# Public_CPU_DDR4.net
KiCad netlist of a schematic drawn in Altium Designer
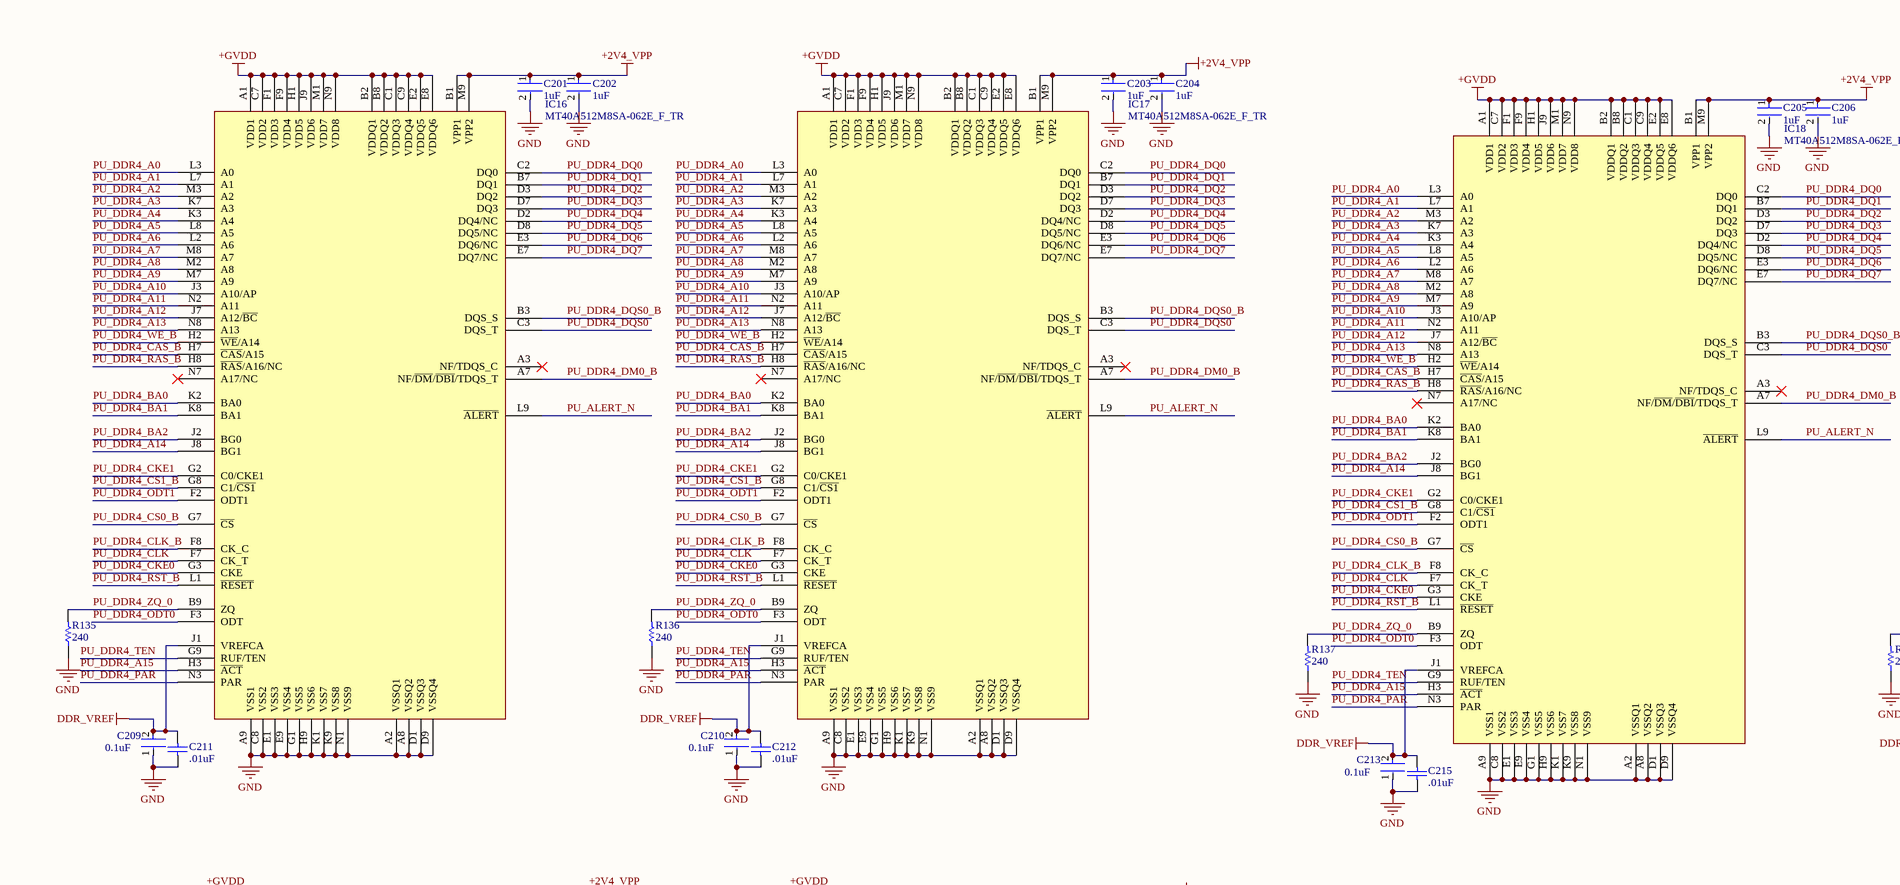
[diagram p0: Public_CPU_DDR4.SchDoc, top left]
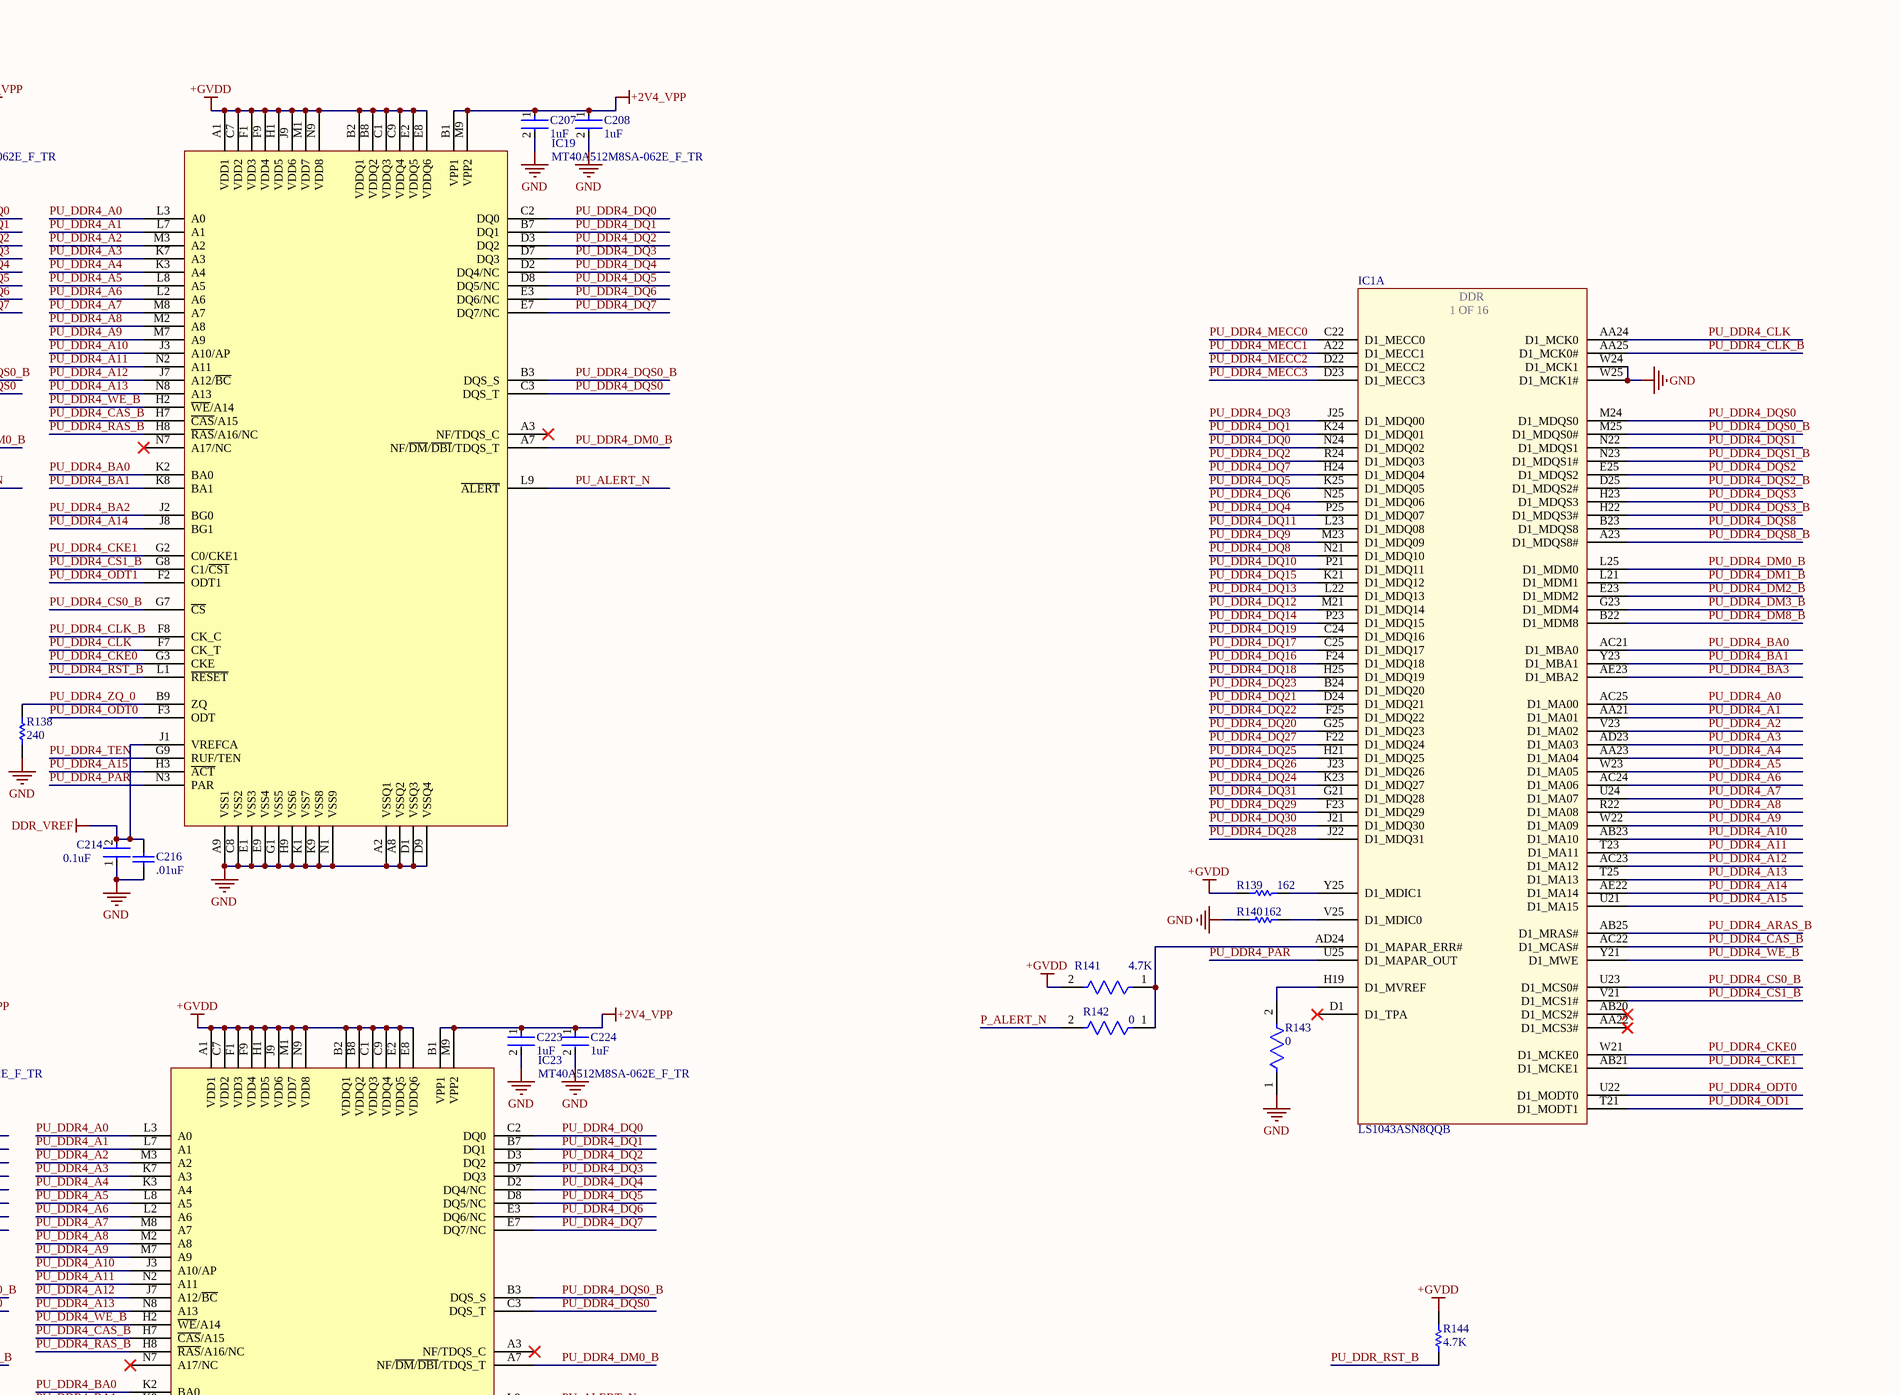
[diagram p1: Public_CPU_DDR4.SchDoc, top right]
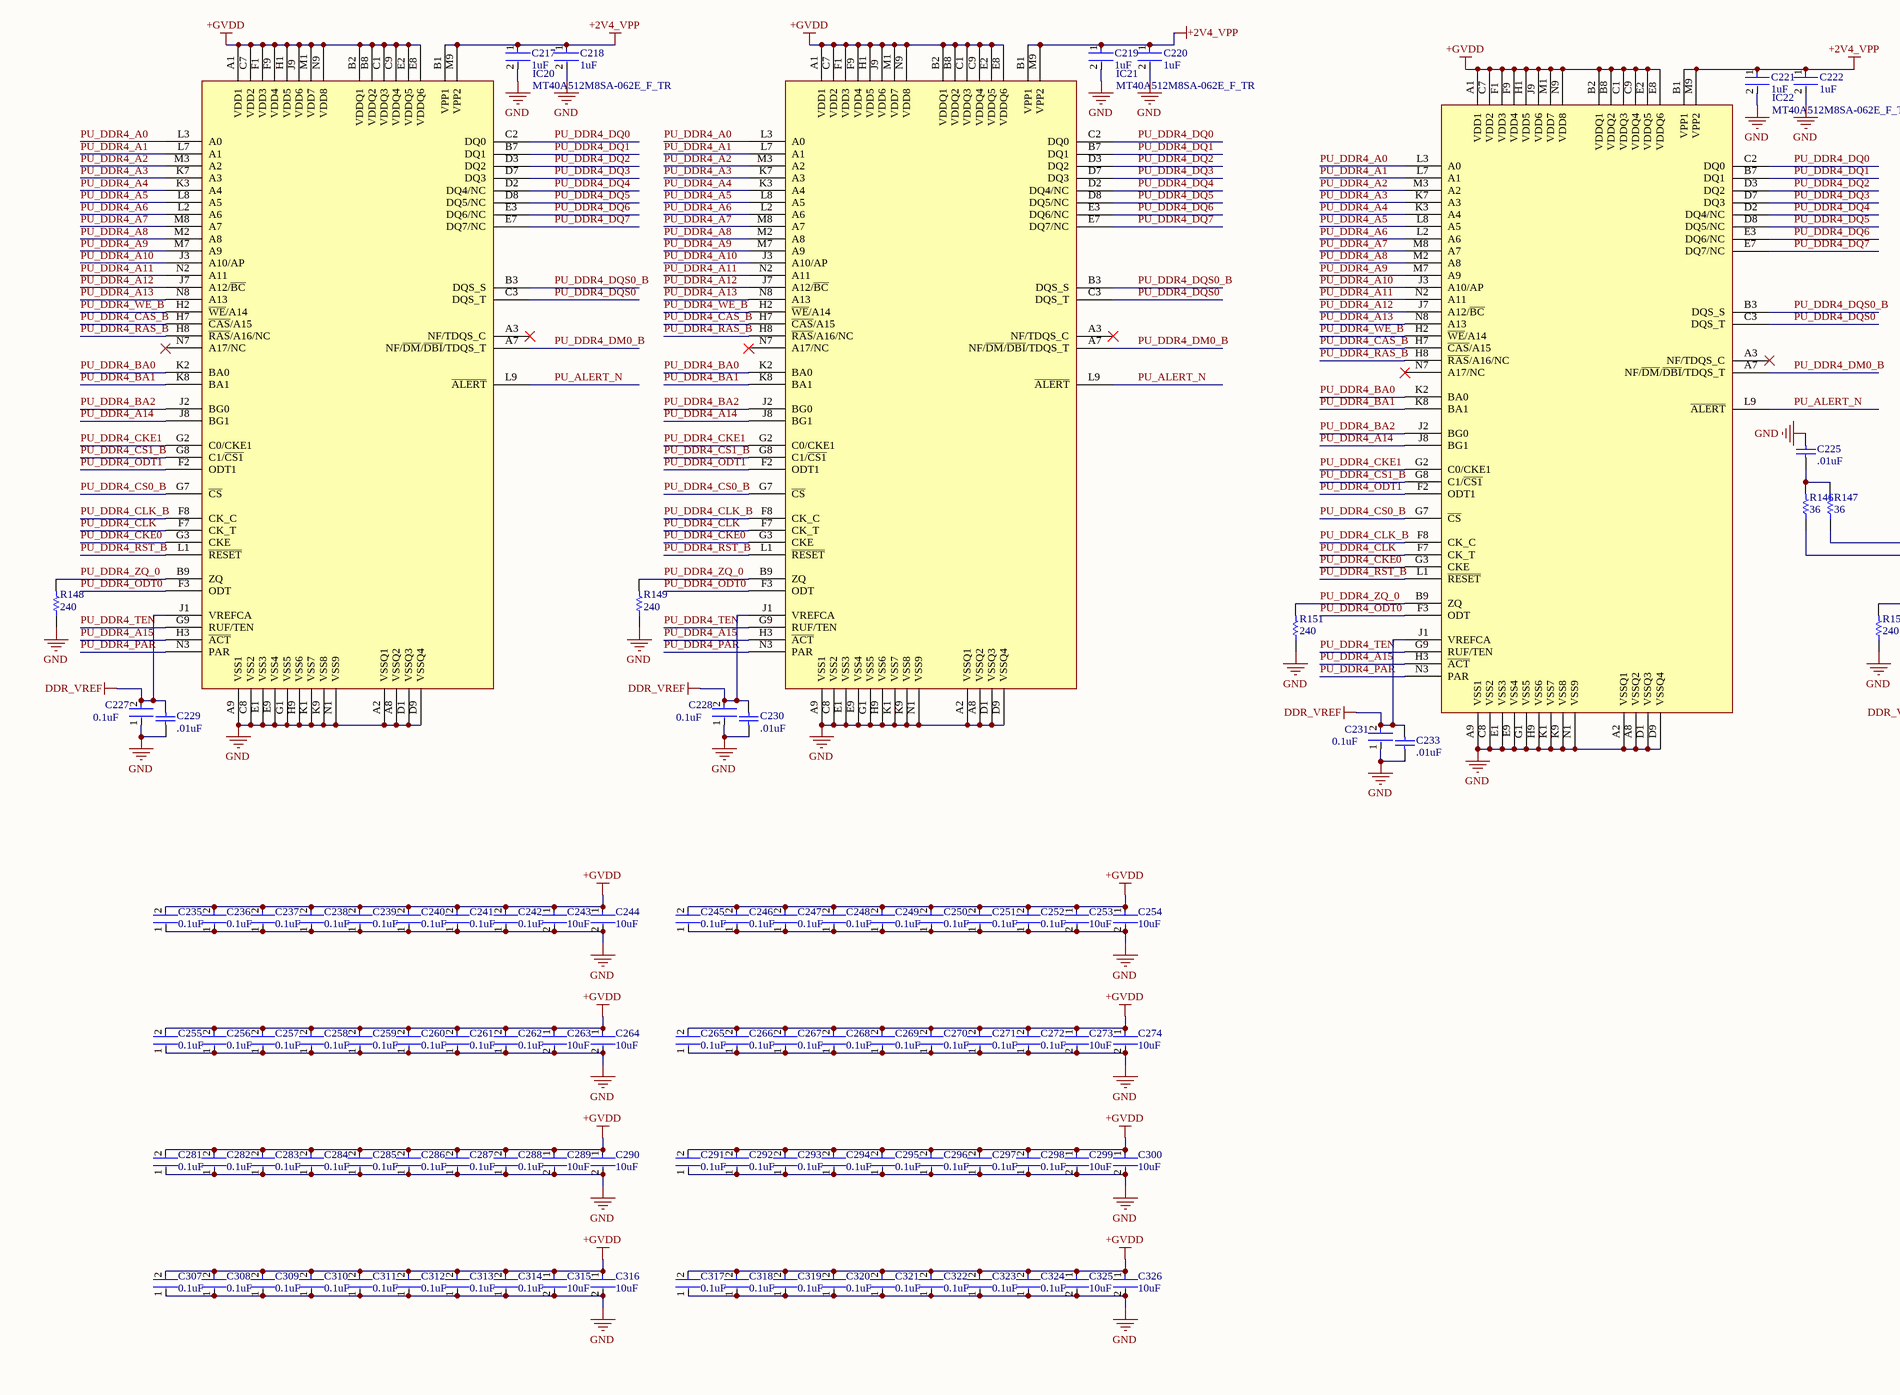
[diagram p2: Public_CPU_DDR4.SchDoc, bottom left]
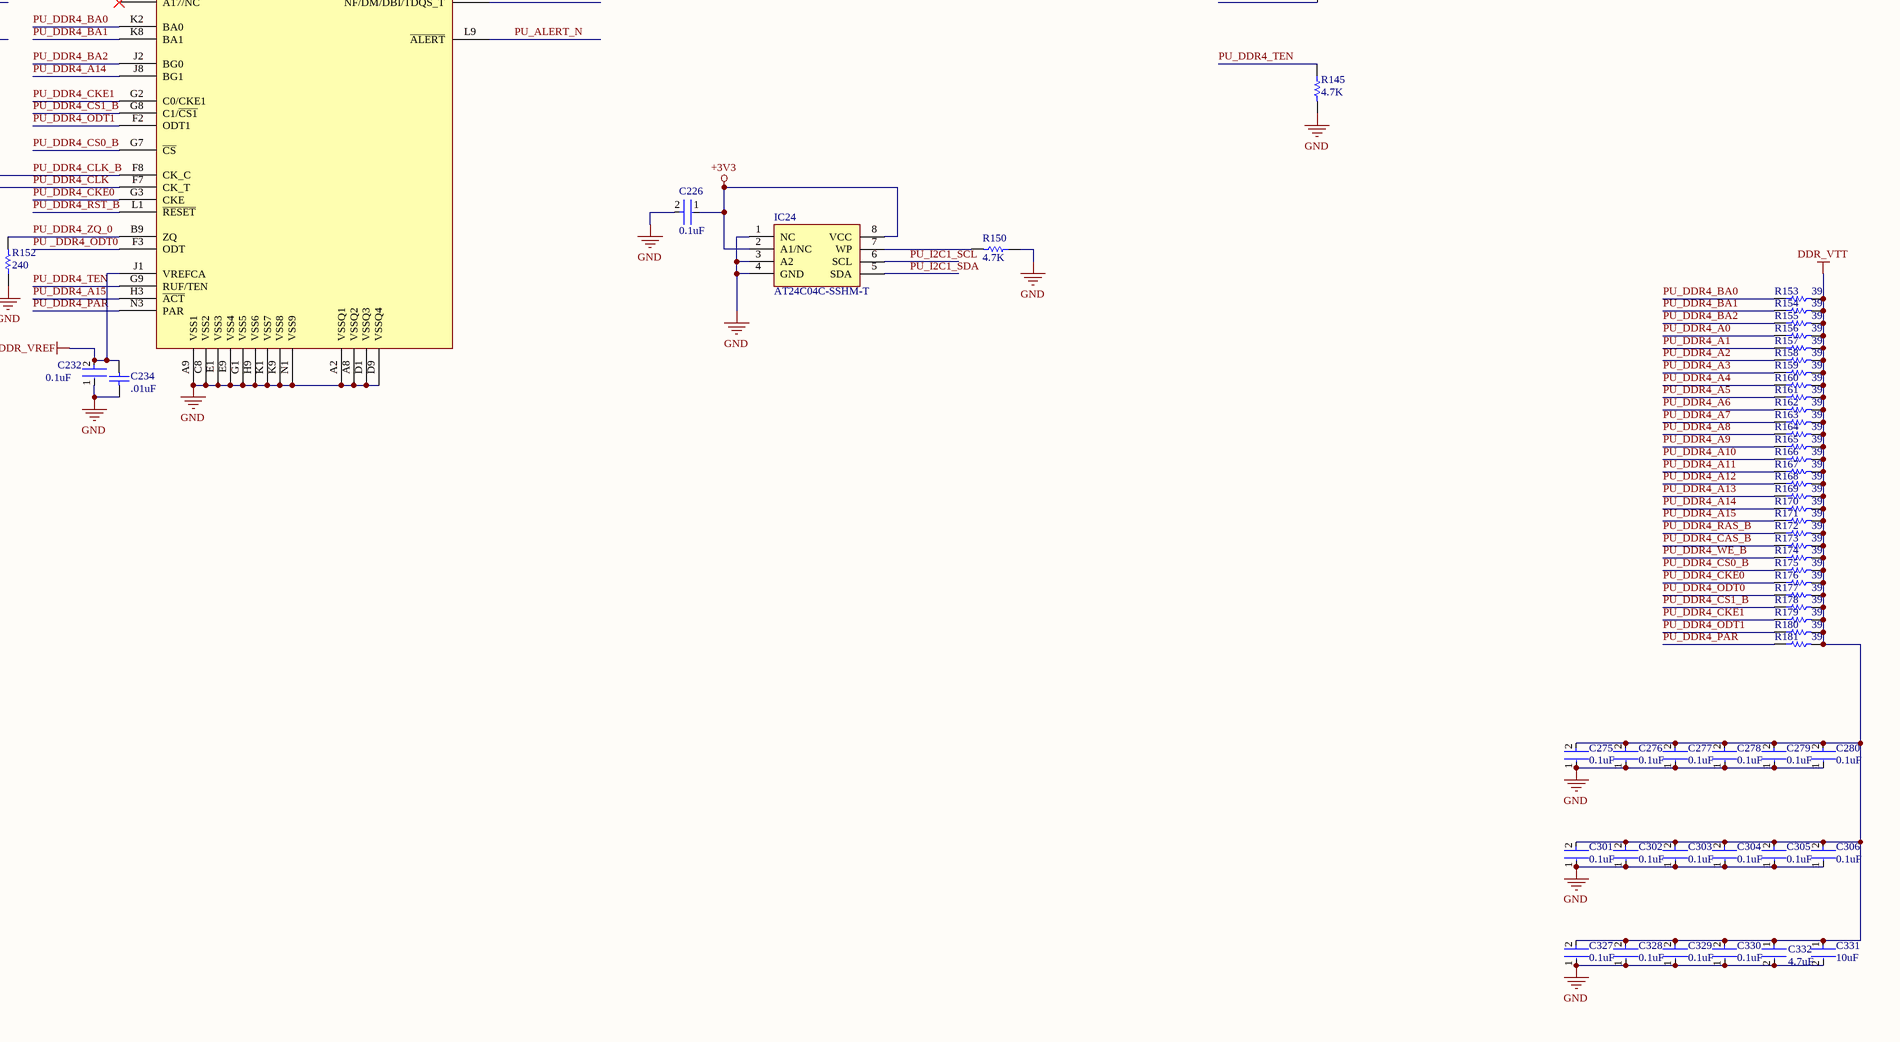
[diagram p3: Public_CPU_DDR4.SchDoc, bottom right]

(export (version "E")
  (design (tool "Eeschema 10.0.6"))
  (components
    (comp (ref "C201")
      (value "1uF")
      (footprint "FP-GRM15-0_1-MFG")
      (description "CAP CER 1UF 10V X5R 0402")
      (fields
        (field (name "OCTOPART") "https://octopart.com/grm155r61a105ke15d-murata-197442")
        (field (name "MANUFACTURER PART NUMBER") "GRM155R61A105KE15D")
      )
      (libsource (lib "Altium Content Vault") (part "02cd4be3c70576c341d710602a673aa"))
    )
    (comp (ref "C202")
      (value "1uF")
      (footprint "FP-GRM15-0_1-MFG")
      (description "CAP CER 1UF 10V X5R 0402")
      (fields
        (field (name "OCTOPART") "https://octopart.com/grm155r61a105ke15d-murata-197442")
        (field (name "MANUFACTURER PART NUMBER") "GRM155R61A105KE15D")
      )
      (libsource (lib "Altium Content Vault") (part "02cd4be3c70576c341d710602a673aa"))
    )
    (comp (ref "C203")
      (value "1uF")
      (footprint "FP-GRM15-0_1-MFG")
      (description "CAP CER 1UF 10V X5R 0402")
      (fields
        (field (name "OCTOPART") "https://octopart.com/grm155r61a105ke15d-murata-197442")
        (field (name "MANUFACTURER PART NUMBER") "GRM155R61A105KE15D")
      )
      (libsource (lib "Altium Content Vault") (part "02cd4be3c70576c341d710602a673aa"))
    )
    (comp (ref "C204")
      (value "1uF")
      (footprint "FP-GRM15-0_1-MFG")
      (description "CAP CER 1UF 10V X5R 0402")
      (fields
        (field (name "OCTOPART") "https://octopart.com/grm155r61a105ke15d-murata-197442")
        (field (name "MANUFACTURER PART NUMBER") "GRM155R61A105KE15D")
      )
      (libsource (lib "Altium Content Vault") (part "02cd4be3c70576c341d710602a673aa"))
    )
    (comp (ref "C205")
      (value "1uF")
      (footprint "FP-GRM15-0_1-MFG")
      (description "CAP CER 1UF 10V X5R 0402")
      (fields
        (field (name "OCTOPART") "https://octopart.com/grm155r61a105ke15d-murata-197442")
        (field (name "MANUFACTURER PART NUMBER") "GRM155R61A105KE15D")
      )
      (libsource (lib "Altium Content Vault") (part "02cd4be3c70576c341d710602a673aa"))
    )
    (comp (ref "C206")
      (value "1uF")
      (footprint "FP-GRM15-0_1-MFG")
      (description "CAP CER 1UF 10V X5R 0402")
      (fields
        (field (name "OCTOPART") "https://octopart.com/grm155r61a105ke15d-murata-197442")
        (field (name "MANUFACTURER PART NUMBER") "GRM155R61A105KE15D")
      )
      (libsource (lib "Altium Content Vault") (part "02cd4be3c70576c341d710602a673aa"))
    )
    (comp (ref "C207")
      (value "1uF")
      (footprint "FP-GRM15-0_1-MFG")
      (description "CAP CER 1UF 10V X5R 0402")
      (fields
        (field (name "OCTOPART") "https://octopart.com/grm155r61a105ke15d-murata-197442")
        (field (name "MANUFACTURER PART NUMBER") "GRM155R61A105KE15D")
      )
      (libsource (lib "Altium Content Vault") (part "02cd4be3c70576c341d710602a673aa"))
    )
    (comp (ref "C208")
      (value "1uF")
      (footprint "FP-GRM15-0_1-MFG")
      (description "CAP CER 1UF 10V X5R 0402")
      (fields
        (field (name "OCTOPART") "https://octopart.com/grm155r61a105ke15d-murata-197442")
        (field (name "MANUFACTURER PART NUMBER") "GRM155R61A105KE15D")
      )
      (libsource (lib "Altium Content Vault") (part "02cd4be3c70576c341d710602a673aa"))
    )
    (comp (ref "C209")
      (value "0.1uF")
      (footprint "FP-GRM15-MFG")
      (description "CAP CER 0.1UF 16V X7R 0402")
      (fields (field (name "MANUFACTURER PART NUMBER") "GRM155R71C104KA88D") (field (name "TOLERANCE") "10%"))
      (libsource (lib "Altium Content Vault") (part "236180d848d6139a670b325ea6854c9"))
    )
    (comp (ref "C210")
      (value "0.1uF")
      (footprint "FP-GRM15-MFG")
      (description "CAP CER 0.1UF 16V X7R 0402")
      (fields (field (name "MANUFACTURER PART NUMBER") "GRM155R71C104KA88D") (field (name "TOLERANCE") "10%"))
      (libsource (lib "Altium Content Vault") (part "236180d848d6139a670b325ea6854c9"))
    )
    (comp (ref "C211")
      (value ".01uF")
      (footprint "CAPC1005X56X25LL10T15")
      (fields
        (field (name "MANUFACTURER") "AVX Interconnect / Elco")
        (field (name "PART NUMBER") "0402YC103JAT2A")
      )
      (libsource (lib "Altium Content Vault") (part "CAP"))
    )
    (comp (ref "C212")
      (value ".01uF")
      (footprint "CAPC1005X56X25LL10T15")
      (fields
        (field (name "MANUFACTURER") "AVX Interconnect / Elco")
        (field (name "PART NUMBER") "0402YC103JAT2A")
      )
      (libsource (lib "Altium Content Vault") (part "CAP"))
    )
    (comp (ref "C213")
      (value "0.1uF")
      (footprint "FP-GRM15-MFG")
      (description "CAP CER 0.1UF 16V X7R 0402")
      (fields (field (name "MANUFACTURER PART NUMBER") "GRM155R71C104KA88D") (field (name "TOLERANCE") "10%"))
      (libsource (lib "Altium Content Vault") (part "236180d848d6139a670b325ea6854c9"))
    )
    (comp (ref "C214")
      (value "0.1uF")
      (footprint "FP-GRM15-MFG")
      (description "CAP CER 0.1UF 16V X7R 0402")
      (fields (field (name "MANUFACTURER PART NUMBER") "GRM155R71C104KA88D") (field (name "TOLERANCE") "10%"))
      (libsource (lib "Altium Content Vault") (part "236180d848d6139a670b325ea6854c9"))
    )
    (comp (ref "C215")
      (value ".01uF")
      (footprint "CAPC1005X56X25LL10T15")
      (fields
        (field (name "MANUFACTURER") "AVX Interconnect / Elco")
        (field (name "PART NUMBER") "0402YC103JAT2A")
      )
      (libsource (lib "Altium Content Vault") (part "CAP"))
    )
    (comp (ref "C216")
      (value ".01uF")
      (footprint "CAPC1005X56X25LL10T15")
      (fields
        (field (name "MANUFACTURER") "AVX Interconnect / Elco")
        (field (name "PART NUMBER") "0402YC103JAT2A")
      )
      (libsource (lib "Altium Content Vault") (part "CAP"))
    )
    (comp (ref "C217")
      (value "1uF")
      (footprint "FP-GRM15-0_1-MFG")
      (description "CAP CER 1UF 10V X5R 0402")
      (fields
        (field (name "OCTOPART") "https://octopart.com/grm155r61a105ke15d-murata-197442")
        (field (name "MANUFACTURER PART NUMBER") "GRM155R61A105KE15D")
      )
      (libsource (lib "Altium Content Vault") (part "02cd4be3c70576c341d710602a673aa"))
    )
    (comp (ref "C218")
      (value "1uF")
      (footprint "FP-GRM15-0_1-MFG")
      (description "CAP CER 1UF 10V X5R 0402")
      (fields
        (field (name "OCTOPART") "https://octopart.com/grm155r61a105ke15d-murata-197442")
        (field (name "MANUFACTURER PART NUMBER") "GRM155R61A105KE15D")
      )
      (libsource (lib "Altium Content Vault") (part "02cd4be3c70576c341d710602a673aa"))
    )
    (comp (ref "C219")
      (value "1uF")
      (footprint "FP-GRM15-0_1-MFG")
      (description "CAP CER 1UF 10V X5R 0402")
      (fields
        (field (name "OCTOPART") "https://octopart.com/grm155r61a105ke15d-murata-197442")
        (field (name "MANUFACTURER PART NUMBER") "GRM155R61A105KE15D")
      )
      (libsource (lib "Altium Content Vault") (part "02cd4be3c70576c341d710602a673aa"))
    )
    (comp (ref "C220")
      (value "1uF")
      (footprint "FP-GRM15-0_1-MFG")
      (description "CAP CER 1UF 10V X5R 0402")
      (fields
        (field (name "OCTOPART") "https://octopart.com/grm155r61a105ke15d-murata-197442")
        (field (name "MANUFACTURER PART NUMBER") "GRM155R61A105KE15D")
      )
      (libsource (lib "Altium Content Vault") (part "02cd4be3c70576c341d710602a673aa"))
    )
    (comp (ref "C221")
      (value "1uF")
      (footprint "FP-GRM15-0_1-MFG")
      (description "CAP CER 1UF 10V X5R 0402")
      (fields
        (field (name "OCTOPART") "https://octopart.com/grm155r61a105ke15d-murata-197442")
        (field (name "MANUFACTURER PART NUMBER") "GRM155R61A105KE15D")
      )
      (libsource (lib "Altium Content Vault") (part "02cd4be3c70576c341d710602a673aa"))
    )
    (comp (ref "C222")
      (value "1uF")
      (footprint "FP-GRM15-0_1-MFG")
      (description "CAP CER 1UF 10V X5R 0402")
      (fields
        (field (name "OCTOPART") "https://octopart.com/grm155r61a105ke15d-murata-197442")
        (field (name "MANUFACTURER PART NUMBER") "GRM155R61A105KE15D")
      )
      (libsource (lib "Altium Content Vault") (part "02cd4be3c70576c341d710602a673aa"))
    )
    (comp (ref "C223")
      (value "1uF")
      (footprint "FP-GRM15-0_1-MFG")
      (description "CAP CER 1UF 10V X5R 0402")
      (fields
        (field (name "OCTOPART") "https://octopart.com/grm155r61a105ke15d-murata-197442")
        (field (name "MANUFACTURER PART NUMBER") "GRM155R61A105KE15D")
      )
      (libsource (lib "Altium Content Vault") (part "02cd4be3c70576c341d710602a673aa"))
    )
    (comp (ref "C224")
      (value "1uF")
      (footprint "FP-GRM15-0_1-MFG")
      (description "CAP CER 1UF 10V X5R 0402")
      (fields
        (field (name "OCTOPART") "https://octopart.com/grm155r61a105ke15d-murata-197442")
        (field (name "MANUFACTURER PART NUMBER") "GRM155R61A105KE15D")
      )
      (libsource (lib "Altium Content Vault") (part "02cd4be3c70576c341d710602a673aa"))
    )
    (comp (ref "C225")
      (value ".01uF")
      (footprint "CAPC1005X56X25LL10T15")
      (fields
        (field (name "MANUFACTURER") "AVX Interconnect / Elco")
        (field (name "PART NUMBER") "0402YC103JAT2A")
      )
      (libsource (lib "Altium Content Vault") (part "CAP"))
    )
    (comp (ref "C226")
      (value "0.1uF")
      (footprint "FP-GRM15-MFG")
      (description "CAP CER 0.1UF 16V X7R 0402")
      (fields (field (name "MANUFACTURER PART NUMBER") "GRM155R71C104KA88D") (field (name "TOLERANCE") "10%"))
      (libsource (lib "Altium Content Vault") (part "236180d848d6139a670b325ea6854c9"))
    )
    (comp (ref "C227")
      (value "0.1uF")
      (footprint "FP-GRM15-MFG")
      (description "CAP CER 0.1UF 16V X7R 0402")
      (fields (field (name "MANUFACTURER PART NUMBER") "GRM155R71C104KA88D") (field (name "TOLERANCE") "10%"))
      (libsource (lib "Altium Content Vault") (part "236180d848d6139a670b325ea6854c9"))
    )
    (comp (ref "C228")
      (value "0.1uF")
      (footprint "FP-GRM15-MFG")
      (description "CAP CER 0.1UF 16V X7R 0402")
      (fields (field (name "MANUFACTURER PART NUMBER") "GRM155R71C104KA88D") (field (name "TOLERANCE") "10%"))
      (libsource (lib "Altium Content Vault") (part "236180d848d6139a670b325ea6854c9"))
    )
    (comp (ref "C229")
      (value ".01uF")
      (footprint "CAPC1005X56X25LL10T15")
      (fields
        (field (name "MANUFACTURER") "AVX Interconnect / Elco")
        (field (name "PART NUMBER") "0402YC103JAT2A")
      )
      (libsource (lib "Altium Content Vault") (part "CAP"))
    )
    (comp (ref "C230")
      (value ".01uF")
      (footprint "CAPC1005X56X25LL10T15")
      (fields
        (field (name "MANUFACTURER") "AVX Interconnect / Elco")
        (field (name "PART NUMBER") "0402YC103JAT2A")
      )
      (libsource (lib "Altium Content Vault") (part "CAP"))
    )
    (comp (ref "C231")
      (value "0.1uF")
      (footprint "FP-GRM15-MFG")
      (description "CAP CER 0.1UF 16V X7R 0402")
      (fields (field (name "MANUFACTURER PART NUMBER") "GRM155R71C104KA88D") (field (name "TOLERANCE") "10%"))
      (libsource (lib "Altium Content Vault") (part "236180d848d6139a670b325ea6854c9"))
    )
    (comp (ref "C232")
      (value "0.1uF")
      (footprint "FP-GRM15-MFG")
      (description "CAP CER 0.1UF 16V X7R 0402")
      (fields (field (name "MANUFACTURER PART NUMBER") "GRM155R71C104KA88D") (field (name "TOLERANCE") "10%"))
      (libsource (lib "Altium Content Vault") (part "236180d848d6139a670b325ea6854c9"))
    )
    (comp (ref "C233")
      (value ".01uF")
      (footprint "CAPC1005X56X25LL10T15")
      (fields
        (field (name "MANUFACTURER") "AVX Interconnect / Elco")
        (field (name "PART NUMBER") "0402YC103JAT2A")
      )
      (libsource (lib "Altium Content Vault") (part "CAP"))
    )
    (comp (ref "C234")
      (value ".01uF")
      (footprint "CAPC1005X56X25LL10T15")
      (fields
        (field (name "MANUFACTURER") "AVX Interconnect / Elco")
        (field (name "PART NUMBER") "0402YC103JAT2A")
      )
      (libsource (lib "Altium Content Vault") (part "CAP"))
    )
    (comp (ref "C235")
      (value "0.1uF")
      (footprint "FP-GRM15-MFG")
      (description "CAP CER 0.1UF 16V X7R 0402")
      (fields (field (name "MANUFACTURER PART NUMBER") "GRM155R71C104KA88D") (field (name "TOLERANCE") "10%"))
      (libsource (lib "Altium Content Vault") (part "236180d848d6139a670b325ea6854c9"))
    )
    (comp (ref "C236")
      (value "0.1uF")
      (footprint "FP-GRM15-MFG")
      (description "CAP CER 0.1UF 16V X7R 0402")
      (fields (field (name "MANUFACTURER PART NUMBER") "GRM155R71C104KA88D") (field (name "TOLERANCE") "10%"))
      (libsource (lib "Altium Content Vault") (part "236180d848d6139a670b325ea6854c9"))
    )
    (comp (ref "C237")
      (value "0.1uF")
      (footprint "FP-GRM15-MFG")
      (description "CAP CER 0.1UF 16V X7R 0402")
      (fields (field (name "MANUFACTURER PART NUMBER") "GRM155R71C104KA88D") (field (name "TOLERANCE") "10%"))
      (libsource (lib "Altium Content Vault") (part "236180d848d6139a670b325ea6854c9"))
    )
    (comp (ref "C238")
      (value "0.1uF")
      (footprint "FP-GRM15-MFG")
      (description "CAP CER 0.1UF 16V X7R 0402")
      (fields (field (name "MANUFACTURER PART NUMBER") "GRM155R71C104KA88D") (field (name "TOLERANCE") "10%"))
      (libsource (lib "Altium Content Vault") (part "236180d848d6139a670b325ea6854c9"))
    )
    (comp (ref "C239")
      (value "0.1uF")
      (footprint "FP-GRM15-MFG")
      (description "CAP CER 0.1UF 16V X7R 0402")
      (fields (field (name "MANUFACTURER PART NUMBER") "GRM155R71C104KA88D") (field (name "TOLERANCE") "10%"))
      (libsource (lib "Altium Content Vault") (part "236180d848d6139a670b325ea6854c9"))
    )
    (comp (ref "C240")
      (value "0.1uF")
      (footprint "FP-GRM15-MFG")
      (description "CAP CER 0.1UF 16V X7R 0402")
      (fields (field (name "MANUFACTURER PART NUMBER") "GRM155R71C104KA88D") (field (name "TOLERANCE") "10%"))
      (libsource (lib "Altium Content Vault") (part "236180d848d6139a670b325ea6854c9"))
    )
    (comp (ref "C241")
      (value "0.1uF")
      (footprint "FP-GRM15-MFG")
      (description "CAP CER 0.1UF 16V X7R 0402")
      (fields (field (name "MANUFACTURER PART NUMBER") "GRM155R71C104KA88D") (field (name "TOLERANCE") "10%"))
      (libsource (lib "Altium Content Vault") (part "236180d848d6139a670b325ea6854c9"))
    )
    (comp (ref "C242")
      (value "0.1uF")
      (footprint "FP-GRM15-MFG")
      (description "CAP CER 0.1UF 16V X7R 0402")
      (fields (field (name "MANUFACTURER PART NUMBER") "GRM155R71C104KA88D") (field (name "TOLERANCE") "10%"))
      (libsource (lib "Altium Content Vault") (part "236180d848d6139a670b325ea6854c9"))
    )
    (comp (ref "C243")
      (value "10uF")
      (footprint "FP-GRM21B-0_1-IPC_C")
      (description "Chip Multilayer Ceramic Capacitors for General Purpose, 0805, 10uF, X5R, 15%, 10%, 16V")
      (fields (field (name "TOLERANCE") "10%") (field (name "VOLTAGE") "16V"))
      (libsource (lib "Altium Content Vault") (part "b4654b650e69147ec39a6b967a45e02"))
    )
    (comp (ref "C244")
      (value "10uF")
      (footprint "FP-GRM21B-0_1-IPC_C")
      (description "Chip Multilayer Ceramic Capacitors for General Purpose, 0805, 10uF, X5R, 15%, 10%, 16V")
      (fields (field (name "TOLERANCE") "10%") (field (name "VOLTAGE") "16V"))
      (libsource (lib "Altium Content Vault") (part "b4654b650e69147ec39a6b967a45e02"))
    )
    (comp (ref "C245")
      (value "0.1uF")
      (footprint "FP-GRM15-MFG")
      (description "CAP CER 0.1UF 16V X7R 0402")
      (fields (field (name "MANUFACTURER PART NUMBER") "GRM155R71C104KA88D") (field (name "TOLERANCE") "10%"))
      (libsource (lib "Altium Content Vault") (part "236180d848d6139a670b325ea6854c9"))
    )
    (comp (ref "C246")
      (value "0.1uF")
      (footprint "FP-GRM15-MFG")
      (description "CAP CER 0.1UF 16V X7R 0402")
      (fields (field (name "MANUFACTURER PART NUMBER") "GRM155R71C104KA88D") (field (name "TOLERANCE") "10%"))
      (libsource (lib "Altium Content Vault") (part "236180d848d6139a670b325ea6854c9"))
    )
    (comp (ref "C247")
      (value "0.1uF")
      (footprint "FP-GRM15-MFG")
      (description "CAP CER 0.1UF 16V X7R 0402")
      (fields (field (name "MANUFACTURER PART NUMBER") "GRM155R71C104KA88D") (field (name "TOLERANCE") "10%"))
      (libsource (lib "Altium Content Vault") (part "236180d848d6139a670b325ea6854c9"))
    )
    (comp (ref "C248")
      (value "0.1uF")
      (footprint "FP-GRM15-MFG")
      (description "CAP CER 0.1UF 16V X7R 0402")
      (fields (field (name "MANUFACTURER PART NUMBER") "GRM155R71C104KA88D") (field (name "TOLERANCE") "10%"))
      (libsource (lib "Altium Content Vault") (part "236180d848d6139a670b325ea6854c9"))
    )
    (comp (ref "C249")
      (value "0.1uF")
      (footprint "FP-GRM15-MFG")
      (description "CAP CER 0.1UF 16V X7R 0402")
      (fields (field (name "MANUFACTURER PART NUMBER") "GRM155R71C104KA88D") (field (name "TOLERANCE") "10%"))
      (libsource (lib "Altium Content Vault") (part "236180d848d6139a670b325ea6854c9"))
    )
    (comp (ref "C250")
      (value "0.1uF")
      (footprint "FP-GRM15-MFG")
      (description "CAP CER 0.1UF 16V X7R 0402")
      (fields (field (name "MANUFACTURER PART NUMBER") "GRM155R71C104KA88D") (field (name "TOLERANCE") "10%"))
      (libsource (lib "Altium Content Vault") (part "236180d848d6139a670b325ea6854c9"))
    )
    (comp (ref "C251")
      (value "0.1uF")
      (footprint "FP-GRM15-MFG")
      (description "CAP CER 0.1UF 16V X7R 0402")
      (fields (field (name "MANUFACTURER PART NUMBER") "GRM155R71C104KA88D") (field (name "TOLERANCE") "10%"))
      (libsource (lib "Altium Content Vault") (part "236180d848d6139a670b325ea6854c9"))
    )
    (comp (ref "C252")
      (value "0.1uF")
      (footprint "FP-GRM15-MFG")
      (description "CAP CER 0.1UF 16V X7R 0402")
      (fields (field (name "MANUFACTURER PART NUMBER") "GRM155R71C104KA88D") (field (name "TOLERANCE") "10%"))
      (libsource (lib "Altium Content Vault") (part "236180d848d6139a670b325ea6854c9"))
    )
    (comp (ref "C253")
      (value "10uF")
      (footprint "FP-GRM21B-0_1-IPC_C")
      (description "Chip Multilayer Ceramic Capacitors for General Purpose, 0805, 10uF, X5R, 15%, 10%, 16V")
      (fields (field (name "TOLERANCE") "10%") (field (name "VOLTAGE") "16V"))
      (libsource (lib "Altium Content Vault") (part "b4654b650e69147ec39a6b967a45e02"))
    )
    (comp (ref "C254")
      (value "10uF")
      (footprint "FP-GRM21B-0_1-IPC_C")
      (description "Chip Multilayer Ceramic Capacitors for General Purpose, 0805, 10uF, X5R, 15%, 10%, 16V")
      (fields (field (name "TOLERANCE") "10%") (field (name "VOLTAGE") "16V"))
      (libsource (lib "Altium Content Vault") (part "b4654b650e69147ec39a6b967a45e02"))
    )
    (comp (ref "C255")
      (value "0.1uF")
      (footprint "FP-GRM15-MFG")
      (description "CAP CER 0.1UF 16V X7R 0402")
      (fields (field (name "MANUFACTURER PART NUMBER") "GRM155R71C104KA88D") (field (name "TOLERANCE") "10%"))
      (libsource (lib "Altium Content Vault") (part "236180d848d6139a670b325ea6854c9"))
    )
    (comp (ref "C256")
      (value "0.1uF")
      (footprint "FP-GRM15-MFG")
      (description "CAP CER 0.1UF 16V X7R 0402")
      (fields (field (name "MANUFACTURER PART NUMBER") "GRM155R71C104KA88D") (field (name "TOLERANCE") "10%"))
      (libsource (lib "Altium Content Vault") (part "236180d848d6139a670b325ea6854c9"))
    )
    (comp (ref "C257")
      (value "0.1uF")
      (footprint "FP-GRM15-MFG")
      (description "CAP CER 0.1UF 16V X7R 0402")
      (fields (field (name "MANUFACTURER PART NUMBER") "GRM155R71C104KA88D") (field (name "TOLERANCE") "10%"))
      (libsource (lib "Altium Content Vault") (part "236180d848d6139a670b325ea6854c9"))
    )
    (comp (ref "C258")
      (value "0.1uF")
      (footprint "FP-GRM15-MFG")
      (description "CAP CER 0.1UF 16V X7R 0402")
      (fields (field (name "MANUFACTURER PART NUMBER") "GRM155R71C104KA88D") (field (name "TOLERANCE") "10%"))
      (libsource (lib "Altium Content Vault") (part "236180d848d6139a670b325ea6854c9"))
    )
    (comp (ref "C259")
      (value "0.1uF")
      (footprint "FP-GRM15-MFG")
      (description "CAP CER 0.1UF 16V X7R 0402")
      (fields (field (name "MANUFACTURER PART NUMBER") "GRM155R71C104KA88D") (field (name "TOLERANCE") "10%"))
      (libsource (lib "Altium Content Vault") (part "236180d848d6139a670b325ea6854c9"))
    )
    (comp (ref "C260")
      (value "0.1uF")
      (footprint "FP-GRM15-MFG")
      (description "CAP CER 0.1UF 16V X7R 0402")
      (fields (field (name "MANUFACTURER PART NUMBER") "GRM155R71C104KA88D") (field (name "TOLERANCE") "10%"))
      (libsource (lib "Altium Content Vault") (part "236180d848d6139a670b325ea6854c9"))
    )
    (comp (ref "C261")
      (value "0.1uF")
      (footprint "FP-GRM15-MFG")
      (description "CAP CER 0.1UF 16V X7R 0402")
      (fields (field (name "MANUFACTURER PART NUMBER") "GRM155R71C104KA88D") (field (name "TOLERANCE") "10%"))
      (libsource (lib "Altium Content Vault") (part "236180d848d6139a670b325ea6854c9"))
    )
    (comp (ref "C262")
      (value "0.1uF")
      (footprint "FP-GRM15-MFG")
      (description "CAP CER 0.1UF 16V X7R 0402")
      (fields (field (name "MANUFACTURER PART NUMBER") "GRM155R71C104KA88D") (field (name "TOLERANCE") "10%"))
      (libsource (lib "Altium Content Vault") (part "236180d848d6139a670b325ea6854c9"))
    )
    (comp (ref "C263")
      (value "10uF")
      (footprint "FP-GRM21B-0_1-IPC_C")
      (description "Chip Multilayer Ceramic Capacitors for General Purpose, 0805, 10uF, X5R, 15%, 10%, 16V")
      (fields (field (name "TOLERANCE") "10%") (field (name "VOLTAGE") "16V"))
      (libsource (lib "Altium Content Vault") (part "b4654b650e69147ec39a6b967a45e02"))
    )
    (comp (ref "C264")
      (value "10uF")
      (footprint "FP-GRM21B-0_1-IPC_C")
      (description "Chip Multilayer Ceramic Capacitors for General Purpose, 0805, 10uF, X5R, 15%, 10%, 16V")
      (fields (field (name "TOLERANCE") "10%") (field (name "VOLTAGE") "16V"))
      (libsource (lib "Altium Content Vault") (part "b4654b650e69147ec39a6b967a45e02"))
    )
    (comp (ref "C265")
      (value "0.1uF")
      (footprint "FP-GRM15-MFG")
      (description "CAP CER 0.1UF 16V X7R 0402")
      (fields (field (name "MANUFACTURER PART NUMBER") "GRM155R71C104KA88D") (field (name "TOLERANCE") "10%"))
      (libsource (lib "Altium Content Vault") (part "236180d848d6139a670b325ea6854c9"))
    )
    (comp (ref "C266")
      (value "0.1uF")
      (footprint "FP-GRM15-MFG")
      (description "CAP CER 0.1UF 16V X7R 0402")
      (fields (field (name "MANUFACTURER PART NUMBER") "GRM155R71C104KA88D") (field (name "TOLERANCE") "10%"))
      (libsource (lib "Altium Content Vault") (part "236180d848d6139a670b325ea6854c9"))
    )
    (comp (ref "C267")
      (value "0.1uF")
      (footprint "FP-GRM15-MFG")
      (description "CAP CER 0.1UF 16V X7R 0402")
      (fields (field (name "MANUFACTURER PART NUMBER") "GRM155R71C104KA88D") (field (name "TOLERANCE") "10%"))
      (libsource (lib "Altium Content Vault") (part "236180d848d6139a670b325ea6854c9"))
    )
    (comp (ref "C268")
      (value "0.1uF")
      (footprint "FP-GRM15-MFG")
      (description "CAP CER 0.1UF 16V X7R 0402")
      (fields (field (name "MANUFACTURER PART NUMBER") "GRM155R71C104KA88D") (field (name "TOLERANCE") "10%"))
      (libsource (lib "Altium Content Vault") (part "236180d848d6139a670b325ea6854c9"))
    )
    (comp (ref "C269")
      (value "0.1uF")
      (footprint "FP-GRM15-MFG")
      (description "CAP CER 0.1UF 16V X7R 0402")
      (fields (field (name "MANUFACTURER PART NUMBER") "GRM155R71C104KA88D") (field (name "TOLERANCE") "10%"))
      (libsource (lib "Altium Content Vault") (part "236180d848d6139a670b325ea6854c9"))
    )
    (comp (ref "C270")
      (value "0.1uF")
      (footprint "FP-GRM15-MFG")
      (description "CAP CER 0.1UF 16V X7R 0402")
      (fields (field (name "MANUFACTURER PART NUMBER") "GRM155R71C104KA88D") (field (name "TOLERANCE") "10%"))
      (libsource (lib "Altium Content Vault") (part "236180d848d6139a670b325ea6854c9"))
    )
    (comp (ref "C271")
      (value "0.1uF")
      (footprint "FP-GRM15-MFG")
      (description "CAP CER 0.1UF 16V X7R 0402")
      (fields (field (name "MANUFACTURER PART NUMBER") "GRM155R71C104KA88D") (field (name "TOLERANCE") "10%"))
      (libsource (lib "Altium Content Vault") (part "236180d848d6139a670b325ea6854c9"))
    )
    (comp (ref "C272")
      (value "0.1uF")
      (footprint "FP-GRM15-MFG")
      (description "CAP CER 0.1UF 16V X7R 0402")
      (fields (field (name "MANUFACTURER PART NUMBER") "GRM155R71C104KA88D") (field (name "TOLERANCE") "10%"))
      (libsource (lib "Altium Content Vault") (part "236180d848d6139a670b325ea6854c9"))
    )
    (comp (ref "C273")
      (value "10uF")
      (footprint "FP-GRM21B-0_1-IPC_C")
      (description "Chip Multilayer Ceramic Capacitors for General Purpose, 0805, 10uF, X5R, 15%, 10%, 16V")
      (fields (field (name "TOLERANCE") "10%") (field (name "VOLTAGE") "16V"))
      (libsource (lib "Altium Content Vault") (part "b4654b650e69147ec39a6b967a45e02"))
    )
    (comp (ref "C274")
      (value "10uF")
      (footprint "FP-GRM21B-0_1-IPC_C")
      (description "Chip Multilayer Ceramic Capacitors for General Purpose, 0805, 10uF, X5R, 15%, 10%, 16V")
      (fields (field (name "TOLERANCE") "10%") (field (name "VOLTAGE") "16V"))
      (libsource (lib "Altium Content Vault") (part "b4654b650e69147ec39a6b967a45e02"))
    )
    (comp (ref "C275")
      (value "0.1uF")
      (footprint "FP-GRM15-MFG")
      (description "CAP CER 0.1UF 16V X7R 0402")
      (fields (field (name "MANUFACTURER PART NUMBER") "GRM155R71C104KA88D") (field (name "TOLERANCE") "10%"))
      (libsource (lib "Altium Content Vault") (part "236180d848d6139a670b325ea6854c9"))
    )
    (comp (ref "C276")
      (value "0.1uF")
      (footprint "FP-GRM15-MFG")
      (description "CAP CER 0.1UF 16V X7R 0402")
      (fields (field (name "MANUFACTURER PART NUMBER") "GRM155R71C104KA88D") (field (name "TOLERANCE") "10%"))
      (libsource (lib "Altium Content Vault") (part "236180d848d6139a670b325ea6854c9"))
    )
    (comp (ref "C277")
      (value "0.1uF")
      (footprint "FP-GRM15-MFG")
      (description "CAP CER 0.1UF 16V X7R 0402")
      (fields (field (name "MANUFACTURER PART NUMBER") "GRM155R71C104KA88D") (field (name "TOLERANCE") "10%"))
      (libsource (lib "Altium Content Vault") (part "236180d848d6139a670b325ea6854c9"))
    )
    (comp (ref "C278")
      (value "0.1uF")
      (footprint "FP-GRM15-MFG")
      (description "CAP CER 0.1UF 16V X7R 0402")
      (fields (field (name "MANUFACTURER PART NUMBER") "GRM155R71C104KA88D") (field (name "TOLERANCE") "10%"))
      (libsource (lib "Altium Content Vault") (part "236180d848d6139a670b325ea6854c9"))
    )
    (comp (ref "C279")
      (value "0.1uF")
      (footprint "FP-GRM15-MFG")
      (description "CAP CER 0.1UF 16V X7R 0402")
      (fields (field (name "MANUFACTURER PART NUMBER") "GRM155R71C104KA88D") (field (name "TOLERANCE") "10%"))
      (libsource (lib "Altium Content Vault") (part "236180d848d6139a670b325ea6854c9"))
    )
    (comp (ref "C280")
      (value "0.1uF")
      (footprint "FP-GRM15-MFG")
      (description "CAP CER 0.1UF 16V X7R 0402")
      (fields (field (name "MANUFACTURER PART NUMBER") "GRM155R71C104KA88D") (field (name "TOLERANCE") "10%"))
      (libsource (lib "Altium Content Vault") (part "236180d848d6139a670b325ea6854c9"))
    )
    (comp (ref "C281")
      (value "0.1uF")
      (footprint "FP-GRM15-MFG")
      (description "CAP CER 0.1UF 16V X7R 0402")
      (fields (field (name "MANUFACTURER PART NUMBER") "GRM155R71C104KA88D") (field (name "TOLERANCE") "10%"))
      (libsource (lib "Altium Content Vault") (part "236180d848d6139a670b325ea6854c9"))
    )
    (comp (ref "C282")
      (value "0.1uF")
      (footprint "FP-GRM15-MFG")
      (description "CAP CER 0.1UF 16V X7R 0402")
      (fields (field (name "MANUFACTURER PART NUMBER") "GRM155R71C104KA88D") (field (name "TOLERANCE") "10%"))
      (libsource (lib "Altium Content Vault") (part "236180d848d6139a670b325ea6854c9"))
    )
    (comp (ref "C283")
      (value "0.1uF")
      (footprint "FP-GRM15-MFG")
      (description "CAP CER 0.1UF 16V X7R 0402")
      (fields (field (name "MANUFACTURER PART NUMBER") "GRM155R71C104KA88D") (field (name "TOLERANCE") "10%"))
      (libsource (lib "Altium Content Vault") (part "236180d848d6139a670b325ea6854c9"))
    )
    (comp (ref "C284")
      (value "0.1uF")
      (footprint "FP-GRM15-MFG")
      (description "CAP CER 0.1UF 16V X7R 0402")
      (fields (field (name "MANUFACTURER PART NUMBER") "GRM155R71C104KA88D") (field (name "TOLERANCE") "10%"))
      (libsource (lib "Altium Content Vault") (part "236180d848d6139a670b325ea6854c9"))
    )
    (comp (ref "C285")
      (value "0.1uF")
      (footprint "FP-GRM15-MFG")
      (description "CAP CER 0.1UF 16V X7R 0402")
      (fields (field (name "MANUFACTURER PART NUMBER") "GRM155R71C104KA88D") (field (name "TOLERANCE") "10%"))
      (libsource (lib "Altium Content Vault") (part "236180d848d6139a670b325ea6854c9"))
    )
    (comp (ref "C286")
      (value "0.1uF")
      (footprint "FP-GRM15-MFG")
      (description "CAP CER 0.1UF 16V X7R 0402")
      (fields (field (name "MANUFACTURER PART NUMBER") "GRM155R71C104KA88D") (field (name "TOLERANCE") "10%"))
      (libsource (lib "Altium Content Vault") (part "236180d848d6139a670b325ea6854c9"))
    )
    (comp (ref "C287")
      (value "0.1uF")
      (footprint "FP-GRM15-MFG")
      (description "CAP CER 0.1UF 16V X7R 0402")
      (fields (field (name "MANUFACTURER PART NUMBER") "GRM155R71C104KA88D") (field (name "TOLERANCE") "10%"))
      (libsource (lib "Altium Content Vault") (part "236180d848d6139a670b325ea6854c9"))
    )
    (comp (ref "C288")
      (value "0.1uF")
      (footprint "FP-GRM15-MFG")
      (description "CAP CER 0.1UF 16V X7R 0402")
      (fields (field (name "MANUFACTURER PART NUMBER") "GRM155R71C104KA88D") (field (name "TOLERANCE") "10%"))
      (libsource (lib "Altium Content Vault") (part "236180d848d6139a670b325ea6854c9"))
    )
    (comp (ref "C289")
      (value "10uF")
      (footprint "FP-GRM21B-0_1-IPC_C")
      (description "Chip Multilayer Ceramic Capacitors for General Purpose, 0805, 10uF, X5R, 15%, 10%, 16V")
      (fields (field (name "TOLERANCE") "10%") (field (name "VOLTAGE") "16V"))
      (libsource (lib "Altium Content Vault") (part "b4654b650e69147ec39a6b967a45e02"))
    )
    (comp (ref "C290")
      (value "10uF")
      (footprint "FP-GRM21B-0_1-IPC_C")
      (description "Chip Multilayer Ceramic Capacitors for General Purpose, 0805, 10uF, X5R, 15%, 10%, 16V")
      (fields (field (name "TOLERANCE") "10%") (field (name "VOLTAGE") "16V"))
      (libsource (lib "Altium Content Vault") (part "b4654b650e69147ec39a6b967a45e02"))
    )
    (comp (ref "C291")
      (value "0.1uF")
      (footprint "FP-GRM15-MFG")
      (description "CAP CER 0.1UF 16V X7R 0402")
      (fields (field (name "MANUFACTURER PART NUMBER") "GRM155R71C104KA88D") (field (name "TOLERANCE") "10%"))
      (libsource (lib "Altium Content Vault") (part "236180d848d6139a670b325ea6854c9"))
    )
    (comp (ref "C292")
      (value "0.1uF")
      (footprint "FP-GRM15-MFG")
      (description "CAP CER 0.1UF 16V X7R 0402")
      (fields (field (name "MANUFACTURER PART NUMBER") "GRM155R71C104KA88D") (field (name "TOLERANCE") "10%"))
      (libsource (lib "Altium Content Vault") (part "236180d848d6139a670b325ea6854c9"))
    )
    (comp (ref "C293")
      (value "0.1uF")
      (footprint "FP-GRM15-MFG")
      (description "CAP CER 0.1UF 16V X7R 0402")
      (fields (field (name "MANUFACTURER PART NUMBER") "GRM155R71C104KA88D") (field (name "TOLERANCE") "10%"))
      (libsource (lib "Altium Content Vault") (part "236180d848d6139a670b325ea6854c9"))
    )
    (comp (ref "C294")
      (value "0.1uF")
      (footprint "FP-GRM15-MFG")
      (description "CAP CER 0.1UF 16V X7R 0402")
      (fields (field (name "MANUFACTURER PART NUMBER") "GRM155R71C104KA88D") (field (name "TOLERANCE") "10%"))
      (libsource (lib "Altium Content Vault") (part "236180d848d6139a670b325ea6854c9"))
    )
    (comp (ref "C295")
      (value "0.1uF")
      (footprint "FP-GRM15-MFG")
      (description "CAP CER 0.1UF 16V X7R 0402")
      (fields (field (name "MANUFACTURER PART NUMBER") "GRM155R71C104KA88D") (field (name "TOLERANCE") "10%"))
      (libsource (lib "Altium Content Vault") (part "236180d848d6139a670b325ea6854c9"))
    )
    (comp (ref "C296")
      (value "0.1uF")
      (footprint "FP-GRM15-MFG")
      (description "CAP CER 0.1UF 16V X7R 0402")
      (fields (field (name "MANUFACTURER PART NUMBER") "GRM155R71C104KA88D") (field (name "TOLERANCE") "10%"))
      (libsource (lib "Altium Content Vault") (part "236180d848d6139a670b325ea6854c9"))
    )
    (comp (ref "C297")
      (value "0.1uF")
      (footprint "FP-GRM15-MFG")
      (description "CAP CER 0.1UF 16V X7R 0402")
      (fields (field (name "MANUFACTURER PART NUMBER") "GRM155R71C104KA88D") (field (name "TOLERANCE") "10%"))
      (libsource (lib "Altium Content Vault") (part "236180d848d6139a670b325ea6854c9"))
    )
    (comp (ref "C298")
      (value "0.1uF")
      (footprint "FP-GRM15-MFG")
      (description "CAP CER 0.1UF 16V X7R 0402")
      (fields (field (name "MANUFACTURER PART NUMBER") "GRM155R71C104KA88D") (field (name "TOLERANCE") "10%"))
      (libsource (lib "Altium Content Vault") (part "236180d848d6139a670b325ea6854c9"))
    )
    (comp (ref "C299")
      (value "10uF")
      (footprint "FP-GRM21B-0_1-IPC_C")
      (description "Chip Multilayer Ceramic Capacitors for General Purpose, 0805, 10uF, X5R, 15%, 10%, 16V")
      (fields (field (name "TOLERANCE") "10%") (field (name "VOLTAGE") "16V"))
      (libsource (lib "Altium Content Vault") (part "b4654b650e69147ec39a6b967a45e02"))
    )
    (comp (ref "C300")
      (value "10uF")
      (footprint "FP-GRM21B-0_1-IPC_C")
      (description "Chip Multilayer Ceramic Capacitors for General Purpose, 0805, 10uF, X5R, 15%, 10%, 16V")
      (fields (field (name "TOLERANCE") "10%") (field (name "VOLTAGE") "16V"))
      (libsource (lib "Altium Content Vault") (part "b4654b650e69147ec39a6b967a45e02"))
    )
    (comp (ref "C301")
      (value "0.1uF")
      (footprint "FP-GRM15-MFG")
      (description "CAP CER 0.1UF 16V X7R 0402")
      (fields (field (name "MANUFACTURER PART NUMBER") "GRM155R71C104KA88D") (field (name "TOLERANCE") "10%"))
      (libsource (lib "Altium Content Vault") (part "236180d848d6139a670b325ea6854c9"))
    )
    (comp (ref "C302")
      (value "0.1uF")
      (footprint "FP-GRM15-MFG")
      (description "CAP CER 0.1UF 16V X7R 0402")
      (fields (field (name "MANUFACTURER PART NUMBER") "GRM155R71C104KA88D") (field (name "TOLERANCE") "10%"))
      (libsource (lib "Altium Content Vault") (part "236180d848d6139a670b325ea6854c9"))
    )
    (comp (ref "C303")
      (value "0.1uF")
      (footprint "FP-GRM15-MFG")
      (description "CAP CER 0.1UF 16V X7R 0402")
      (fields (field (name "MANUFACTURER PART NUMBER") "GRM155R71C104KA88D") (field (name "TOLERANCE") "10%"))
      (libsource (lib "Altium Content Vault") (part "236180d848d6139a670b325ea6854c9"))
    )
    (comp (ref "C304")
      (value "0.1uF")
      (footprint "FP-GRM15-MFG")
      (description "CAP CER 0.1UF 16V X7R 0402")
      (fields (field (name "MANUFACTURER PART NUMBER") "GRM155R71C104KA88D") (field (name "TOLERANCE") "10%"))
      (libsource (lib "Altium Content Vault") (part "236180d848d6139a670b325ea6854c9"))
    )
    (comp (ref "C305")
      (value "0.1uF")
      (footprint "FP-GRM15-MFG")
      (description "CAP CER 0.1UF 16V X7R 0402")
      (fields (field (name "MANUFACTURER PART NUMBER") "GRM155R71C104KA88D") (field (name "TOLERANCE") "10%"))
      (libsource (lib "Altium Content Vault") (part "236180d848d6139a670b325ea6854c9"))
    )
    (comp (ref "C306")
      (value "0.1uF")
      (footprint "FP-GRM15-MFG")
      (description "CAP CER 0.1UF 16V X7R 0402")
      (fields (field (name "MANUFACTURER PART NUMBER") "GRM155R71C104KA88D") (field (name "TOLERANCE") "10%"))
      (libsource (lib "Altium Content Vault") (part "236180d848d6139a670b325ea6854c9"))
    )
    (comp (ref "C307")
      (value "0.1uF")
      (footprint "FP-GRM15-MFG")
      (description "CAP CER 0.1UF 16V X7R 0402")
      (fields (field (name "MANUFACTURER PART NUMBER") "GRM155R71C104KA88D") (field (name "TOLERANCE") "10%"))
      (libsource (lib "Altium Content Vault") (part "236180d848d6139a670b325ea6854c9"))
    )
    (comp (ref "C308")
      (value "0.1uF")
      (footprint "FP-GRM15-MFG")
      (description "CAP CER 0.1UF 16V X7R 0402")
      (fields (field (name "MANUFACTURER PART NUMBER") "GRM155R71C104KA88D") (field (name "TOLERANCE") "10%"))
      (libsource (lib "Altium Content Vault") (part "236180d848d6139a670b325ea6854c9"))
    )
    (comp (ref "C309")
      (value "0.1uF")
      (footprint "FP-GRM15-MFG")
      (description "CAP CER 0.1UF 16V X7R 0402")
      (fields (field (name "MANUFACTURER PART NUMBER") "GRM155R71C104KA88D") (field (name "TOLERANCE") "10%"))
      (libsource (lib "Altium Content Vault") (part "236180d848d6139a670b325ea6854c9"))
    )
    (comp (ref "C310")
      (value "0.1uF")
      (footprint "FP-GRM15-MFG")
      (description "CAP CER 0.1UF 16V X7R 0402")
      (fields (field (name "MANUFACTURER PART NUMBER") "GRM155R71C104KA88D") (field (name "TOLERANCE") "10%"))
      (libsource (lib "Altium Content Vault") (part "236180d848d6139a670b325ea6854c9"))
    )
    (comp (ref "C311")
      (value "0.1uF")
      (footprint "FP-GRM15-MFG")
      (description "CAP CER 0.1UF 16V X7R 0402")
      (fields (field (name "MANUFACTURER PART NUMBER") "GRM155R71C104KA88D") (field (name "TOLERANCE") "10%"))
      (libsource (lib "Altium Content Vault") (part "236180d848d6139a670b325ea6854c9"))
    )
    (comp (ref "C312")
      (value "0.1uF")
      (footprint "FP-GRM15-MFG")
      (description "CAP CER 0.1UF 16V X7R 0402")
      (fields (field (name "MANUFACTURER PART NUMBER") "GRM155R71C104KA88D") (field (name "TOLERANCE") "10%"))
      (libsource (lib "Altium Content Vault") (part "236180d848d6139a670b325ea6854c9"))
    )
    (comp (ref "C313")
      (value "0.1uF")
      (footprint "FP-GRM15-MFG")
      (description "CAP CER 0.1UF 16V X7R 0402")
      (fields (field (name "MANUFACTURER PART NUMBER") "GRM155R71C104KA88D") (field (name "TOLERANCE") "10%"))
      (libsource (lib "Altium Content Vault") (part "236180d848d6139a670b325ea6854c9"))
    )
    (comp (ref "C314")
      (value "0.1uF")
      (footprint "FP-GRM15-MFG")
      (description "CAP CER 0.1UF 16V X7R 0402")
      (fields (field (name "MANUFACTURER PART NUMBER") "GRM155R71C104KA88D") (field (name "TOLERANCE") "10%"))
      (libsource (lib "Altium Content Vault") (part "236180d848d6139a670b325ea6854c9"))
    )
    (comp (ref "C315")
      (value "10uF")
      (footprint "FP-GRM21B-0_1-IPC_C")
      (description "Chip Multilayer Ceramic Capacitors for General Purpose, 0805, 10uF, X5R, 15%, 10%, 16V")
      (fields (field (name "TOLERANCE") "10%") (field (name "VOLTAGE") "16V"))
      (libsource (lib "Altium Content Vault") (part "b4654b650e69147ec39a6b967a45e02"))
    )
    (comp (ref "C316")
      (value "10uF")
      (footprint "FP-GRM21B-0_1-IPC_C")
      (description "Chip Multilayer Ceramic Capacitors for General Purpose, 0805, 10uF, X5R, 15%, 10%, 16V")
      (fields (field (name "TOLERANCE") "10%") (field (name "VOLTAGE") "16V"))
      (libsource (lib "Altium Content Vault") (part "b4654b650e69147ec39a6b967a45e02"))
    )
    (comp (ref "C317")
      (value "0.1uF")
      (footprint "FP-GRM15-MFG")
      (description "CAP CER 0.1UF 16V X7R 0402")
      (fields (field (name "MANUFACTURER PART NUMBER") "GRM155R71C104KA88D") (field (name "TOLERANCE") "10%"))
      (libsource (lib "Altium Content Vault") (part "236180d848d6139a670b325ea6854c9"))
    )
    (comp (ref "C318")
      (value "0.1uF")
      (footprint "FP-GRM15-MFG")
      (description "CAP CER 0.1UF 16V X7R 0402")
      (fields (field (name "MANUFACTURER PART NUMBER") "GRM155R71C104KA88D") (field (name "TOLERANCE") "10%"))
      (libsource (lib "Altium Content Vault") (part "236180d848d6139a670b325ea6854c9"))
    )
    (comp (ref "C319")
      (value "0.1uF")
      (footprint "FP-GRM15-MFG")
      (description "CAP CER 0.1UF 16V X7R 0402")
      (fields (field (name "MANUFACTURER PART NUMBER") "GRM155R71C104KA88D") (field (name "TOLERANCE") "10%"))
      (libsource (lib "Altium Content Vault") (part "236180d848d6139a670b325ea6854c9"))
    )
    (comp (ref "C320")
      (value "0.1uF")
      (footprint "FP-GRM15-MFG")
      (description "CAP CER 0.1UF 16V X7R 0402")
      (fields (field (name "MANUFACTURER PART NUMBER") "GRM155R71C104KA88D") (field (name "TOLERANCE") "10%"))
      (libsource (lib "Altium Content Vault") (part "236180d848d6139a670b325ea6854c9"))
    )
    (comp (ref "C321")
      (value "0.1uF")
      (footprint "FP-GRM15-MFG")
      (description "CAP CER 0.1UF 16V X7R 0402")
      (fields (field (name "MANUFACTURER PART NUMBER") "GRM155R71C104KA88D") (field (name "TOLERANCE") "10%"))
      (libsource (lib "Altium Content Vault") (part "236180d848d6139a670b325ea6854c9"))
    )
    (comp (ref "C322")
      (value "0.1uF")
      (footprint "FP-GRM15-MFG")
      (description "CAP CER 0.1UF 16V X7R 0402")
      (fields (field (name "MANUFACTURER PART NUMBER") "GRM155R71C104KA88D") (field (name "TOLERANCE") "10%"))
      (libsource (lib "Altium Content Vault") (part "236180d848d6139a670b325ea6854c9"))
    )
    (comp (ref "C323")
      (value "0.1uF")
      (footprint "FP-GRM15-MFG")
      (description "CAP CER 0.1UF 16V X7R 0402")
      (fields (field (name "MANUFACTURER PART NUMBER") "GRM155R71C104KA88D") (field (name "TOLERANCE") "10%"))
      (libsource (lib "Altium Content Vault") (part "236180d848d6139a670b325ea6854c9"))
    )
    (comp (ref "C324")
      (value "0.1uF")
      (footprint "FP-GRM15-MFG")
      (description "CAP CER 0.1UF 16V X7R 0402")
      (fields (field (name "MANUFACTURER PART NUMBER") "GRM155R71C104KA88D") (field (name "TOLERANCE") "10%"))
      (libsource (lib "Altium Content Vault") (part "236180d848d6139a670b325ea6854c9"))
    )
    (comp (ref "C325")
      (value "10uF")
      (footprint "FP-GRM21B-0_1-IPC_C")
      (description "Chip Multilayer Ceramic Capacitors for General Purpose, 0805, 10uF, X5R, 15%, 10%, 16V")
      (fields (field (name "TOLERANCE") "10%") (field (name "VOLTAGE") "16V"))
      (libsource (lib "Altium Content Vault") (part "b4654b650e69147ec39a6b967a45e02"))
    )
    (comp (ref "C326")
      (value "10uF")
      (footprint "FP-GRM21B-0_1-IPC_C")
      (description "Chip Multilayer Ceramic Capacitors for General Purpose, 0805, 10uF, X5R, 15%, 10%, 16V")
      (fields (field (name "TOLERANCE") "10%") (field (name "VOLTAGE") "16V"))
      (libsource (lib "Altium Content Vault") (part "b4654b650e69147ec39a6b967a45e02"))
    )
    (comp (ref "C327")
      (value "0.1uF")
      (footprint "FP-GRM15-MFG")
      (description "CAP CER 0.1UF 16V X7R 0402")
      (fields (field (name "MANUFACTURER PART NUMBER") "GRM155R71C104KA88D") (field (name "TOLERANCE") "10%"))
      (libsource (lib "Altium Content Vault") (part "236180d848d6139a670b325ea6854c9"))
    )
    (comp (ref "C328")
      (value "0.1uF")
      (footprint "FP-GRM15-MFG")
      (description "CAP CER 0.1UF 16V X7R 0402")
      (fields (field (name "MANUFACTURER PART NUMBER") "GRM155R71C104KA88D") (field (name "TOLERANCE") "10%"))
      (libsource (lib "Altium Content Vault") (part "236180d848d6139a670b325ea6854c9"))
    )
    (comp (ref "C329")
      (value "0.1uF")
      (footprint "FP-GRM15-MFG")
      (description "CAP CER 0.1UF 16V X7R 0402")
      (fields (field (name "MANUFACTURER PART NUMBER") "GRM155R71C104KA88D") (field (name "TOLERANCE") "10%"))
      (libsource (lib "Altium Content Vault") (part "236180d848d6139a670b325ea6854c9"))
    )
    (comp (ref "C330")
      (value "0.1uF")
      (footprint "FP-GRM15-MFG")
      (description "CAP CER 0.1UF 16V X7R 0402")
      (fields (field (name "MANUFACTURER PART NUMBER") "GRM155R71C104KA88D") (field (name "TOLERANCE") "10%"))
      (libsource (lib "Altium Content Vault") (part "236180d848d6139a670b325ea6854c9"))
    )
    (comp (ref "C331")
      (value "10uF")
      (footprint "FP-GRM21B-0_1-IPC_C")
      (description "Chip Multilayer Ceramic Capacitors for General Purpose, 0805, 10uF, X5R, 15%, 10%, 16V")
      (fields (field (name "TOLERANCE") "10%") (field (name "VOLTAGE") "16V"))
      (libsource (lib "Altium Content Vault") (part "b4654b650e69147ec39a6b967a45e02"))
    )
    (comp (ref "C332")
      (value "4.7uF")
      (footprint "FP-GRM155-0_1-IPC_B")
      (description "Chip Multilayer Ceramic Capacitors for General Purpose, 0402, 4.7uF, X5R, 15%, 20%, 6.3V")
      (fields (field (name "VOLTAGE") "6.3V") (field (name "TOLERANCE") "20%"))
      (libsource (lib "Altium Content Vault") (part "11868f565c42a9108669ba33697ecf6"))
    )
    (comp (ref "IC1")
      (value "LS1043ASN8QQB")
      (footprint "SamacSys:BGA780C80P28X28_2300X2300X261")
      (description "Integrated Circuit")
      (fields (field (name "MOUSER PART NUMBER") "771-LS1043ASN8QQB"))
      (libsource (lib "SamacSys") (part "LS1043ASN8QQB"))
    )
    (comp (ref "IC16")
      (value "MT40A512M8SA-062E_F_TR")
      (footprint "SamacSys:BGA78C80P9X13_750X1100X120")
      (description "Integrated Circuit")
      (fields
        (field (name "MANUFACTURER_PART_NUMBER") "MT40A512M8SA-062E:F TR")
        (field (name "MOUSER PART NUMBER") "340-402508-REEL")
      )
      (libsource (lib "SamacSys") (part "MT40A512M8SA-062E_F_TR"))
    )
    (comp (ref "IC17")
      (value "MT40A512M8SA-062E_F_TR")
      (footprint "SamacSys:BGA78C80P9X13_750X1100X120")
      (description "Integrated Circuit")
      (fields
        (field (name "MANUFACTURER_PART_NUMBER") "MT40A512M8SA-062E:F TR")
        (field (name "MOUSER PART NUMBER") "340-402508-REEL")
      )
      (libsource (lib "SamacSys") (part "MT40A512M8SA-062E_F_TR"))
    )
    (comp (ref "IC18")
      (value "MT40A512M8SA-062E_F_TR")
      (footprint "SamacSys:BGA78C80P9X13_750X1100X120")
      (description "Integrated Circuit")
      (fields
        (field (name "MANUFACTURER_PART_NUMBER") "MT40A512M8SA-062E:F TR")
        (field (name "MOUSER PART NUMBER") "340-402508-REEL")
      )
      (libsource (lib "SamacSys") (part "MT40A512M8SA-062E_F_TR"))
    )
    (comp (ref "IC19")
      (value "MT40A512M8SA-062E_F_TR")
      (footprint "SamacSys:BGA78C80P9X13_750X1100X120")
      (description "Integrated Circuit")
      (fields
        (field (name "MANUFACTURER_PART_NUMBER") "MT40A512M8SA-062E:F TR")
        (field (name "MOUSER PART NUMBER") "340-402508-REEL")
      )
      (libsource (lib "SamacSys") (part "MT40A512M8SA-062E_F_TR"))
    )
    (comp (ref "IC20")
      (value "MT40A512M8SA-062E_F_TR")
      (footprint "SamacSys:BGA78C80P9X13_750X1100X120")
      (description "Integrated Circuit")
      (fields
        (field (name "MANUFACTURER_PART_NUMBER") "MT40A512M8SA-062E:F TR")
        (field (name "MOUSER PART NUMBER") "340-402508-REEL")
      )
      (libsource (lib "SamacSys") (part "MT40A512M8SA-062E_F_TR"))
    )
    (comp (ref "IC21")
      (value "MT40A512M8SA-062E_F_TR")
      (footprint "SamacSys:BGA78C80P9X13_750X1100X120")
      (description "Integrated Circuit")
      (fields
        (field (name "MANUFACTURER_PART_NUMBER") "MT40A512M8SA-062E:F TR")
        (field (name "MOUSER PART NUMBER") "340-402508-REEL")
      )
      (libsource (lib "SamacSys") (part "MT40A512M8SA-062E_F_TR"))
    )
    (comp (ref "IC22")
      (value "MT40A512M8SA-062E_F_TR")
      (footprint "SamacSys:BGA78C80P9X13_750X1100X120")
      (description "Integrated Circuit")
      (fields
        (field (name "MANUFACTURER_PART_NUMBER") "MT40A512M8SA-062E:F TR")
        (field (name "MOUSER PART NUMBER") "340-402508-REEL")
      )
      (libsource (lib "SamacSys") (part "MT40A512M8SA-062E_F_TR"))
    )
    (comp (ref "IC23")
      (value "MT40A512M8SA-062E_F_TR")
      (footprint "SamacSys:BGA78C80P9X13_750X1100X120")
      (description "Integrated Circuit")
      (fields
        (field (name "MANUFACTURER_PART_NUMBER") "MT40A512M8SA-062E:F TR")
        (field (name "MOUSER PART NUMBER") "340-402508-REEL")
      )
      (libsource (lib "SamacSys") (part "MT40A512M8SA-062E_F_TR"))
    )
    (comp (ref "IC24")
      (value "AT24C04C-SSHM-T")
      (footprint "SamacSys:SOIC127P600X175-8N")
      (description "Integrated Circuit")
      (fields (field (name "MOUSER PART NUMBER") "556-AT24C04C-SSHM-T"))
      (libsource (lib "*") (part "AT24C04C-SSHM-T"))
    )
    (comp (ref "R135")
      (value "240")
      (footprint "RESC1005X40X25ML05T05")
      (fields (field (name "MANUFACTURER") "Vishay Dale") (field (name "PART NUMBER") "CRCW0402240RFKED"))
      (libsource (lib "Altium Content Vault") (part "RES"))
    )
    (comp (ref "R136")
      (value "240")
      (footprint "RESC1005X40X25ML05T05")
      (fields (field (name "MANUFACTURER") "Vishay Dale") (field (name "PART NUMBER") "CRCW0402240RFKED"))
      (libsource (lib "Altium Content Vault") (part "RES"))
    )
    (comp (ref "R137")
      (value "240")
      (footprint "RESC1005X40X25ML05T05")
      (fields (field (name "MANUFACTURER") "Vishay Dale") (field (name "PART NUMBER") "CRCW0402240RFKED"))
      (libsource (lib "Altium Content Vault") (part "RES"))
    )
    (comp (ref "R138")
      (value "240")
      (footprint "RESC1005X40X25ML05T05")
      (fields (field (name "MANUFACTURER") "Vishay Dale") (field (name "PART NUMBER") "CRCW0402240RFKED"))
      (libsource (lib "Altium Content Vault") (part "RES"))
    )
    (comp (ref "R139")
      (value "162")
      (footprint "RESC1005X40X25LL05T05")
      (fields (field (name "PART NUMBER") "CRCW0402162RFKED") (field (name "MANUFACTURER") "Vishay Dale"))
      (libsource (lib "Altium Content Vault") (part "RES"))
    )
    (comp (ref "R140")
      (value "162")
      (footprint "RESC1005X40X25LL05T05")
      (fields (field (name "PART NUMBER") "CRCW0402162RFKED") (field (name "MANUFACTURER") "Vishay Dale"))
      (libsource (lib "Altium Content Vault") (part "RES"))
    )
    (comp (ref "R141")
      (value "4.7K")
      (footprint "FP-CRCW0402-e3-IPC_B")
      (description "RES Thick Film, 4.7kΩ, 1%, 0.063W, 100ppm/°C, 0402")
      (fields (field (name "TOLERANCE") "1%"))
      (libsource (lib "Altium Content Vault") (part "1029c3af85768c4190bb7ad29bc67b5"))
    )
    (comp (ref "R142")
      (value "0")
      (footprint "FP-CRCW0402-e3-IPC_C")
      (description "RES Thick Film, 0Ω, 0.063W, 0402")
      (fields (field (name "TOLERANCE") "5%"))
      (libsource (lib "Altium Content Vault") (part "1029c3af85768c4190bb7ad29bc67b5"))
    )
    (comp (ref "R143")
      (value "0")
      (footprint "FP-CRCW0402-e3-IPC_C")
      (description "RES Thick Film, 0Ω, 0.063W, 0402")
      (fields (field (name "TOLERANCE") "5%"))
      (libsource (lib "Altium Content Vault") (part "1029c3af85768c4190bb7ad29bc67b5"))
    )
    (comp (ref "R144")
      (value "4.7K")
      (footprint "RESC1005X40X25LL05T05")
      (description "Chip Resistor, 4.7 KOhm, +/- 1%, 0.1 W, -55 to 155 degC, 0402 (1005 Metric), RoHS, Tape and Reel")
      (fields (field (name "TOLERANCE") "1%") (field (name "PARTNUMBER") "ERJ-2RKF4701X"))
      (libsource (lib "Altium Content Vault") (part "RES-2"))
    )
    (comp (ref "R145")
      (value "4.7K")
      (footprint "RESC1005X40X25LL05T05")
      (description "Chip Resistor, 4.7 KOhm, +/- 1%, 0.1 W, -55 to 155 degC, 0402 (1005 Metric), RoHS, Tape and Reel")
      (fields (field (name "TOLERANCE") "1%") (field (name "PARTNUMBER") "ERJ-2RKF4701X"))
      (libsource (lib "Altium Content Vault") (part "RES-2"))
    )
    (comp (ref "R146")
      (value "36")
      (footprint "RESC1005X40X25ML05T05")
      (fields (field (name "PART NUMBER") "CRCW040236R0FKED") (field (name "MANUFACTURER") "Vishay Dale"))
      (libsource (lib "Altium Content Vault") (part "RES"))
    )
    (comp (ref "R147")
      (value "36")
      (footprint "RESC1005X40X25ML05T05")
      (fields (field (name "PART NUMBER") "CRCW040236R0FKED") (field (name "MANUFACTURER") "Vishay Dale"))
      (libsource (lib "Altium Content Vault") (part "RES"))
    )
    (comp (ref "R148")
      (value "240")
      (footprint "RESC1005X40X25ML05T05")
      (fields (field (name "MANUFACTURER") "Vishay Dale") (field (name "PART NUMBER") "CRCW0402240RFKED"))
      (libsource (lib "Altium Content Vault") (part "RES"))
    )
    (comp (ref "R149")
      (value "240")
      (footprint "RESC1005X40X25ML05T05")
      (fields (field (name "MANUFACTURER") "Vishay Dale") (field (name "PART NUMBER") "CRCW0402240RFKED"))
      (libsource (lib "Altium Content Vault") (part "RES"))
    )
    (comp (ref "R150")
      (value "4.7K")
      (footprint "RESC1005X40X25LL05T05")
      (description "Chip Resistor, 4.7 KOhm, +/- 1%, 0.1 W, -55 to 155 degC, 0402 (1005 Metric), RoHS, Tape and Reel")
      (fields (field (name "TOLERANCE") "1%") (field (name "PARTNUMBER") "ERJ-2RKF4701X"))
      (libsource (lib "Altium Content Vault") (part "RES-2"))
    )
    (comp (ref "R151")
      (value "240")
      (footprint "RESC1005X40X25ML05T05")
      (fields (field (name "MANUFACTURER") "Vishay Dale") (field (name "PART NUMBER") "CRCW0402240RFKED"))
      (libsource (lib "Altium Content Vault") (part "RES"))
    )
    (comp (ref "R152")
      (value "240")
      (footprint "RESC1005X40X25ML05T05")
      (fields (field (name "MANUFACTURER") "Vishay Dale") (field (name "PART NUMBER") "CRCW0402240RFKED"))
      (libsource (lib "Altium Content Vault") (part "RES"))
    )
    (comp (ref "R153")
      (value "39")
      (footprint "RESC1005X40X25LL05T05")
      (fields (field (name "PART NUMBER") "ERJ2RKF39R0X") (field (name "MANUFACTURER") "Panasonic"))
      (libsource (lib "Altium Content Vault") (part "RES"))
    )
    (comp (ref "R154")
      (value "39")
      (footprint "RESC1005X40X25LL05T05")
      (fields (field (name "PART NUMBER") "ERJ2RKF39R0X") (field (name "MANUFACTURER") "Panasonic"))
      (libsource (lib "Altium Content Vault") (part "RES"))
    )
    (comp (ref "R155")
      (value "39")
      (footprint "RESC1005X40X25LL05T05")
      (fields (field (name "PART NUMBER") "ERJ2RKF39R0X") (field (name "MANUFACTURER") "Panasonic"))
      (libsource (lib "Altium Content Vault") (part "RES"))
    )
    (comp (ref "R156")
      (value "39")
      (footprint "RESC1005X40X25LL05T05")
      (fields (field (name "PART NUMBER") "ERJ2RKF39R0X") (field (name "MANUFACTURER") "Panasonic"))
      (libsource (lib "Altium Content Vault") (part "RES"))
    )
    (comp (ref "R157")
      (value "39")
      (footprint "RESC1005X40X25LL05T05")
      (fields (field (name "PART NUMBER") "ERJ2RKF39R0X") (field (name "MANUFACTURER") "Panasonic"))
      (libsource (lib "Altium Content Vault") (part "RES"))
    )
    (comp (ref "R158")
      (value "39")
      (footprint "RESC1005X40X25LL05T05")
      (fields (field (name "PART NUMBER") "ERJ2RKF39R0X") (field (name "MANUFACTURER") "Panasonic"))
      (libsource (lib "Altium Content Vault") (part "RES"))
    )
    (comp (ref "R159")
      (value "39")
      (footprint "RESC1005X40X25LL05T05")
      (fields (field (name "PART NUMBER") "ERJ2RKF39R0X") (field (name "MANUFACTURER") "Panasonic"))
      (libsource (lib "Altium Content Vault") (part "RES"))
    )
    (comp (ref "R160")
      (value "39")
      (footprint "RESC1005X40X25LL05T05")
      (fields (field (name "PART NUMBER") "ERJ2RKF39R0X") (field (name "MANUFACTURER") "Panasonic"))
      (libsource (lib "Altium Content Vault") (part "RES"))
    )
    (comp (ref "R161")
      (value "39")
      (footprint "RESC1005X40X25LL05T05")
      (fields (field (name "PART NUMBER") "ERJ2RKF39R0X") (field (name "MANUFACTURER") "Panasonic"))
      (libsource (lib "Altium Content Vault") (part "RES"))
    )
    (comp (ref "R162")
      (value "39")
      (footprint "RESC1005X40X25LL05T05")
      (fields (field (name "PART NUMBER") "ERJ2RKF39R0X") (field (name "MANUFACTURER") "Panasonic"))
      (libsource (lib "Altium Content Vault") (part "RES"))
    )
    (comp (ref "R163")
      (value "39")
      (footprint "RESC1005X40X25LL05T05")
      (fields (field (name "PART NUMBER") "ERJ2RKF39R0X") (field (name "MANUFACTURER") "Panasonic"))
      (libsource (lib "Altium Content Vault") (part "RES"))
    )
    (comp (ref "R164")
      (value "39")
      (footprint "RESC1005X40X25LL05T05")
      (fields (field (name "PART NUMBER") "ERJ2RKF39R0X") (field (name "MANUFACTURER") "Panasonic"))
      (libsource (lib "Altium Content Vault") (part "RES"))
    )
    (comp (ref "R165")
      (value "39")
      (footprint "RESC1005X40X25LL05T05")
      (fields (field (name "PART NUMBER") "ERJ2RKF39R0X") (field (name "MANUFACTURER") "Panasonic"))
      (libsource (lib "Altium Content Vault") (part "RES"))
    )
    (comp (ref "R166")
      (value "39")
      (footprint "RESC1005X40X25LL05T05")
      (fields (field (name "PART NUMBER") "ERJ2RKF39R0X") (field (name "MANUFACTURER") "Panasonic"))
      (libsource (lib "Altium Content Vault") (part "RES"))
    )
    (comp (ref "R167")
      (value "39")
      (footprint "RESC1005X40X25LL05T05")
      (fields (field (name "PART NUMBER") "ERJ2RKF39R0X") (field (name "MANUFACTURER") "Panasonic"))
      (libsource (lib "Altium Content Vault") (part "RES"))
    )
    (comp (ref "R168")
      (value "39")
      (footprint "RESC1005X40X25LL05T05")
      (fields (field (name "PART NUMBER") "ERJ2RKF39R0X") (field (name "MANUFACTURER") "Panasonic"))
      (libsource (lib "Altium Content Vault") (part "RES"))
    )
    (comp (ref "R169")
      (value "39")
      (footprint "RESC1005X40X25LL05T05")
      (fields (field (name "PART NUMBER") "ERJ2RKF39R0X") (field (name "MANUFACTURER") "Panasonic"))
      (libsource (lib "Altium Content Vault") (part "RES"))
    )
    (comp (ref "R170")
      (value "39")
      (footprint "RESC1005X40X25LL05T05")
      (fields (field (name "PART NUMBER") "ERJ2RKF39R0X") (field (name "MANUFACTURER") "Panasonic"))
      (libsource (lib "Altium Content Vault") (part "RES"))
    )
    (comp (ref "R171")
      (value "39")
      (footprint "RESC1005X40X25LL05T05")
      (fields (field (name "PART NUMBER") "ERJ2RKF39R0X") (field (name "MANUFACTURER") "Panasonic"))
      (libsource (lib "Altium Content Vault") (part "RES"))
    )
    (comp (ref "R172")
      (value "39")
      (footprint "RESC1005X40X25LL05T05")
      (fields (field (name "PART NUMBER") "ERJ2RKF39R0X") (field (name "MANUFACTURER") "Panasonic"))
      (libsource (lib "Altium Content Vault") (part "RES"))
    )
    (comp (ref "R173")
      (value "39")
      (footprint "RESC1005X40X25LL05T05")
      (fields (field (name "PART NUMBER") "ERJ2RKF39R0X") (field (name "MANUFACTURER") "Panasonic"))
      (libsource (lib "Altium Content Vault") (part "RES"))
    )
    (comp (ref "R174")
      (value "39")
      (footprint "RESC1005X40X25LL05T05")
      (fields (field (name "PART NUMBER") "ERJ2RKF39R0X") (field (name "MANUFACTURER") "Panasonic"))
      (libsource (lib "Altium Content Vault") (part "RES"))
    )
    (comp (ref "R175")
      (value "39")
      (footprint "RESC1005X40X25LL05T05")
      (fields (field (name "PART NUMBER") "ERJ2RKF39R0X") (field (name "MANUFACTURER") "Panasonic"))
      (libsource (lib "Altium Content Vault") (part "RES"))
    )
    (comp (ref "R176")
      (value "39")
      (footprint "RESC1005X40X25LL05T05")
      (fields (field (name "PART NUMBER") "ERJ2RKF39R0X") (field (name "MANUFACTURER") "Panasonic"))
      (libsource (lib "Altium Content Vault") (part "RES"))
    )
    (comp (ref "R177")
      (value "39")
      (footprint "RESC1005X40X25LL05T05")
      (fields (field (name "PART NUMBER") "ERJ2RKF39R0X") (field (name "MANUFACTURER") "Panasonic"))
      (libsource (lib "Altium Content Vault") (part "RES"))
    )
    (comp (ref "R178")
      (value "39")
      (footprint "RESC1005X40X25LL05T05")
      (fields (field (name "PART NUMBER") "ERJ2RKF39R0X") (field (name "MANUFACTURER") "Panasonic"))
      (libsource (lib "Altium Content Vault") (part "RES"))
    )
    (comp (ref "R179")
      (value "39")
      (footprint "RESC1005X40X25LL05T05")
      (fields (field (name "PART NUMBER") "ERJ2RKF39R0X") (field (name "MANUFACTURER") "Panasonic"))
      (libsource (lib "Altium Content Vault") (part "RES"))
    )
    (comp (ref "R180")
      (value "39")
      (footprint "RESC1005X40X25LL05T05")
      (fields (field (name "PART NUMBER") "ERJ2RKF39R0X") (field (name "MANUFACTURER") "Panasonic"))
      (libsource (lib "Altium Content Vault") (part "RES"))
    )
    (comp (ref "R181")
      (value "39")
      (footprint "RESC1005X40X25LL05T05")
      (fields (field (name "PART NUMBER") "ERJ2RKF39R0X") (field (name "MANUFACTURER") "Panasonic"))
      (libsource (lib "Altium Content Vault") (part "RES"))
    )
  )
  (nets
    (net (code "1") (name "+2V4_VPP") (class "Default")
      (node (ref "C201") (pin "1") (pinfunction "1_1") (pintype "passive"))
      (node (ref "C202") (pin "1") (pinfunction "1_1") (pintype "passive"))
      (node (ref "C203") (pin "1") (pinfunction "1_1") (pintype "passive"))
      (node (ref "C204") (pin "1") (pinfunction "1_1") (pintype "passive"))
      (node (ref "C205") (pin "1") (pinfunction "1_1") (pintype "passive"))
      (node (ref "C206") (pin "1") (pinfunction "1_1") (pintype "passive"))
      (node (ref "C207") (pin "1") (pinfunction "1_1") (pintype "passive"))
      (node (ref "C208") (pin "1") (pinfunction "1_1") (pintype "passive"))
      (node (ref "C217") (pin "1") (pinfunction "1_1") (pintype "passive"))
      (node (ref "C218") (pin "1") (pinfunction "1_1") (pintype "passive"))
      (node (ref "C219") (pin "1") (pinfunction "1_1") (pintype "passive"))
      (node (ref "C220") (pin "1") (pinfunction "1_1") (pintype "passive"))
      (node (ref "C221") (pin "1") (pinfunction "1_1") (pintype "passive"))
      (node (ref "C222") (pin "1") (pinfunction "1_1") (pintype "passive"))
      (node (ref "C223") (pin "1") (pinfunction "1_1") (pintype "passive"))
      (node (ref "C224") (pin "1") (pinfunction "1_1") (pintype "passive"))
      (node (ref "IC16") (pin "B1") (pinfunction "VPP1_B1") (pintype "passive"))
      (node (ref "IC16") (pin "M9") (pinfunction "VPP2_M9") (pintype "passive"))
      (node (ref "IC17") (pin "B1") (pinfunction "VPP1_B1") (pintype "passive"))
      (node (ref "IC17") (pin "M9") (pinfunction "VPP2_M9") (pintype "passive"))
      (node (ref "IC18") (pin "B1") (pinfunction "VPP1_B1") (pintype "passive"))
      (node (ref "IC18") (pin "M9") (pinfunction "VPP2_M9") (pintype "passive"))
      (node (ref "IC19") (pin "B1") (pinfunction "VPP1_B1") (pintype "passive"))
      (node (ref "IC19") (pin "M9") (pinfunction "VPP2_M9") (pintype "passive"))
      (node (ref "IC20") (pin "B1") (pinfunction "VPP1_B1") (pintype "passive"))
      (node (ref "IC20") (pin "M9") (pinfunction "VPP2_M9") (pintype "passive"))
      (node (ref "IC21") (pin "B1") (pinfunction "VPP1_B1") (pintype "passive"))
      (node (ref "IC21") (pin "M9") (pinfunction "VPP2_M9") (pintype "passive"))
      (node (ref "IC22") (pin "B1") (pinfunction "VPP1_B1") (pintype "passive"))
      (node (ref "IC22") (pin "M9") (pinfunction "VPP2_M9") (pintype "passive"))
      (node (ref "IC23") (pin "B1") (pinfunction "VPP1_B1") (pintype "passive"))
      (node (ref "IC23") (pin "M9") (pinfunction "VPP2_M9") (pintype "passive"))
    )
    (net (code "2") (name "+3V3") (class "Default")
      (node (ref "C226") (pin "1") (pinfunction "1_1") (pintype "passive"))
      (node (ref "IC24") (pin "2") (pinfunction "A1/NC_2") (pintype "passive"))
      (node (ref "IC24") (pin "8") (pinfunction "VCC_8") (pintype "passive"))
    )
    (net (code "3") (name "+GVDD") (class "Default")
      (node (ref "C235") (pin "2") (pinfunction "2_2") (pintype "passive"))
      (node (ref "C236") (pin "2") (pinfunction "2_2") (pintype "passive"))
      (node (ref "C237") (pin "2") (pinfunction "2_2") (pintype "passive"))
      (node (ref "C238") (pin "2") (pinfunction "2_2") (pintype "passive"))
      (node (ref "C239") (pin "2") (pinfunction "2_2") (pintype "passive"))
      (node (ref "C240") (pin "2") (pinfunction "2_2") (pintype "passive"))
      (node (ref "C241") (pin "2") (pinfunction "2_2") (pintype "passive"))
      (node (ref "C242") (pin "2") (pinfunction "2_2") (pintype "passive"))
      (node (ref "C243") (pin "1") (pinfunction "1_1") (pintype "passive"))
      (node (ref "C244") (pin "1") (pinfunction "1_1") (pintype "passive"))
      (node (ref "C245") (pin "2") (pinfunction "2_2") (pintype "passive"))
      (node (ref "C246") (pin "2") (pinfunction "2_2") (pintype "passive"))
      (node (ref "C247") (pin "2") (pinfunction "2_2") (pintype "passive"))
      (node (ref "C248") (pin "2") (pinfunction "2_2") (pintype "passive"))
      (node (ref "C249") (pin "2") (pinfunction "2_2") (pintype "passive"))
      (node (ref "C250") (pin "2") (pinfunction "2_2") (pintype "passive"))
      (node (ref "C251") (pin "2") (pinfunction "2_2") (pintype "passive"))
      (node (ref "C252") (pin "2") (pinfunction "2_2") (pintype "passive"))
      (node (ref "C253") (pin "1") (pinfunction "1_1") (pintype "passive"))
      (node (ref "C254") (pin "1") (pinfunction "1_1") (pintype "passive"))
      (node (ref "C255") (pin "2") (pinfunction "2_2") (pintype "passive"))
      (node (ref "C256") (pin "2") (pinfunction "2_2") (pintype "passive"))
      (node (ref "C257") (pin "2") (pinfunction "2_2") (pintype "passive"))
      (node (ref "C258") (pin "2") (pinfunction "2_2") (pintype "passive"))
      (node (ref "C259") (pin "2") (pinfunction "2_2") (pintype "passive"))
      (node (ref "C260") (pin "2") (pinfunction "2_2") (pintype "passive"))
      (node (ref "C261") (pin "2") (pinfunction "2_2") (pintype "passive"))
      (node (ref "C262") (pin "2") (pinfunction "2_2") (pintype "passive"))
      (node (ref "C263") (pin "1") (pinfunction "1_1") (pintype "passive"))
      (node (ref "C264") (pin "1") (pinfunction "1_1") (pintype "passive"))
      (node (ref "C265") (pin "2") (pinfunction "2_2") (pintype "passive"))
      (node (ref "C266") (pin "2") (pinfunction "2_2") (pintype "passive"))
      (node (ref "C267") (pin "2") (pinfunction "2_2") (pintype "passive"))
      (node (ref "C268") (pin "2") (pinfunction "2_2") (pintype "passive"))
      (node (ref "C269") (pin "2") (pinfunction "2_2") (pintype "passive"))
      (node (ref "C270") (pin "2") (pinfunction "2_2") (pintype "passive"))
      (node (ref "C271") (pin "2") (pinfunction "2_2") (pintype "passive"))
      (node (ref "C272") (pin "2") (pinfunction "2_2") (pintype "passive"))
      (node (ref "C273") (pin "1") (pinfunction "1_1") (pintype "passive"))
      (node (ref "C274") (pin "1") (pinfunction "1_1") (pintype "passive"))
      (node (ref "C281") (pin "2") (pinfunction "2_2") (pintype "passive"))
      (node (ref "C282") (pin "2") (pinfunction "2_2") (pintype "passive"))
      (node (ref "C283") (pin "2") (pinfunction "2_2") (pintype "passive"))
      (node (ref "C284") (pin "2") (pinfunction "2_2") (pintype "passive"))
      (node (ref "C285") (pin "2") (pinfunction "2_2") (pintype "passive"))
      (node (ref "C286") (pin "2") (pinfunction "2_2") (pintype "passive"))
      (node (ref "C287") (pin "2") (pinfunction "2_2") (pintype "passive"))
      (node (ref "C288") (pin "2") (pinfunction "2_2") (pintype "passive"))
      (node (ref "C289") (pin "1") (pinfunction "1_1") (pintype "passive"))
      (node (ref "C290") (pin "1") (pinfunction "1_1") (pintype "passive"))
      (node (ref "C291") (pin "2") (pinfunction "2_2") (pintype "passive"))
      (node (ref "C292") (pin "2") (pinfunction "2_2") (pintype "passive"))
      (node (ref "C293") (pin "2") (pinfunction "2_2") (pintype "passive"))
      (node (ref "C294") (pin "2") (pinfunction "2_2") (pintype "passive"))
      (node (ref "C295") (pin "2") (pinfunction "2_2") (pintype "passive"))
      (node (ref "C296") (pin "2") (pinfunction "2_2") (pintype "passive"))
      (node (ref "C297") (pin "2") (pinfunction "2_2") (pintype "passive"))
      (node (ref "C298") (pin "2") (pinfunction "2_2") (pintype "passive"))
      (node (ref "C299") (pin "1") (pinfunction "1_1") (pintype "passive"))
      (node (ref "C300") (pin "1") (pinfunction "1_1") (pintype "passive"))
      (node (ref "C307") (pin "2") (pinfunction "2_2") (pintype "passive"))
      (node (ref "C308") (pin "2") (pinfunction "2_2") (pintype "passive"))
      (node (ref "C309") (pin "2") (pinfunction "2_2") (pintype "passive"))
      (node (ref "C310") (pin "2") (pinfunction "2_2") (pintype "passive"))
      (node (ref "C311") (pin "2") (pinfunction "2_2") (pintype "passive"))
      (node (ref "C312") (pin "2") (pinfunction "2_2") (pintype "passive"))
      (node (ref "C313") (pin "2") (pinfunction "2_2") (pintype "passive"))
      (node (ref "C314") (pin "2") (pinfunction "2_2") (pintype "passive"))
      (node (ref "C315") (pin "1") (pinfunction "1_1") (pintype "passive"))
      (node (ref "C316") (pin "1") (pinfunction "1_1") (pintype "passive"))
      (node (ref "C317") (pin "2") (pinfunction "2_2") (pintype "passive"))
      (node (ref "C318") (pin "2") (pinfunction "2_2") (pintype "passive"))
      (node (ref "C319") (pin "2") (pinfunction "2_2") (pintype "passive"))
      (node (ref "C320") (pin "2") (pinfunction "2_2") (pintype "passive"))
      (node (ref "C321") (pin "2") (pinfunction "2_2") (pintype "passive"))
      (node (ref "C322") (pin "2") (pinfunction "2_2") (pintype "passive"))
      (node (ref "C323") (pin "2") (pinfunction "2_2") (pintype "passive"))
      (node (ref "C324") (pin "2") (pinfunction "2_2") (pintype "passive"))
      (node (ref "C325") (pin "1") (pinfunction "1_1") (pintype "passive"))
      (node (ref "C326") (pin "1") (pinfunction "1_1") (pintype "passive"))
      (node (ref "IC16") (pin "A1") (pinfunction "VDD1_A1") (pintype "passive"))
      (node (ref "IC16") (pin "B2") (pinfunction "VDDQ1_B2") (pintype "passive"))
      (node (ref "IC16") (pin "B8") (pinfunction "VDDQ2_B8") (pintype "passive"))
      (node (ref "IC16") (pin "C1") (pinfunction "VDDQ3_C1") (pintype "passive"))
      (node (ref "IC16") (pin "C7") (pinfunction "VDD2_C7") (pintype "passive"))
      (node (ref "IC16") (pin "C9") (pinfunction "VDDQ4_C9") (pintype "passive"))
      (node (ref "IC16") (pin "E2") (pinfunction "VDDQ5_E2") (pintype "passive"))
      (node (ref "IC16") (pin "E8") (pinfunction "VDDQ6_E8") (pintype "passive"))
      (node (ref "IC16") (pin "F1") (pinfunction "VDD3_F1") (pintype "passive"))
      (node (ref "IC16") (pin "F9") (pinfunction "VDD4_F9") (pintype "passive"))
      (node (ref "IC16") (pin "H1") (pinfunction "VDD5_H1") (pintype "passive"))
      (node (ref "IC16") (pin "J9") (pinfunction "VDD6_J9") (pintype "passive"))
      (node (ref "IC16") (pin "M1") (pinfunction "VDD7_M1") (pintype "passive"))
      (node (ref "IC16") (pin "N9") (pinfunction "VDD8_N9") (pintype "passive"))
      (node (ref "IC17") (pin "A1") (pinfunction "VDD1_A1") (pintype "passive"))
      (node (ref "IC17") (pin "B2") (pinfunction "VDDQ1_B2") (pintype "passive"))
      (node (ref "IC17") (pin "B8") (pinfunction "VDDQ2_B8") (pintype "passive"))
      (node (ref "IC17") (pin "C1") (pinfunction "VDDQ3_C1") (pintype "passive"))
      (node (ref "IC17") (pin "C7") (pinfunction "VDD2_C7") (pintype "passive"))
      (node (ref "IC17") (pin "C9") (pinfunction "VDDQ4_C9") (pintype "passive"))
      (node (ref "IC17") (pin "E2") (pinfunction "VDDQ5_E2") (pintype "passive"))
      (node (ref "IC17") (pin "E8") (pinfunction "VDDQ6_E8") (pintype "passive"))
      (node (ref "IC17") (pin "F1") (pinfunction "VDD3_F1") (pintype "passive"))
      (node (ref "IC17") (pin "F9") (pinfunction "VDD4_F9") (pintype "passive"))
      (node (ref "IC17") (pin "H1") (pinfunction "VDD5_H1") (pintype "passive"))
      (node (ref "IC17") (pin "J9") (pinfunction "VDD6_J9") (pintype "passive"))
      (node (ref "IC17") (pin "M1") (pinfunction "VDD7_M1") (pintype "passive"))
      (node (ref "IC17") (pin "N9") (pinfunction "VDD8_N9") (pintype "passive"))
      (node (ref "IC18") (pin "A1") (pinfunction "VDD1_A1") (pintype "passive"))
      (node (ref "IC18") (pin "B2") (pinfunction "VDDQ1_B2") (pintype "passive"))
      (node (ref "IC18") (pin "B8") (pinfunction "VDDQ2_B8") (pintype "passive"))
      (node (ref "IC18") (pin "C1") (pinfunction "VDDQ3_C1") (pintype "passive"))
      (node (ref "IC18") (pin "C7") (pinfunction "VDD2_C7") (pintype "passive"))
      (node (ref "IC18") (pin "C9") (pinfunction "VDDQ4_C9") (pintype "passive"))
      (node (ref "IC18") (pin "E2") (pinfunction "VDDQ5_E2") (pintype "passive"))
      (node (ref "IC18") (pin "E8") (pinfunction "VDDQ6_E8") (pintype "passive"))
      (node (ref "IC18") (pin "F1") (pinfunction "VDD3_F1") (pintype "passive"))
      (node (ref "IC18") (pin "F9") (pinfunction "VDD4_F9") (pintype "passive"))
      (node (ref "IC18") (pin "H1") (pinfunction "VDD5_H1") (pintype "passive"))
      (node (ref "IC18") (pin "J9") (pinfunction "VDD6_J9") (pintype "passive"))
      (node (ref "IC18") (pin "M1") (pinfunction "VDD7_M1") (pintype "passive"))
      (node (ref "IC18") (pin "N9") (pinfunction "VDD8_N9") (pintype "passive"))
      (node (ref "IC19") (pin "A1") (pinfunction "VDD1_A1") (pintype "passive"))
      (node (ref "IC19") (pin "B2") (pinfunction "VDDQ1_B2") (pintype "passive"))
      (node (ref "IC19") (pin "B8") (pinfunction "VDDQ2_B8") (pintype "passive"))
      (node (ref "IC19") (pin "C1") (pinfunction "VDDQ3_C1") (pintype "passive"))
      (node (ref "IC19") (pin "C7") (pinfunction "VDD2_C7") (pintype "passive"))
      (node (ref "IC19") (pin "C9") (pinfunction "VDDQ4_C9") (pintype "passive"))
      (node (ref "IC19") (pin "E2") (pinfunction "VDDQ5_E2") (pintype "passive"))
      (node (ref "IC19") (pin "E8") (pinfunction "VDDQ6_E8") (pintype "passive"))
      (node (ref "IC19") (pin "F1") (pinfunction "VDD3_F1") (pintype "passive"))
      (node (ref "IC19") (pin "F9") (pinfunction "VDD4_F9") (pintype "passive"))
      (node (ref "IC19") (pin "H1") (pinfunction "VDD5_H1") (pintype "passive"))
      (node (ref "IC19") (pin "J9") (pinfunction "VDD6_J9") (pintype "passive"))
      (node (ref "IC19") (pin "M1") (pinfunction "VDD7_M1") (pintype "passive"))
      (node (ref "IC19") (pin "N9") (pinfunction "VDD8_N9") (pintype "passive"))
      (node (ref "IC20") (pin "A1") (pinfunction "VDD1_A1") (pintype "passive"))
      (node (ref "IC20") (pin "B2") (pinfunction "VDDQ1_B2") (pintype "passive"))
      (node (ref "IC20") (pin "B8") (pinfunction "VDDQ2_B8") (pintype "passive"))
      (node (ref "IC20") (pin "C1") (pinfunction "VDDQ3_C1") (pintype "passive"))
      (node (ref "IC20") (pin "C7") (pinfunction "VDD2_C7") (pintype "passive"))
      (node (ref "IC20") (pin "C9") (pinfunction "VDDQ4_C9") (pintype "passive"))
      (node (ref "IC20") (pin "E2") (pinfunction "VDDQ5_E2") (pintype "passive"))
      (node (ref "IC20") (pin "E8") (pinfunction "VDDQ6_E8") (pintype "passive"))
      (node (ref "IC20") (pin "F1") (pinfunction "VDD3_F1") (pintype "passive"))
      (node (ref "IC20") (pin "F9") (pinfunction "VDD4_F9") (pintype "passive"))
      (node (ref "IC20") (pin "H1") (pinfunction "VDD5_H1") (pintype "passive"))
      (node (ref "IC20") (pin "J9") (pinfunction "VDD6_J9") (pintype "passive"))
      (node (ref "IC20") (pin "M1") (pinfunction "VDD7_M1") (pintype "passive"))
      (node (ref "IC20") (pin "N9") (pinfunction "VDD8_N9") (pintype "passive"))
      (node (ref "IC21") (pin "A1") (pinfunction "VDD1_A1") (pintype "passive"))
      (node (ref "IC21") (pin "B2") (pinfunction "VDDQ1_B2") (pintype "passive"))
      (node (ref "IC21") (pin "B8") (pinfunction "VDDQ2_B8") (pintype "passive"))
      (node (ref "IC21") (pin "C1") (pinfunction "VDDQ3_C1") (pintype "passive"))
      (node (ref "IC21") (pin "C7") (pinfunction "VDD2_C7") (pintype "passive"))
      (node (ref "IC21") (pin "C9") (pinfunction "VDDQ4_C9") (pintype "passive"))
      (node (ref "IC21") (pin "E2") (pinfunction "VDDQ5_E2") (pintype "passive"))
      (node (ref "IC21") (pin "E8") (pinfunction "VDDQ6_E8") (pintype "passive"))
      (node (ref "IC21") (pin "F1") (pinfunction "VDD3_F1") (pintype "passive"))
      (node (ref "IC21") (pin "F9") (pinfunction "VDD4_F9") (pintype "passive"))
      (node (ref "IC21") (pin "H1") (pinfunction "VDD5_H1") (pintype "passive"))
      (node (ref "IC21") (pin "J9") (pinfunction "VDD6_J9") (pintype "passive"))
      (node (ref "IC21") (pin "M1") (pinfunction "VDD7_M1") (pintype "passive"))
      (node (ref "IC21") (pin "N9") (pinfunction "VDD8_N9") (pintype "passive"))
      (node (ref "IC22") (pin "A1") (pinfunction "VDD1_A1") (pintype "passive"))
      (node (ref "IC22") (pin "B2") (pinfunction "VDDQ1_B2") (pintype "passive"))
      (node (ref "IC22") (pin "B8") (pinfunction "VDDQ2_B8") (pintype "passive"))
      (node (ref "IC22") (pin "C1") (pinfunction "VDDQ3_C1") (pintype "passive"))
      (node (ref "IC22") (pin "C7") (pinfunction "VDD2_C7") (pintype "passive"))
      (node (ref "IC22") (pin "C9") (pinfunction "VDDQ4_C9") (pintype "passive"))
      (node (ref "IC22") (pin "E2") (pinfunction "VDDQ5_E2") (pintype "passive"))
      (node (ref "IC22") (pin "E8") (pinfunction "VDDQ6_E8") (pintype "passive"))
      (node (ref "IC22") (pin "F1") (pinfunction "VDD3_F1") (pintype "passive"))
      (node (ref "IC22") (pin "F9") (pinfunction "VDD4_F9") (pintype "passive"))
      (node (ref "IC22") (pin "H1") (pinfunction "VDD5_H1") (pintype "passive"))
      (node (ref "IC22") (pin "J9") (pinfunction "VDD6_J9") (pintype "passive"))
      (node (ref "IC22") (pin "M1") (pinfunction "VDD7_M1") (pintype "passive"))
      (node (ref "IC22") (pin "N9") (pinfunction "VDD8_N9") (pintype "passive"))
      (node (ref "IC23") (pin "A1") (pinfunction "VDD1_A1") (pintype "passive"))
      (node (ref "IC23") (pin "B2") (pinfunction "VDDQ1_B2") (pintype "passive"))
      (node (ref "IC23") (pin "B8") (pinfunction "VDDQ2_B8") (pintype "passive"))
      (node (ref "IC23") (pin "C1") (pinfunction "VDDQ3_C1") (pintype "passive"))
      (node (ref "IC23") (pin "C7") (pinfunction "VDD2_C7") (pintype "passive"))
      (node (ref "IC23") (pin "C9") (pinfunction "VDDQ4_C9") (pintype "passive"))
      (node (ref "IC23") (pin "E2") (pinfunction "VDDQ5_E2") (pintype "passive"))
      (node (ref "IC23") (pin "E8") (pinfunction "VDDQ6_E8") (pintype "passive"))
      (node (ref "IC23") (pin "F1") (pinfunction "VDD3_F1") (pintype "passive"))
      (node (ref "IC23") (pin "F9") (pinfunction "VDD4_F9") (pintype "passive"))
      (node (ref "IC23") (pin "H1") (pinfunction "VDD5_H1") (pintype "passive"))
      (node (ref "IC23") (pin "J9") (pinfunction "VDD6_J9") (pintype "passive"))
      (node (ref "IC23") (pin "M1") (pinfunction "VDD7_M1") (pintype "passive"))
      (node (ref "IC23") (pin "N9") (pinfunction "VDD8_N9") (pintype "passive"))
      (node (ref "R139") (pin "1") (pinfunction "1_1") (pintype "passive"))
      (node (ref "R141") (pin "2") (pinfunction "2_2") (pintype "passive"))
      (node (ref "R144") (pin "1") (pinfunction "1_1") (pintype "passive"))
    )
    (net (code "4") (name "/PU _DDR4_ODT0") (class "Default")
      (node (ref "IC23") (pin "F3") (pinfunction "ODT_F3") (pintype "passive"))
    )
    (net (code "5") (name "/PU_ALERT_N") (class "Default")
      (node (ref "IC16") (pin "L9") (pinfunction "~{ALERT}_L9") (pintype "passive"))
      (node (ref "IC17") (pin "L9") (pinfunction "~{ALERT}_L9") (pintype "passive"))
      (node (ref "IC18") (pin "L9") (pinfunction "~{ALERT}_L9") (pintype "passive"))
      (node (ref "IC19") (pin "L9") (pinfunction "~{ALERT}_L9") (pintype "passive"))
      (node (ref "IC20") (pin "L9") (pinfunction "~{ALERT}_L9") (pintype "passive"))
      (node (ref "IC21") (pin "L9") (pinfunction "~{ALERT}_L9") (pintype "passive"))
      (node (ref "IC22") (pin "L9") (pinfunction "~{ALERT}_L9") (pintype "passive"))
      (node (ref "IC23") (pin "L9") (pinfunction "~{ALERT}_L9") (pintype "passive"))
    )
    (net (code "6") (name "/PU_DDR4_A0") (class "Default")
      (node (ref "IC1") (pin "AC25") (pinfunction "D1_MA00_AC25") (pintype "passive"))
      (node (ref "IC16") (pin "L3") (pinfunction "A0_L3") (pintype "passive"))
      (node (ref "IC17") (pin "L3") (pinfunction "A0_L3") (pintype "passive"))
      (node (ref "IC18") (pin "L3") (pinfunction "A0_L3") (pintype "passive"))
      (node (ref "IC19") (pin "L3") (pinfunction "A0_L3") (pintype "passive"))
      (node (ref "IC20") (pin "L3") (pinfunction "A0_L3") (pintype "passive"))
      (node (ref "IC21") (pin "L3") (pinfunction "A0_L3") (pintype "passive"))
      (node (ref "IC22") (pin "L3") (pinfunction "A0_L3") (pintype "passive"))
      (node (ref "IC23") (pin "L3") (pinfunction "A0_L3") (pintype "passive"))
      (node (ref "R156") (pin "1") (pinfunction "1_1") (pintype "passive"))
    )
    (net (code "7") (name "/PU_DDR4_A1") (class "Default")
      (node (ref "IC1") (pin "AA21") (pinfunction "D1_MA01_AA21") (pintype "passive"))
      (node (ref "IC16") (pin "L7") (pinfunction "A1_L7") (pintype "passive"))
      (node (ref "IC17") (pin "L7") (pinfunction "A1_L7") (pintype "passive"))
      (node (ref "IC18") (pin "L7") (pinfunction "A1_L7") (pintype "passive"))
      (node (ref "IC19") (pin "L7") (pinfunction "A1_L7") (pintype "passive"))
      (node (ref "IC20") (pin "L7") (pinfunction "A1_L7") (pintype "passive"))
      (node (ref "IC21") (pin "L7") (pinfunction "A1_L7") (pintype "passive"))
      (node (ref "IC22") (pin "L7") (pinfunction "A1_L7") (pintype "passive"))
      (node (ref "IC23") (pin "L7") (pinfunction "A1_L7") (pintype "passive"))
      (node (ref "R157") (pin "1") (pinfunction "1_1") (pintype "passive"))
    )
    (net (code "8") (name "/PU_DDR4_A2") (class "Default")
      (node (ref "IC1") (pin "V23") (pinfunction "D1_MA02_V23") (pintype "passive"))
      (node (ref "IC16") (pin "M3") (pinfunction "A2_M3") (pintype "passive"))
      (node (ref "IC17") (pin "M3") (pinfunction "A2_M3") (pintype "passive"))
      (node (ref "IC18") (pin "M3") (pinfunction "A2_M3") (pintype "passive"))
      (node (ref "IC19") (pin "M3") (pinfunction "A2_M3") (pintype "passive"))
      (node (ref "IC20") (pin "M3") (pinfunction "A2_M3") (pintype "passive"))
      (node (ref "IC21") (pin "M3") (pinfunction "A2_M3") (pintype "passive"))
      (node (ref "IC22") (pin "M3") (pinfunction "A2_M3") (pintype "passive"))
      (node (ref "IC23") (pin "M3") (pinfunction "A2_M3") (pintype "passive"))
      (node (ref "R158") (pin "1") (pinfunction "1_1") (pintype "passive"))
    )
    (net (code "9") (name "/PU_DDR4_A3") (class "Default")
      (node (ref "IC1") (pin "AD23") (pinfunction "D1_MA03_AD23") (pintype "passive"))
      (node (ref "IC16") (pin "K7") (pinfunction "A3_K7") (pintype "passive"))
      (node (ref "IC17") (pin "K7") (pinfunction "A3_K7") (pintype "passive"))
      (node (ref "IC18") (pin "K7") (pinfunction "A3_K7") (pintype "passive"))
      (node (ref "IC19") (pin "K7") (pinfunction "A3_K7") (pintype "passive"))
      (node (ref "IC20") (pin "K7") (pinfunction "A3_K7") (pintype "passive"))
      (node (ref "IC21") (pin "K7") (pinfunction "A3_K7") (pintype "passive"))
      (node (ref "IC22") (pin "K7") (pinfunction "A3_K7") (pintype "passive"))
      (node (ref "IC23") (pin "K7") (pinfunction "A3_K7") (pintype "passive"))
      (node (ref "R159") (pin "1") (pinfunction "1_1") (pintype "passive"))
    )
    (net (code "10") (name "/PU_DDR4_A4") (class "Default")
      (node (ref "IC1") (pin "AA23") (pinfunction "D1_MA04_AA23") (pintype "passive"))
      (node (ref "IC16") (pin "K3") (pinfunction "A4_K3") (pintype "passive"))
      (node (ref "IC17") (pin "K3") (pinfunction "A4_K3") (pintype "passive"))
      (node (ref "IC18") (pin "K3") (pinfunction "A4_K3") (pintype "passive"))
      (node (ref "IC19") (pin "K3") (pinfunction "A4_K3") (pintype "passive"))
      (node (ref "IC20") (pin "K3") (pinfunction "A4_K3") (pintype "passive"))
      (node (ref "IC21") (pin "K3") (pinfunction "A4_K3") (pintype "passive"))
      (node (ref "IC22") (pin "K3") (pinfunction "A4_K3") (pintype "passive"))
      (node (ref "IC23") (pin "K3") (pinfunction "A4_K3") (pintype "passive"))
      (node (ref "R160") (pin "1") (pinfunction "1_1") (pintype "passive"))
    )
    (net (code "11") (name "/PU_DDR4_A5") (class "Default")
      (node (ref "IC1") (pin "W23") (pinfunction "D1_MA05_W23") (pintype "passive"))
      (node (ref "IC16") (pin "L8") (pinfunction "A5_L8") (pintype "passive"))
      (node (ref "IC17") (pin "L8") (pinfunction "A5_L8") (pintype "passive"))
      (node (ref "IC18") (pin "L8") (pinfunction "A5_L8") (pintype "passive"))
      (node (ref "IC19") (pin "L8") (pinfunction "A5_L8") (pintype "passive"))
      (node (ref "IC20") (pin "L8") (pinfunction "A5_L8") (pintype "passive"))
      (node (ref "IC21") (pin "L8") (pinfunction "A5_L8") (pintype "passive"))
      (node (ref "IC22") (pin "L8") (pinfunction "A5_L8") (pintype "passive"))
      (node (ref "IC23") (pin "L8") (pinfunction "A5_L8") (pintype "passive"))
      (node (ref "R161") (pin "1") (pinfunction "1_1") (pintype "passive"))
    )
    (net (code "12") (name "/PU_DDR4_A6") (class "Default")
      (node (ref "IC1") (pin "AC24") (pinfunction "D1_MA06_AC24") (pintype "passive"))
      (node (ref "IC16") (pin "L2") (pinfunction "A6_L2") (pintype "passive"))
      (node (ref "IC17") (pin "L2") (pinfunction "A6_L2") (pintype "passive"))
      (node (ref "IC18") (pin "L2") (pinfunction "A6_L2") (pintype "passive"))
      (node (ref "IC19") (pin "L2") (pinfunction "A6_L2") (pintype "passive"))
      (node (ref "IC20") (pin "L2") (pinfunction "A6_L2") (pintype "passive"))
      (node (ref "IC21") (pin "L2") (pinfunction "A6_L2") (pintype "passive"))
      (node (ref "IC22") (pin "L2") (pinfunction "A6_L2") (pintype "passive"))
      (node (ref "IC23") (pin "L2") (pinfunction "A6_L2") (pintype "passive"))
      (node (ref "R162") (pin "1") (pinfunction "1_1") (pintype "passive"))
    )
    (net (code "13") (name "/PU_DDR4_A7") (class "Default")
      (node (ref "IC1") (pin "U24") (pinfunction "D1_MA07_U24") (pintype "passive"))
      (node (ref "IC16") (pin "M8") (pinfunction "A7_M8") (pintype "passive"))
      (node (ref "IC17") (pin "M8") (pinfunction "A7_M8") (pintype "passive"))
      (node (ref "IC18") (pin "M8") (pinfunction "A7_M8") (pintype "passive"))
      (node (ref "IC19") (pin "M8") (pinfunction "A7_M8") (pintype "passive"))
      (node (ref "IC20") (pin "M8") (pinfunction "A7_M8") (pintype "passive"))
      (node (ref "IC21") (pin "M8") (pinfunction "A7_M8") (pintype "passive"))
      (node (ref "IC22") (pin "M8") (pinfunction "A7_M8") (pintype "passive"))
      (node (ref "IC23") (pin "M8") (pinfunction "A7_M8") (pintype "passive"))
      (node (ref "R163") (pin "1") (pinfunction "1_1") (pintype "passive"))
    )
    (net (code "14") (name "/PU_DDR4_A8") (class "Default")
      (node (ref "IC1") (pin "R22") (pinfunction "D1_MA08_R22") (pintype "passive"))
      (node (ref "IC16") (pin "M2") (pinfunction "A8_M2") (pintype "passive"))
      (node (ref "IC17") (pin "M2") (pinfunction "A8_M2") (pintype "passive"))
      (node (ref "IC18") (pin "M2") (pinfunction "A8_M2") (pintype "passive"))
      (node (ref "IC19") (pin "M2") (pinfunction "A8_M2") (pintype "passive"))
      (node (ref "IC20") (pin "M2") (pinfunction "A8_M2") (pintype "passive"))
      (node (ref "IC21") (pin "M2") (pinfunction "A8_M2") (pintype "passive"))
      (node (ref "IC22") (pin "M2") (pinfunction "A8_M2") (pintype "passive"))
      (node (ref "IC23") (pin "M2") (pinfunction "A8_M2") (pintype "passive"))
      (node (ref "R164") (pin "1") (pinfunction "1_1") (pintype "passive"))
    )
    (net (code "15") (name "/PU_DDR4_A9") (class "Default")
      (node (ref "IC1") (pin "W22") (pinfunction "D1_MA09_W22") (pintype "passive"))
      (node (ref "IC16") (pin "M7") (pinfunction "A9_M7") (pintype "passive"))
      (node (ref "IC17") (pin "M7") (pinfunction "A9_M7") (pintype "passive"))
      (node (ref "IC18") (pin "M7") (pinfunction "A9_M7") (pintype "passive"))
      (node (ref "IC19") (pin "M7") (pinfunction "A9_M7") (pintype "passive"))
      (node (ref "IC20") (pin "M7") (pinfunction "A9_M7") (pintype "passive"))
      (node (ref "IC21") (pin "M7") (pinfunction "A9_M7") (pintype "passive"))
      (node (ref "IC22") (pin "M7") (pinfunction "A9_M7") (pintype "passive"))
      (node (ref "IC23") (pin "M7") (pinfunction "A9_M7") (pintype "passive"))
      (node (ref "R165") (pin "1") (pinfunction "1_1") (pintype "passive"))
    )
    (net (code "16") (name "/PU_DDR4_A10") (class "Default")
      (node (ref "IC1") (pin "AB23") (pinfunction "D1_MA10_AB23") (pintype "passive"))
      (node (ref "IC16") (pin "J3") (pinfunction "A10/AP_J3") (pintype "passive"))
      (node (ref "IC17") (pin "J3") (pinfunction "A10/AP_J3") (pintype "passive"))
      (node (ref "IC18") (pin "J3") (pinfunction "A10/AP_J3") (pintype "passive"))
      (node (ref "IC19") (pin "J3") (pinfunction "A10/AP_J3") (pintype "passive"))
      (node (ref "IC20") (pin "J3") (pinfunction "A10/AP_J3") (pintype "passive"))
      (node (ref "IC21") (pin "J3") (pinfunction "A10/AP_J3") (pintype "passive"))
      (node (ref "IC22") (pin "J3") (pinfunction "A10/AP_J3") (pintype "passive"))
      (node (ref "IC23") (pin "J3") (pinfunction "A10/AP_J3") (pintype "passive"))
      (node (ref "R166") (pin "1") (pinfunction "1_1") (pintype "passive"))
    )
    (net (code "17") (name "/PU_DDR4_A11") (class "Default")
      (node (ref "IC1") (pin "T23") (pinfunction "D1_MA11_T23") (pintype "passive"))
      (node (ref "IC16") (pin "N2") (pinfunction "A11_N2") (pintype "passive"))
      (node (ref "IC17") (pin "N2") (pinfunction "A11_N2") (pintype "passive"))
      (node (ref "IC18") (pin "N2") (pinfunction "A11_N2") (pintype "passive"))
      (node (ref "IC19") (pin "N2") (pinfunction "A11_N2") (pintype "passive"))
      (node (ref "IC20") (pin "N2") (pinfunction "A11_N2") (pintype "passive"))
      (node (ref "IC21") (pin "N2") (pinfunction "A11_N2") (pintype "passive"))
      (node (ref "IC22") (pin "N2") (pinfunction "A11_N2") (pintype "passive"))
      (node (ref "IC23") (pin "N2") (pinfunction "A11_N2") (pintype "passive"))
      (node (ref "R167") (pin "1") (pinfunction "1_1") (pintype "passive"))
    )
    (net (code "18") (name "/PU_DDR4_A12") (class "Default")
      (node (ref "IC1") (pin "AC23") (pinfunction "D1_MA12_AC23") (pintype "passive"))
      (node (ref "IC16") (pin "J7") (pinfunction "A12/~{BC}_J7") (pintype "passive"))
      (node (ref "IC17") (pin "J7") (pinfunction "A12/~{BC}_J7") (pintype "passive"))
      (node (ref "IC18") (pin "J7") (pinfunction "A12/~{BC}_J7") (pintype "passive"))
      (node (ref "IC19") (pin "J7") (pinfunction "A12/~{BC}_J7") (pintype "passive"))
      (node (ref "IC20") (pin "J7") (pinfunction "A12/~{BC}_J7") (pintype "passive"))
      (node (ref "IC21") (pin "J7") (pinfunction "A12/~{BC}_J7") (pintype "passive"))
      (node (ref "IC22") (pin "J7") (pinfunction "A12/~{BC}_J7") (pintype "passive"))
      (node (ref "IC23") (pin "J7") (pinfunction "A12/~{BC}_J7") (pintype "passive"))
      (node (ref "R168") (pin "1") (pinfunction "1_1") (pintype "passive"))
    )
    (net (code "19") (name "/PU_DDR4_A13") (class "Default")
      (node (ref "IC1") (pin "T25") (pinfunction "D1_MA13_T25") (pintype "passive"))
      (node (ref "IC16") (pin "N8") (pinfunction "A13_N8") (pintype "passive"))
      (node (ref "IC17") (pin "N8") (pinfunction "A13_N8") (pintype "passive"))
      (node (ref "IC18") (pin "N8") (pinfunction "A13_N8") (pintype "passive"))
      (node (ref "IC19") (pin "N8") (pinfunction "A13_N8") (pintype "passive"))
      (node (ref "IC20") (pin "N8") (pinfunction "A13_N8") (pintype "passive"))
      (node (ref "IC21") (pin "N8") (pinfunction "A13_N8") (pintype "passive"))
      (node (ref "IC22") (pin "N8") (pinfunction "A13_N8") (pintype "passive"))
      (node (ref "IC23") (pin "N8") (pinfunction "A13_N8") (pintype "passive"))
      (node (ref "R169") (pin "1") (pinfunction "1_1") (pintype "passive"))
    )
    (net (code "20") (name "/PU_DDR4_A14") (class "Default")
      (node (ref "IC1") (pin "AE22") (pinfunction "D1_MA14_AE22") (pintype "passive"))
      (node (ref "IC16") (pin "J8") (pinfunction "BG1_J8") (pintype "passive"))
      (node (ref "IC17") (pin "J8") (pinfunction "BG1_J8") (pintype "passive"))
      (node (ref "IC18") (pin "J8") (pinfunction "BG1_J8") (pintype "passive"))
      (node (ref "IC19") (pin "J8") (pinfunction "BG1_J8") (pintype "passive"))
      (node (ref "IC20") (pin "J8") (pinfunction "BG1_J8") (pintype "passive"))
      (node (ref "IC21") (pin "J8") (pinfunction "BG1_J8") (pintype "passive"))
      (node (ref "IC22") (pin "J8") (pinfunction "BG1_J8") (pintype "passive"))
      (node (ref "IC23") (pin "J8") (pinfunction "BG1_J8") (pintype "passive"))
      (node (ref "R170") (pin "1") (pinfunction "1_1") (pintype "passive"))
    )
    (net (code "21") (name "/PU_DDR4_A15") (class "Default")
      (node (ref "IC1") (pin "U21") (pinfunction "D1_MA15_U21") (pintype "passive"))
      (node (ref "IC16") (pin "H3") (pinfunction "~{ACT}_H3") (pintype "passive"))
      (node (ref "IC17") (pin "H3") (pinfunction "~{ACT}_H3") (pintype "passive"))
      (node (ref "IC18") (pin "H3") (pinfunction "~{ACT}_H3") (pintype "passive"))
      (node (ref "IC19") (pin "H3") (pinfunction "~{ACT}_H3") (pintype "passive"))
      (node (ref "IC20") (pin "H3") (pinfunction "~{ACT}_H3") (pintype "passive"))
      (node (ref "IC21") (pin "H3") (pinfunction "~{ACT}_H3") (pintype "passive"))
      (node (ref "IC22") (pin "H3") (pinfunction "~{ACT}_H3") (pintype "passive"))
      (node (ref "IC23") (pin "H3") (pinfunction "~{ACT}_H3") (pintype "passive"))
      (node (ref "R171") (pin "1") (pinfunction "1_1") (pintype "passive"))
    )
    (net (code "22") (name "/PU_DDR4_ARAS_B") (class "Default")
      (node (ref "IC1") (pin "AB25") (pinfunction "D1_MRAS#_AB25") (pintype "passive"))
    )
    (net (code "23") (name "/PU_DDR4_BA0") (class "Default")
      (node (ref "IC1") (pin "AC21") (pinfunction "D1_MBA0_AC21") (pintype "passive"))
      (node (ref "IC16") (pin "K2") (pinfunction "BA0_K2") (pintype "passive"))
      (node (ref "IC17") (pin "K2") (pinfunction "BA0_K2") (pintype "passive"))
      (node (ref "IC18") (pin "K2") (pinfunction "BA0_K2") (pintype "passive"))
      (node (ref "IC19") (pin "K2") (pinfunction "BA0_K2") (pintype "passive"))
      (node (ref "IC20") (pin "K2") (pinfunction "BA0_K2") (pintype "passive"))
      (node (ref "IC21") (pin "K2") (pinfunction "BA0_K2") (pintype "passive"))
      (node (ref "IC22") (pin "K2") (pinfunction "BA0_K2") (pintype "passive"))
      (node (ref "IC23") (pin "K2") (pinfunction "BA0_K2") (pintype "passive"))
      (node (ref "R153") (pin "1") (pinfunction "1_1") (pintype "passive"))
    )
    (net (code "24") (name "/PU_DDR4_BA1") (class "Default")
      (node (ref "IC1") (pin "Y23") (pinfunction "D1_MBA1_Y23") (pintype "passive"))
      (node (ref "IC16") (pin "K8") (pinfunction "BA1_K8") (pintype "passive"))
      (node (ref "IC17") (pin "K8") (pinfunction "BA1_K8") (pintype "passive"))
      (node (ref "IC18") (pin "K8") (pinfunction "BA1_K8") (pintype "passive"))
      (node (ref "IC19") (pin "K8") (pinfunction "BA1_K8") (pintype "passive"))
      (node (ref "IC20") (pin "K8") (pinfunction "BA1_K8") (pintype "passive"))
      (node (ref "IC21") (pin "K8") (pinfunction "BA1_K8") (pintype "passive"))
      (node (ref "IC22") (pin "K8") (pinfunction "BA1_K8") (pintype "passive"))
      (node (ref "IC23") (pin "K8") (pinfunction "BA1_K8") (pintype "passive"))
      (node (ref "R154") (pin "1") (pinfunction "1_1") (pintype "passive"))
    )
    (net (code "25") (name "/PU_DDR4_BA2") (class "Default")
      (node (ref "IC16") (pin "J2") (pinfunction "BG0_J2") (pintype "passive"))
      (node (ref "IC17") (pin "J2") (pinfunction "BG0_J2") (pintype "passive"))
      (node (ref "IC18") (pin "J2") (pinfunction "BG0_J2") (pintype "passive"))
      (node (ref "IC19") (pin "J2") (pinfunction "BG0_J2") (pintype "passive"))
      (node (ref "IC20") (pin "J2") (pinfunction "BG0_J2") (pintype "passive"))
      (node (ref "IC21") (pin "J2") (pinfunction "BG0_J2") (pintype "passive"))
      (node (ref "IC22") (pin "J2") (pinfunction "BG0_J2") (pintype "passive"))
      (node (ref "IC23") (pin "J2") (pinfunction "BG0_J2") (pintype "passive"))
      (node (ref "R155") (pin "1") (pinfunction "1_1") (pintype "passive"))
    )
    (net (code "26") (name "/PU_DDR4_BA3") (class "Default")
      (node (ref "IC1") (pin "AE23") (pinfunction "D1_MBA2_AE23") (pintype "passive"))
    )
    (net (code "27") (name "/PU_DDR4_CAS_B") (class "Default")
      (node (ref "IC1") (pin "AC22") (pinfunction "D1_MCAS#_AC22") (pintype "passive"))
      (node (ref "IC16") (pin "H7") (pinfunction "~{CAS}/A15_H7") (pintype "passive"))
      (node (ref "IC17") (pin "H7") (pinfunction "~{CAS}/A15_H7") (pintype "passive"))
      (node (ref "IC18") (pin "H7") (pinfunction "~{CAS}/A15_H7") (pintype "passive"))
      (node (ref "IC19") (pin "H7") (pinfunction "~{CAS}/A15_H7") (pintype "passive"))
      (node (ref "IC20") (pin "H7") (pinfunction "~{CAS}/A15_H7") (pintype "passive"))
      (node (ref "IC21") (pin "H7") (pinfunction "~{CAS}/A15_H7") (pintype "passive"))
      (node (ref "IC22") (pin "H7") (pinfunction "~{CAS}/A15_H7") (pintype "passive"))
      (node (ref "IC23") (pin "H7") (pinfunction "~{CAS}/A15_H7") (pintype "passive"))
      (node (ref "R173") (pin "1") (pinfunction "1_1") (pintype "passive"))
    )
    (net (code "28") (name "/PU_DDR4_CKE0") (class "Default")
      (node (ref "IC1") (pin "W21") (pinfunction "D1_MCKE0_W21") (pintype "passive"))
      (node (ref "IC16") (pin "G3") (pinfunction "CKE_G3") (pintype "passive"))
      (node (ref "IC17") (pin "G3") (pinfunction "CKE_G3") (pintype "passive"))
      (node (ref "IC18") (pin "G3") (pinfunction "CKE_G3") (pintype "passive"))
      (node (ref "IC19") (pin "G3") (pinfunction "CKE_G3") (pintype "passive"))
      (node (ref "IC20") (pin "G3") (pinfunction "CKE_G3") (pintype "passive"))
      (node (ref "IC21") (pin "G3") (pinfunction "CKE_G3") (pintype "passive"))
      (node (ref "IC22") (pin "G3") (pinfunction "CKE_G3") (pintype "passive"))
      (node (ref "IC23") (pin "G3") (pinfunction "CKE_G3") (pintype "passive"))
      (node (ref "R176") (pin "1") (pinfunction "1_1") (pintype "passive"))
    )
    (net (code "29") (name "/PU_DDR4_CKE1") (class "Default")
      (node (ref "IC1") (pin "AB21") (pinfunction "D1_MCKE1_AB21") (pintype "passive"))
      (node (ref "IC16") (pin "G2") (pinfunction "C0/CKE1_G2") (pintype "passive"))
      (node (ref "IC17") (pin "G2") (pinfunction "C0/CKE1_G2") (pintype "passive"))
      (node (ref "IC18") (pin "G2") (pinfunction "C0/CKE1_G2") (pintype "passive"))
      (node (ref "IC19") (pin "G2") (pinfunction "C0/CKE1_G2") (pintype "passive"))
      (node (ref "IC20") (pin "G2") (pinfunction "C0/CKE1_G2") (pintype "passive"))
      (node (ref "IC21") (pin "G2") (pinfunction "C0/CKE1_G2") (pintype "passive"))
      (node (ref "IC22") (pin "G2") (pinfunction "C0/CKE1_G2") (pintype "passive"))
      (node (ref "IC23") (pin "G2") (pinfunction "C0/CKE1_G2") (pintype "passive"))
      (node (ref "R179") (pin "1") (pinfunction "1_1") (pintype "passive"))
    )
    (net (code "30") (name "/PU_DDR4_CLK") (class "Default")
      (node (ref "IC1") (pin "AA24") (pinfunction "D1_MCK0_AA24") (pintype "passive"))
      (node (ref "IC16") (pin "F7") (pinfunction "CK_T_F7") (pintype "passive"))
      (node (ref "IC17") (pin "F7") (pinfunction "CK_T_F7") (pintype "passive"))
      (node (ref "IC18") (pin "F7") (pinfunction "CK_T_F7") (pintype "passive"))
      (node (ref "IC19") (pin "F7") (pinfunction "CK_T_F7") (pintype "passive"))
      (node (ref "IC20") (pin "F7") (pinfunction "CK_T_F7") (pintype "passive"))
      (node (ref "IC21") (pin "F7") (pinfunction "CK_T_F7") (pintype "passive"))
      (node (ref "IC22") (pin "F7") (pinfunction "CK_T_F7") (pintype "passive"))
      (node (ref "IC23") (pin "F7") (pinfunction "CK_T_F7") (pintype "passive"))
      (node (ref "R146") (pin "1") (pinfunction "1_1") (pintype "passive"))
    )
    (net (code "31") (name "/PU_DDR4_CLK_B") (class "Default")
      (node (ref "IC1") (pin "AA25") (pinfunction "D1_MCK0#_AA25") (pintype "passive"))
      (node (ref "IC16") (pin "F8") (pinfunction "CK_C_F8") (pintype "passive"))
      (node (ref "IC17") (pin "F8") (pinfunction "CK_C_F8") (pintype "passive"))
      (node (ref "IC18") (pin "F8") (pinfunction "CK_C_F8") (pintype "passive"))
      (node (ref "IC19") (pin "F8") (pinfunction "CK_C_F8") (pintype "passive"))
      (node (ref "IC20") (pin "F8") (pinfunction "CK_C_F8") (pintype "passive"))
      (node (ref "IC21") (pin "F8") (pinfunction "CK_C_F8") (pintype "passive"))
      (node (ref "IC22") (pin "F8") (pinfunction "CK_C_F8") (pintype "passive"))
      (node (ref "IC23") (pin "F8") (pinfunction "CK_C_F8") (pintype "passive"))
      (node (ref "R147") (pin "1") (pinfunction "1_1") (pintype "passive"))
    )
    (net (code "32") (name "/PU_DDR4_CS0_B") (class "Default")
      (node (ref "IC1") (pin "U23") (pinfunction "D1_MCS0#_U23") (pintype "passive"))
      (node (ref "IC16") (pin "G7") (pinfunction "~{CS}_G7") (pintype "passive"))
      (node (ref "IC17") (pin "G7") (pinfunction "~{CS}_G7") (pintype "passive"))
      (node (ref "IC18") (pin "G7") (pinfunction "~{CS}_G7") (pintype "passive"))
      (node (ref "IC19") (pin "G7") (pinfunction "~{CS}_G7") (pintype "passive"))
      (node (ref "IC20") (pin "G7") (pinfunction "~{CS}_G7") (pintype "passive"))
      (node (ref "IC21") (pin "G7") (pinfunction "~{CS}_G7") (pintype "passive"))
      (node (ref "IC22") (pin "G7") (pinfunction "~{CS}_G7") (pintype "passive"))
      (node (ref "IC23") (pin "G7") (pinfunction "~{CS}_G7") (pintype "passive"))
      (node (ref "R175") (pin "1") (pinfunction "1_1") (pintype "passive"))
    )
    (net (code "33") (name "/PU_DDR4_CS1_B") (class "Default")
      (node (ref "IC1") (pin "V21") (pinfunction "D1_MCS1#_V21") (pintype "passive"))
      (node (ref "IC16") (pin "G8") (pinfunction "C1/~{CS1}_G8") (pintype "passive"))
      (node (ref "IC17") (pin "G8") (pinfunction "C1/~{CS1}_G8") (pintype "passive"))
      (node (ref "IC18") (pin "G8") (pinfunction "C1/~{CS1}_G8") (pintype "passive"))
      (node (ref "IC19") (pin "G8") (pinfunction "C1/~{CS1}_G8") (pintype "passive"))
      (node (ref "IC20") (pin "G8") (pinfunction "C1/~{CS1}_G8") (pintype "passive"))
      (node (ref "IC21") (pin "G8") (pinfunction "C1/~{CS1}_G8") (pintype "passive"))
      (node (ref "IC22") (pin "G8") (pinfunction "C1/~{CS1}_G8") (pintype "passive"))
      (node (ref "IC23") (pin "G8") (pinfunction "C1/~{CS1}_G8") (pintype "passive"))
      (node (ref "R178") (pin "1") (pinfunction "1_1") (pintype "passive"))
    )
    (net (code "34") (name "/PU_DDR4_DM0_B") (class "Default")
      (node (ref "IC1") (pin "L25") (pinfunction "D1_MDM0_L25") (pintype "passive"))
      (node (ref "IC16") (pin "A7") (pinfunction "NF/~{DM}/~{DBI}/TDQS_T_A7") (pintype "passive"))
      (node (ref "IC17") (pin "A7") (pinfunction "NF/~{DM}/~{DBI}/TDQS_T_A7") (pintype "passive"))
      (node (ref "IC18") (pin "A7") (pinfunction "NF/~{DM}/~{DBI}/TDQS_T_A7") (pintype "passive"))
      (node (ref "IC19") (pin "A7") (pinfunction "NF/~{DM}/~{DBI}/TDQS_T_A7") (pintype "passive"))
      (node (ref "IC20") (pin "A7") (pinfunction "NF/~{DM}/~{DBI}/TDQS_T_A7") (pintype "passive"))
      (node (ref "IC21") (pin "A7") (pinfunction "NF/~{DM}/~{DBI}/TDQS_T_A7") (pintype "passive"))
      (node (ref "IC22") (pin "A7") (pinfunction "NF/~{DM}/~{DBI}/TDQS_T_A7") (pintype "passive"))
      (node (ref "IC23") (pin "A7") (pinfunction "NF/~{DM}/~{DBI}/TDQS_T_A7") (pintype "passive"))
    )
    (net (code "35") (name "/PU_DDR4_DM1_B") (class "Default")
      (node (ref "IC1") (pin "L21") (pinfunction "D1_MDM1_L21") (pintype "passive"))
    )
    (net (code "36") (name "/PU_DDR4_DM2_B") (class "Default")
      (node (ref "IC1") (pin "E23") (pinfunction "D1_MDM2_E23") (pintype "passive"))
    )
    (net (code "37") (name "/PU_DDR4_DM3_B") (class "Default")
      (node (ref "IC1") (pin "G23") (pinfunction "D1_MDM4_G23") (pintype "passive"))
    )
    (net (code "38") (name "/PU_DDR4_DM8_B") (class "Default")
      (node (ref "IC1") (pin "B22") (pinfunction "D1_MDM8_B22") (pintype "passive"))
    )
    (net (code "39") (name "/PU_DDR4_DQ0") (class "Default")
      (node (ref "IC1") (pin "N24") (pinfunction "D1_MDQ02_N24") (pintype "passive"))
      (node (ref "IC16") (pin "C2") (pinfunction "DQ0_C2") (pintype "passive"))
      (node (ref "IC17") (pin "C2") (pinfunction "DQ0_C2") (pintype "passive"))
      (node (ref "IC18") (pin "C2") (pinfunction "DQ0_C2") (pintype "passive"))
      (node (ref "IC19") (pin "C2") (pinfunction "DQ0_C2") (pintype "passive"))
      (node (ref "IC20") (pin "C2") (pinfunction "DQ0_C2") (pintype "passive"))
      (node (ref "IC21") (pin "C2") (pinfunction "DQ0_C2") (pintype "passive"))
      (node (ref "IC22") (pin "C2") (pinfunction "DQ0_C2") (pintype "passive"))
      (node (ref "IC23") (pin "C2") (pinfunction "DQ0_C2") (pintype "passive"))
    )
    (net (code "40") (name "/PU_DDR4_DQ1") (class "Default")
      (node (ref "IC1") (pin "K24") (pinfunction "D1_MDQ01_K24") (pintype "passive"))
      (node (ref "IC16") (pin "B7") (pinfunction "DQ1_B7") (pintype "passive"))
      (node (ref "IC17") (pin "B7") (pinfunction "DQ1_B7") (pintype "passive"))
      (node (ref "IC18") (pin "B7") (pinfunction "DQ1_B7") (pintype "passive"))
      (node (ref "IC19") (pin "B7") (pinfunction "DQ1_B7") (pintype "passive"))
      (node (ref "IC20") (pin "B7") (pinfunction "DQ1_B7") (pintype "passive"))
      (node (ref "IC21") (pin "B7") (pinfunction "DQ1_B7") (pintype "passive"))
      (node (ref "IC22") (pin "B7") (pinfunction "DQ1_B7") (pintype "passive"))
      (node (ref "IC23") (pin "B7") (pinfunction "DQ1_B7") (pintype "passive"))
    )
    (net (code "41") (name "/PU_DDR4_DQ2") (class "Default")
      (node (ref "IC1") (pin "R24") (pinfunction "D1_MDQ03_R24") (pintype "passive"))
      (node (ref "IC16") (pin "D3") (pinfunction "DQ2_D3") (pintype "passive"))
      (node (ref "IC17") (pin "D3") (pinfunction "DQ2_D3") (pintype "passive"))
      (node (ref "IC18") (pin "D3") (pinfunction "DQ2_D3") (pintype "passive"))
      (node (ref "IC19") (pin "D3") (pinfunction "DQ2_D3") (pintype "passive"))
      (node (ref "IC20") (pin "D3") (pinfunction "DQ2_D3") (pintype "passive"))
      (node (ref "IC21") (pin "D3") (pinfunction "DQ2_D3") (pintype "passive"))
      (node (ref "IC22") (pin "D3") (pinfunction "DQ2_D3") (pintype "passive"))
      (node (ref "IC23") (pin "D3") (pinfunction "DQ2_D3") (pintype "passive"))
    )
    (net (code "42") (name "/PU_DDR4_DQ3") (class "Default")
      (node (ref "IC1") (pin "J25") (pinfunction "D1_MDQ00_J25") (pintype "passive"))
      (node (ref "IC16") (pin "D7") (pinfunction "DQ3_D7") (pintype "passive"))
      (node (ref "IC17") (pin "D7") (pinfunction "DQ3_D7") (pintype "passive"))
      (node (ref "IC18") (pin "D7") (pinfunction "DQ3_D7") (pintype "passive"))
      (node (ref "IC19") (pin "D7") (pinfunction "DQ3_D7") (pintype "passive"))
      (node (ref "IC20") (pin "D7") (pinfunction "DQ3_D7") (pintype "passive"))
      (node (ref "IC21") (pin "D7") (pinfunction "DQ3_D7") (pintype "passive"))
      (node (ref "IC22") (pin "D7") (pinfunction "DQ3_D7") (pintype "passive"))
      (node (ref "IC23") (pin "D7") (pinfunction "DQ3_D7") (pintype "passive"))
    )
    (net (code "43") (name "/PU_DDR4_DQ4") (class "Default")
      (node (ref "IC1") (pin "P25") (pinfunction "D1_MDQ07_P25") (pintype "passive"))
      (node (ref "IC16") (pin "D2") (pinfunction "DQ4/NC_D2") (pintype "passive"))
      (node (ref "IC17") (pin "D2") (pinfunction "DQ4/NC_D2") (pintype "passive"))
      (node (ref "IC18") (pin "D2") (pinfunction "DQ4/NC_D2") (pintype "passive"))
      (node (ref "IC19") (pin "D2") (pinfunction "DQ4/NC_D2") (pintype "passive"))
      (node (ref "IC20") (pin "D2") (pinfunction "DQ4/NC_D2") (pintype "passive"))
      (node (ref "IC21") (pin "D2") (pinfunction "DQ4/NC_D2") (pintype "passive"))
      (node (ref "IC22") (pin "D2") (pinfunction "DQ4/NC_D2") (pintype "passive"))
      (node (ref "IC23") (pin "D2") (pinfunction "DQ4/NC_D2") (pintype "passive"))
    )
    (net (code "44") (name "/PU_DDR4_DQ5") (class "Default")
      (node (ref "IC1") (pin "K25") (pinfunction "D1_MDQ05_K25") (pintype "passive"))
      (node (ref "IC16") (pin "D8") (pinfunction "DQ5/NC_D8") (pintype "passive"))
      (node (ref "IC17") (pin "D8") (pinfunction "DQ5/NC_D8") (pintype "passive"))
      (node (ref "IC18") (pin "D8") (pinfunction "DQ5/NC_D8") (pintype "passive"))
      (node (ref "IC19") (pin "D8") (pinfunction "DQ5/NC_D8") (pintype "passive"))
      (node (ref "IC20") (pin "D8") (pinfunction "DQ5/NC_D8") (pintype "passive"))
      (node (ref "IC21") (pin "D8") (pinfunction "DQ5/NC_D8") (pintype "passive"))
      (node (ref "IC22") (pin "D8") (pinfunction "DQ5/NC_D8") (pintype "passive"))
      (node (ref "IC23") (pin "D8") (pinfunction "DQ5/NC_D8") (pintype "passive"))
    )
    (net (code "45") (name "/PU_DDR4_DQ6") (class "Default")
      (node (ref "IC1") (pin "N25") (pinfunction "D1_MDQ06_N25") (pintype "passive"))
      (node (ref "IC16") (pin "E3") (pinfunction "DQ6/NC_E3") (pintype "passive"))
      (node (ref "IC17") (pin "E3") (pinfunction "DQ6/NC_E3") (pintype "passive"))
      (node (ref "IC18") (pin "E3") (pinfunction "DQ6/NC_E3") (pintype "passive"))
      (node (ref "IC19") (pin "E3") (pinfunction "DQ6/NC_E3") (pintype "passive"))
      (node (ref "IC20") (pin "E3") (pinfunction "DQ6/NC_E3") (pintype "passive"))
      (node (ref "IC21") (pin "E3") (pinfunction "DQ6/NC_E3") (pintype "passive"))
      (node (ref "IC22") (pin "E3") (pinfunction "DQ6/NC_E3") (pintype "passive"))
      (node (ref "IC23") (pin "E3") (pinfunction "DQ6/NC_E3") (pintype "passive"))
    )
    (net (code "46") (name "/PU_DDR4_DQ7") (class "Default")
      (node (ref "IC1") (pin "H24") (pinfunction "D1_MDQ04_H24") (pintype "passive"))
      (node (ref "IC16") (pin "E7") (pinfunction "DQ7/NC_E7") (pintype "passive"))
      (node (ref "IC17") (pin "E7") (pinfunction "DQ7/NC_E7") (pintype "passive"))
      (node (ref "IC18") (pin "E7") (pinfunction "DQ7/NC_E7") (pintype "passive"))
      (node (ref "IC19") (pin "E7") (pinfunction "DQ7/NC_E7") (pintype "passive"))
      (node (ref "IC20") (pin "E7") (pinfunction "DQ7/NC_E7") (pintype "passive"))
      (node (ref "IC21") (pin "E7") (pinfunction "DQ7/NC_E7") (pintype "passive"))
      (node (ref "IC22") (pin "E7") (pinfunction "DQ7/NC_E7") (pintype "passive"))
      (node (ref "IC23") (pin "E7") (pinfunction "DQ7/NC_E7") (pintype "passive"))
    )
    (net (code "47") (name "/PU_DDR4_DQ8") (class "Default")
      (node (ref "IC1") (pin "N21") (pinfunction "D1_MDQ10_N21") (pintype "passive"))
    )
    (net (code "48") (name "/PU_DDR4_DQ9") (class "Default")
      (node (ref "IC1") (pin "M23") (pinfunction "D1_MDQ09_M23") (pintype "passive"))
    )
    (net (code "49") (name "/PU_DDR4_DQ10") (class "Default")
      (node (ref "IC1") (pin "P21") (pinfunction "D1_MDQ11_P21") (pintype "passive"))
    )
    (net (code "50") (name "/PU_DDR4_DQ11") (class "Default")
      (node (ref "IC1") (pin "L23") (pinfunction "D1_MDQ08_L23") (pintype "passive"))
    )
    (net (code "51") (name "/PU_DDR4_DQ12") (class "Default")
      (node (ref "IC1") (pin "M21") (pinfunction "D1_MDQ14_M21") (pintype "passive"))
    )
    (net (code "52") (name "/PU_DDR4_DQ13") (class "Default")
      (node (ref "IC1") (pin "L22") (pinfunction "D1_MDQ13_L22") (pintype "passive"))
    )
    (net (code "53") (name "/PU_DDR4_DQ14") (class "Default")
      (node (ref "IC1") (pin "P23") (pinfunction "D1_MDQ15_P23") (pintype "passive"))
    )
    (net (code "54") (name "/PU_DDR4_DQ15") (class "Default")
      (node (ref "IC1") (pin "K21") (pinfunction "D1_MDQ12_K21") (pintype "passive"))
    )
    (net (code "55") (name "/PU_DDR4_DQ16") (class "Default")
      (node (ref "IC1") (pin "F24") (pinfunction "D1_MDQ18_F24") (pintype "passive"))
    )
    (net (code "56") (name "/PU_DDR4_DQ17") (class "Default")
      (node (ref "IC1") (pin "C25") (pinfunction "D1_MDQ17_C25") (pintype "passive"))
    )
    (net (code "57") (name "/PU_DDR4_DQ18") (class "Default")
      (node (ref "IC1") (pin "H25") (pinfunction "D1_MDQ19_H25") (pintype "passive"))
    )
    (net (code "58") (name "/PU_DDR4_DQ19") (class "Default")
      (node (ref "IC1") (pin "C24") (pinfunction "D1_MDQ16_C24") (pintype "passive"))
    )
    (net (code "59") (name "/PU_DDR4_DQ20") (class "Default")
      (node (ref "IC1") (pin "G25") (pinfunction "D1_MDQ23_G25") (pintype "passive"))
    )
    (net (code "60") (name "/PU_DDR4_DQ21") (class "Default")
      (node (ref "IC1") (pin "D24") (pinfunction "D1_MDQ21_D24") (pintype "passive"))
    )
    (net (code "61") (name "/PU_DDR4_DQ22") (class "Default")
      (node (ref "IC1") (pin "F25") (pinfunction "D1_MDQ22_F25") (pintype "passive"))
    )
    (net (code "62") (name "/PU_DDR4_DQ23") (class "Default")
      (node (ref "IC1") (pin "B24") (pinfunction "D1_MDQ20_B24") (pintype "passive"))
    )
    (net (code "63") (name "/PU_DDR4_DQ24") (class "Default")
      (node (ref "IC1") (pin "K23") (pinfunction "D1_MDQ27_K23") (pintype "passive"))
    )
    (net (code "64") (name "/PU_DDR4_DQ25") (class "Default")
      (node (ref "IC1") (pin "H21") (pinfunction "D1_MDQ25_H21") (pintype "passive"))
    )
    (net (code "65") (name "/PU_DDR4_DQ26") (class "Default")
      (node (ref "IC1") (pin "J23") (pinfunction "D1_MDQ26_J23") (pintype "passive"))
    )
    (net (code "66") (name "/PU_DDR4_DQ27") (class "Default")
      (node (ref "IC1") (pin "F22") (pinfunction "D1_MDQ24_F22") (pintype "passive"))
    )
    (net (code "67") (name "/PU_DDR4_DQ28") (class "Default")
      (node (ref "IC1") (pin "J22") (pinfunction "D1_MDQ31_J22") (pintype "passive"))
    )
    (net (code "68") (name "/PU_DDR4_DQ29") (class "Default")
      (node (ref "IC1") (pin "F23") (pinfunction "D1_MDQ29_F23") (pintype "passive"))
    )
    (net (code "69") (name "/PU_DDR4_DQ30") (class "Default")
      (node (ref "IC1") (pin "J21") (pinfunction "D1_MDQ30_J21") (pintype "passive"))
    )
    (net (code "70") (name "/PU_DDR4_DQ31") (class "Default")
      (node (ref "IC1") (pin "G21") (pinfunction "D1_MDQ28_G21") (pintype "passive"))
    )
    (net (code "71") (name "/PU_DDR4_DQS0") (class "Default")
      (node (ref "IC1") (pin "M24") (pinfunction "D1_MDQS0_M24") (pintype "passive"))
      (node (ref "IC16") (pin "C3") (pinfunction "DQS_T_C3") (pintype "passive"))
      (node (ref "IC17") (pin "C3") (pinfunction "DQS_T_C3") (pintype "passive"))
      (node (ref "IC18") (pin "C3") (pinfunction "DQS_T_C3") (pintype "passive"))
      (node (ref "IC19") (pin "C3") (pinfunction "DQS_T_C3") (pintype "passive"))
      (node (ref "IC20") (pin "C3") (pinfunction "DQS_T_C3") (pintype "passive"))
      (node (ref "IC21") (pin "C3") (pinfunction "DQS_T_C3") (pintype "passive"))
      (node (ref "IC22") (pin "C3") (pinfunction "DQS_T_C3") (pintype "passive"))
      (node (ref "IC23") (pin "C3") (pinfunction "DQS_T_C3") (pintype "passive"))
    )
    (net (code "72") (name "/PU_DDR4_DQS0_B") (class "Default")
      (node (ref "IC1") (pin "M25") (pinfunction "D1_MDQS0#_M25") (pintype "passive"))
      (node (ref "IC16") (pin "B3") (pinfunction "DQS_S_B3") (pintype "passive"))
      (node (ref "IC17") (pin "B3") (pinfunction "DQS_S_B3") (pintype "passive"))
      (node (ref "IC18") (pin "B3") (pinfunction "DQS_S_B3") (pintype "passive"))
      (node (ref "IC19") (pin "B3") (pinfunction "DQS_S_B3") (pintype "passive"))
      (node (ref "IC20") (pin "B3") (pinfunction "DQS_S_B3") (pintype "passive"))
      (node (ref "IC21") (pin "B3") (pinfunction "DQS_S_B3") (pintype "passive"))
      (node (ref "IC22") (pin "B3") (pinfunction "DQS_S_B3") (pintype "passive"))
      (node (ref "IC23") (pin "B3") (pinfunction "DQS_S_B3") (pintype "passive"))
    )
    (net (code "73") (name "/PU_DDR4_DQS1") (class "Default")
      (node (ref "IC1") (pin "N22") (pinfunction "D1_MDQS1_N22") (pintype "passive"))
    )
    (net (code "74") (name "/PU_DDR4_DQS1_B") (class "Default")
      (node (ref "IC1") (pin "N23") (pinfunction "D1_MDQS1#_N23") (pintype "passive"))
    )
    (net (code "75") (name "/PU_DDR4_DQS2") (class "Default")
      (node (ref "IC1") (pin "E25") (pinfunction "D1_MDQS2_E25") (pintype "passive"))
    )
    (net (code "76") (name "/PU_DDR4_DQS2_B") (class "Default")
      (node (ref "IC1") (pin "D25") (pinfunction "D1_MDQS2#_D25") (pintype "passive"))
    )
    (net (code "77") (name "/PU_DDR4_DQS3") (class "Default")
      (node (ref "IC1") (pin "H23") (pinfunction "D1_MDQS3_H23") (pintype "passive"))
    )
    (net (code "78") (name "/PU_DDR4_DQS3_B") (class "Default")
      (node (ref "IC1") (pin "H22") (pinfunction "D1_MDQS3#_H22") (pintype "passive"))
    )
    (net (code "79") (name "/PU_DDR4_DQS8") (class "Default")
      (node (ref "IC1") (pin "B23") (pinfunction "D1_MDQS8_B23") (pintype "passive"))
    )
    (net (code "80") (name "/PU_DDR4_DQS8_B") (class "Default")
      (node (ref "IC1") (pin "A23") (pinfunction "D1_MDQS8#_A23") (pintype "passive"))
    )
    (net (code "81") (name "/PU_DDR4_MECC0") (class "Default")
      (node (ref "IC1") (pin "C22") (pinfunction "D1_MECC0_C22") (pintype "passive"))
    )
    (net (code "82") (name "/PU_DDR4_MECC1") (class "Default")
      (node (ref "IC1") (pin "A22") (pinfunction "D1_MECC1_A22") (pintype "passive"))
    )
    (net (code "83") (name "/PU_DDR4_MECC2") (class "Default")
      (node (ref "IC1") (pin "D22") (pinfunction "D1_MECC2_D22") (pintype "passive"))
    )
    (net (code "84") (name "/PU_DDR4_MECC3") (class "Default")
      (node (ref "IC1") (pin "D23") (pinfunction "D1_MECC3_D23") (pintype "passive"))
    )
    (net (code "85") (name "/PU_DDR4_OD1") (class "Default")
      (node (ref "IC1") (pin "T21") (pinfunction "D1_MODT1_T21") (pintype "passive"))
    )
    (net (code "86") (name "/PU_DDR4_ODT0") (class "Default")
      (node (ref "IC1") (pin "U22") (pinfunction "D1_MODT0_U22") (pintype "passive"))
      (node (ref "IC16") (pin "F3") (pinfunction "ODT_F3") (pintype "passive"))
      (node (ref "IC17") (pin "F3") (pinfunction "ODT_F3") (pintype "passive"))
      (node (ref "IC18") (pin "F3") (pinfunction "ODT_F3") (pintype "passive"))
      (node (ref "IC19") (pin "F3") (pinfunction "ODT_F3") (pintype "passive"))
      (node (ref "IC20") (pin "F3") (pinfunction "ODT_F3") (pintype "passive"))
      (node (ref "IC21") (pin "F3") (pinfunction "ODT_F3") (pintype "passive"))
      (node (ref "IC22") (pin "F3") (pinfunction "ODT_F3") (pintype "passive"))
      (node (ref "R177") (pin "1") (pinfunction "1_1") (pintype "passive"))
    )
    (net (code "87") (name "/PU_DDR4_ODT1") (class "Default")
      (node (ref "IC16") (pin "F2") (pinfunction "ODT1_F2") (pintype "passive"))
      (node (ref "IC17") (pin "F2") (pinfunction "ODT1_F2") (pintype "passive"))
      (node (ref "IC18") (pin "F2") (pinfunction "ODT1_F2") (pintype "passive"))
      (node (ref "IC19") (pin "F2") (pinfunction "ODT1_F2") (pintype "passive"))
      (node (ref "IC20") (pin "F2") (pinfunction "ODT1_F2") (pintype "passive"))
      (node (ref "IC21") (pin "F2") (pinfunction "ODT1_F2") (pintype "passive"))
      (node (ref "IC22") (pin "F2") (pinfunction "ODT1_F2") (pintype "passive"))
      (node (ref "IC23") (pin "F2") (pinfunction "ODT1_F2") (pintype "passive"))
      (node (ref "R180") (pin "1") (pinfunction "1_1") (pintype "passive"))
    )
    (net (code "88") (name "/PU_DDR4_PAR") (class "Default")
      (node (ref "IC1") (pin "U25") (pinfunction "D1_MAPAR_OUT_U25") (pintype "passive"))
      (node (ref "IC16") (pin "N3") (pinfunction "PAR_N3") (pintype "passive"))
      (node (ref "IC17") (pin "N3") (pinfunction "PAR_N3") (pintype "passive"))
      (node (ref "IC18") (pin "N3") (pinfunction "PAR_N3") (pintype "passive"))
      (node (ref "IC19") (pin "N3") (pinfunction "PAR_N3") (pintype "passive"))
      (node (ref "IC20") (pin "N3") (pinfunction "PAR_N3") (pintype "passive"))
      (node (ref "IC21") (pin "N3") (pinfunction "PAR_N3") (pintype "passive"))
      (node (ref "IC22") (pin "N3") (pinfunction "PAR_N3") (pintype "passive"))
      (node (ref "IC23") (pin "N3") (pinfunction "PAR_N3") (pintype "passive"))
      (node (ref "R181") (pin "1") (pinfunction "1_1") (pintype "passive"))
    )
    (net (code "89") (name "/PU_DDR4_RAS_B") (class "Default")
      (node (ref "IC16") (pin "H8") (pinfunction "~{RAS}/A16/NC_H8") (pintype "passive"))
      (node (ref "IC17") (pin "H8") (pinfunction "~{RAS}/A16/NC_H8") (pintype "passive"))
      (node (ref "IC18") (pin "H8") (pinfunction "~{RAS}/A16/NC_H8") (pintype "passive"))
      (node (ref "IC19") (pin "H8") (pinfunction "~{RAS}/A16/NC_H8") (pintype "passive"))
      (node (ref "IC20") (pin "H8") (pinfunction "~{RAS}/A16/NC_H8") (pintype "passive"))
      (node (ref "IC21") (pin "H8") (pinfunction "~{RAS}/A16/NC_H8") (pintype "passive"))
      (node (ref "IC22") (pin "H8") (pinfunction "~{RAS}/A16/NC_H8") (pintype "passive"))
      (node (ref "IC23") (pin "H8") (pinfunction "~{RAS}/A16/NC_H8") (pintype "passive"))
      (node (ref "R172") (pin "1") (pinfunction "1_1") (pintype "passive"))
    )
    (net (code "90") (name "/PU_DDR4_RST_B") (class "Default")
      (node (ref "IC16") (pin "L1") (pinfunction "~{RESET}_L1") (pintype "passive"))
      (node (ref "IC17") (pin "L1") (pinfunction "~{RESET}_L1") (pintype "passive"))
      (node (ref "IC18") (pin "L1") (pinfunction "~{RESET}_L1") (pintype "passive"))
      (node (ref "IC19") (pin "L1") (pinfunction "~{RESET}_L1") (pintype "passive"))
      (node (ref "IC20") (pin "L1") (pinfunction "~{RESET}_L1") (pintype "passive"))
      (node (ref "IC21") (pin "L1") (pinfunction "~{RESET}_L1") (pintype "passive"))
      (node (ref "IC22") (pin "L1") (pinfunction "~{RESET}_L1") (pintype "passive"))
      (node (ref "IC23") (pin "L1") (pinfunction "~{RESET}_L1") (pintype "passive"))
    )
    (net (code "91") (name "/PU_DDR4_TEN") (class "Default")
      (node (ref "IC16") (pin "G9") (pinfunction "RUF/TEN_G9") (pintype "passive"))
      (node (ref "IC17") (pin "G9") (pinfunction "RUF/TEN_G9") (pintype "passive"))
      (node (ref "IC18") (pin "G9") (pinfunction "RUF/TEN_G9") (pintype "passive"))
      (node (ref "IC19") (pin "G9") (pinfunction "RUF/TEN_G9") (pintype "passive"))
      (node (ref "IC20") (pin "G9") (pinfunction "RUF/TEN_G9") (pintype "passive"))
      (node (ref "IC21") (pin "G9") (pinfunction "RUF/TEN_G9") (pintype "passive"))
      (node (ref "IC22") (pin "G9") (pinfunction "RUF/TEN_G9") (pintype "passive"))
      (node (ref "IC23") (pin "G9") (pinfunction "RUF/TEN_G9") (pintype "passive"))
      (node (ref "R145") (pin "1") (pinfunction "1_1") (pintype "passive"))
    )
    (net (code "92") (name "/PU_DDR4_WE_B") (class "Default")
      (node (ref "IC1") (pin "Y21") (pinfunction "D1_MWE_Y21") (pintype "passive"))
      (node (ref "IC16") (pin "H2") (pinfunction "~{WE}/A14_H2") (pintype "passive"))
      (node (ref "IC17") (pin "H2") (pinfunction "~{WE}/A14_H2") (pintype "passive"))
      (node (ref "IC18") (pin "H2") (pinfunction "~{WE}/A14_H2") (pintype "passive"))
      (node (ref "IC19") (pin "H2") (pinfunction "~{WE}/A14_H2") (pintype "passive"))
      (node (ref "IC20") (pin "H2") (pinfunction "~{WE}/A14_H2") (pintype "passive"))
      (node (ref "IC21") (pin "H2") (pinfunction "~{WE}/A14_H2") (pintype "passive"))
      (node (ref "IC22") (pin "H2") (pinfunction "~{WE}/A14_H2") (pintype "passive"))
      (node (ref "IC23") (pin "H2") (pinfunction "~{WE}/A14_H2") (pintype "passive"))
      (node (ref "R174") (pin "1") (pinfunction "1_1") (pintype "passive"))
    )
    (net (code "93") (name "/PU_DDR4_ZQ_0") (class "Default")
      (node (ref "IC16") (pin "B9") (pinfunction "ZQ_B9") (pintype "passive"))
      (node (ref "IC17") (pin "B9") (pinfunction "ZQ_B9") (pintype "passive"))
      (node (ref "IC18") (pin "B9") (pinfunction "ZQ_B9") (pintype "passive"))
      (node (ref "IC19") (pin "B9") (pinfunction "ZQ_B9") (pintype "passive"))
      (node (ref "IC20") (pin "B9") (pinfunction "ZQ_B9") (pintype "passive"))
      (node (ref "IC21") (pin "B9") (pinfunction "ZQ_B9") (pintype "passive"))
      (node (ref "IC22") (pin "B9") (pinfunction "ZQ_B9") (pintype "passive"))
      (node (ref "IC23") (pin "B9") (pinfunction "ZQ_B9") (pintype "passive"))
      (node (ref "R135") (pin "2") (pinfunction "2_2") (pintype "passive"))
      (node (ref "R136") (pin "2") (pinfunction "2_2") (pintype "passive"))
      (node (ref "R137") (pin "2") (pinfunction "2_2") (pintype "passive"))
      (node (ref "R138") (pin "2") (pinfunction "2_2") (pintype "passive"))
      (node (ref "R148") (pin "2") (pinfunction "2_2") (pintype "passive"))
      (node (ref "R149") (pin "2") (pinfunction "2_2") (pintype "passive"))
      (node (ref "R151") (pin "2") (pinfunction "2_2") (pintype "passive"))
      (node (ref "R152") (pin "2") (pinfunction "2_2") (pintype "passive"))
    )
    (net (code "94") (name "/PU_DDR_RST_B") (class "Default")
      (node (ref "R144") (pin "2") (pinfunction "2_2") (pintype "passive"))
    )
    (net (code "95") (name "/PU_I2C1_SCL") (class "Default")
      (node (ref "IC24") (pin "6") (pinfunction "SCL_6") (pintype "passive"))
    )
    (net (code "96") (name "/PU_I2C1_SDA") (class "Default")
      (node (ref "IC24") (pin "5") (pinfunction "SDA_5") (pintype "passive"))
    )
    (net (code "97") (name "/P_ALERT_N") (class "Default")
      (node (ref "R142") (pin "2") (pinfunction "2_2") (pintype "passive"))
    )
    (net (code "98") (name "DDR_VREF") (class "Default")
      (node (ref "C209") (pin "2") (pinfunction "2_2") (pintype "passive"))
      (node (ref "C210") (pin "2") (pinfunction "2_2") (pintype "passive"))
      (node (ref "C211") (pin "2") (pinfunction "2_2") (pintype "passive"))
      (node (ref "C212") (pin "2") (pinfunction "2_2") (pintype "passive"))
      (node (ref "C213") (pin "2") (pinfunction "2_2") (pintype "passive"))
      (node (ref "C214") (pin "2") (pinfunction "2_2") (pintype "passive"))
      (node (ref "C215") (pin "2") (pinfunction "2_2") (pintype "passive"))
      (node (ref "C216") (pin "2") (pinfunction "2_2") (pintype "passive"))
      (node (ref "C227") (pin "2") (pinfunction "2_2") (pintype "passive"))
      (node (ref "C228") (pin "2") (pinfunction "2_2") (pintype "passive"))
      (node (ref "C229") (pin "2") (pinfunction "2_2") (pintype "passive"))
      (node (ref "C230") (pin "2") (pinfunction "2_2") (pintype "passive"))
      (node (ref "C231") (pin "2") (pinfunction "2_2") (pintype "passive"))
      (node (ref "C232") (pin "2") (pinfunction "2_2") (pintype "passive"))
      (node (ref "C233") (pin "2") (pinfunction "2_2") (pintype "passive"))
      (node (ref "C234") (pin "2") (pinfunction "2_2") (pintype "passive"))
      (node (ref "IC16") (pin "J1") (pinfunction "VREFCA_J1") (pintype "passive"))
      (node (ref "IC17") (pin "J1") (pinfunction "VREFCA_J1") (pintype "passive"))
      (node (ref "IC18") (pin "J1") (pinfunction "VREFCA_J1") (pintype "passive"))
      (node (ref "IC19") (pin "J1") (pinfunction "VREFCA_J1") (pintype "passive"))
      (node (ref "IC20") (pin "J1") (pinfunction "VREFCA_J1") (pintype "passive"))
      (node (ref "IC21") (pin "J1") (pinfunction "VREFCA_J1") (pintype "passive"))
      (node (ref "IC22") (pin "J1") (pinfunction "VREFCA_J1") (pintype "passive"))
      (node (ref "IC23") (pin "J1") (pinfunction "VREFCA_J1") (pintype "passive"))
    )
    (net (code "99") (name "DDR_VTT") (class "Default")
      (node (ref "C275") (pin "2") (pinfunction "2_2") (pintype "passive"))
      (node (ref "C276") (pin "2") (pinfunction "2_2") (pintype "passive"))
      (node (ref "C277") (pin "2") (pinfunction "2_2") (pintype "passive"))
      (node (ref "C278") (pin "2") (pinfunction "2_2") (pintype "passive"))
      (node (ref "C279") (pin "2") (pinfunction "2_2") (pintype "passive"))
      (node (ref "C280") (pin "2") (pinfunction "2_2") (pintype "passive"))
      (node (ref "C301") (pin "2") (pinfunction "2_2") (pintype "passive"))
      (node (ref "C302") (pin "2") (pinfunction "2_2") (pintype "passive"))
      (node (ref "C303") (pin "2") (pinfunction "2_2") (pintype "passive"))
      (node (ref "C304") (pin "2") (pinfunction "2_2") (pintype "passive"))
      (node (ref "C305") (pin "2") (pinfunction "2_2") (pintype "passive"))
      (node (ref "C306") (pin "2") (pinfunction "2_2") (pintype "passive"))
      (node (ref "C327") (pin "2") (pinfunction "2_2") (pintype "passive"))
      (node (ref "C328") (pin "2") (pinfunction "2_2") (pintype "passive"))
      (node (ref "C329") (pin "2") (pinfunction "2_2") (pintype "passive"))
      (node (ref "C330") (pin "2") (pinfunction "2_2") (pintype "passive"))
      (node (ref "C331") (pin "1") (pinfunction "1_1") (pintype "passive"))
      (node (ref "C332") (pin "1") (pinfunction "1_1") (pintype "passive"))
      (node (ref "R153") (pin "2") (pinfunction "2_2") (pintype "passive"))
      (node (ref "R154") (pin "2") (pinfunction "2_2") (pintype "passive"))
      (node (ref "R155") (pin "2") (pinfunction "2_2") (pintype "passive"))
      (node (ref "R156") (pin "2") (pinfunction "2_2") (pintype "passive"))
      (node (ref "R157") (pin "2") (pinfunction "2_2") (pintype "passive"))
      (node (ref "R158") (pin "2") (pinfunction "2_2") (pintype "passive"))
      (node (ref "R159") (pin "2") (pinfunction "2_2") (pintype "passive"))
      (node (ref "R160") (pin "2") (pinfunction "2_2") (pintype "passive"))
      (node (ref "R161") (pin "2") (pinfunction "2_2") (pintype "passive"))
      (node (ref "R162") (pin "2") (pinfunction "2_2") (pintype "passive"))
      (node (ref "R163") (pin "2") (pinfunction "2_2") (pintype "passive"))
      (node (ref "R164") (pin "2") (pinfunction "2_2") (pintype "passive"))
      (node (ref "R165") (pin "2") (pinfunction "2_2") (pintype "passive"))
      (node (ref "R166") (pin "2") (pinfunction "2_2") (pintype "passive"))
      (node (ref "R167") (pin "2") (pinfunction "2_2") (pintype "passive"))
      (node (ref "R168") (pin "2") (pinfunction "2_2") (pintype "passive"))
      (node (ref "R169") (pin "2") (pinfunction "2_2") (pintype "passive"))
      (node (ref "R170") (pin "2") (pinfunction "2_2") (pintype "passive"))
      (node (ref "R171") (pin "2") (pinfunction "2_2") (pintype "passive"))
      (node (ref "R172") (pin "2") (pinfunction "2_2") (pintype "passive"))
      (node (ref "R173") (pin "2") (pinfunction "2_2") (pintype "passive"))
      (node (ref "R174") (pin "2") (pinfunction "2_2") (pintype "passive"))
      (node (ref "R175") (pin "2") (pinfunction "2_2") (pintype "passive"))
      (node (ref "R176") (pin "2") (pinfunction "2_2") (pintype "passive"))
      (node (ref "R177") (pin "2") (pinfunction "2_2") (pintype "passive"))
      (node (ref "R178") (pin "2") (pinfunction "2_2") (pintype "passive"))
      (node (ref "R179") (pin "2") (pinfunction "2_2") (pintype "passive"))
      (node (ref "R180") (pin "2") (pinfunction "2_2") (pintype "passive"))
      (node (ref "R181") (pin "2") (pinfunction "2_2") (pintype "passive"))
    )
    (net (code "100") (name "GND") (class "Default")
      (node (ref "C201") (pin "2") (pinfunction "2_2") (pintype "passive"))
      (node (ref "C202") (pin "2") (pinfunction "2_2") (pintype "passive"))
      (node (ref "C203") (pin "2") (pinfunction "2_2") (pintype "passive"))
      (node (ref "C204") (pin "2") (pinfunction "2_2") (pintype "passive"))
      (node (ref "C205") (pin "2") (pinfunction "2_2") (pintype "passive"))
      (node (ref "C206") (pin "2") (pinfunction "2_2") (pintype "passive"))
      (node (ref "C207") (pin "2") (pinfunction "2_2") (pintype "passive"))
      (node (ref "C208") (pin "2") (pinfunction "2_2") (pintype "passive"))
      (node (ref "C209") (pin "1") (pinfunction "1_1") (pintype "passive"))
      (node (ref "C210") (pin "1") (pinfunction "1_1") (pintype "passive"))
      (node (ref "C211") (pin "1") (pinfunction "1_1") (pintype "passive"))
      (node (ref "C212") (pin "1") (pinfunction "1_1") (pintype "passive"))
      (node (ref "C213") (pin "1") (pinfunction "1_1") (pintype "passive"))
      (node (ref "C214") (pin "1") (pinfunction "1_1") (pintype "passive"))
      (node (ref "C215") (pin "1") (pinfunction "1_1") (pintype "passive"))
      (node (ref "C216") (pin "1") (pinfunction "1_1") (pintype "passive"))
      (node (ref "C217") (pin "2") (pinfunction "2_2") (pintype "passive"))
      (node (ref "C218") (pin "2") (pinfunction "2_2") (pintype "passive"))
      (node (ref "C219") (pin "2") (pinfunction "2_2") (pintype "passive"))
      (node (ref "C220") (pin "2") (pinfunction "2_2") (pintype "passive"))
      (node (ref "C221") (pin "2") (pinfunction "2_2") (pintype "passive"))
      (node (ref "C222") (pin "2") (pinfunction "2_2") (pintype "passive"))
      (node (ref "C223") (pin "2") (pinfunction "2_2") (pintype "passive"))
      (node (ref "C224") (pin "2") (pinfunction "2_2") (pintype "passive"))
      (node (ref "C225") (pin "2") (pinfunction "2_2") (pintype "passive"))
      (node (ref "C226") (pin "2") (pinfunction "2_2") (pintype "passive"))
      (node (ref "C227") (pin "1") (pinfunction "1_1") (pintype "passive"))
      (node (ref "C228") (pin "1") (pinfunction "1_1") (pintype "passive"))
      (node (ref "C229") (pin "1") (pinfunction "1_1") (pintype "passive"))
      (node (ref "C230") (pin "1") (pinfunction "1_1") (pintype "passive"))
      (node (ref "C231") (pin "1") (pinfunction "1_1") (pintype "passive"))
      (node (ref "C232") (pin "1") (pinfunction "1_1") (pintype "passive"))
      (node (ref "C233") (pin "1") (pinfunction "1_1") (pintype "passive"))
      (node (ref "C234") (pin "1") (pinfunction "1_1") (pintype "passive"))
      (node (ref "C235") (pin "1") (pinfunction "1_1") (pintype "passive"))
      (node (ref "C236") (pin "1") (pinfunction "1_1") (pintype "passive"))
      (node (ref "C237") (pin "1") (pinfunction "1_1") (pintype "passive"))
      (node (ref "C238") (pin "1") (pinfunction "1_1") (pintype "passive"))
      (node (ref "C239") (pin "1") (pinfunction "1_1") (pintype "passive"))
      (node (ref "C240") (pin "1") (pinfunction "1_1") (pintype "passive"))
      (node (ref "C241") (pin "1") (pinfunction "1_1") (pintype "passive"))
      (node (ref "C242") (pin "1") (pinfunction "1_1") (pintype "passive"))
      (node (ref "C243") (pin "2") (pinfunction "2_2") (pintype "passive"))
      (node (ref "C244") (pin "2") (pinfunction "2_2") (pintype "passive"))
      (node (ref "C245") (pin "1") (pinfunction "1_1") (pintype "passive"))
      (node (ref "C246") (pin "1") (pinfunction "1_1") (pintype "passive"))
      (node (ref "C247") (pin "1") (pinfunction "1_1") (pintype "passive"))
      (node (ref "C248") (pin "1") (pinfunction "1_1") (pintype "passive"))
      (node (ref "C249") (pin "1") (pinfunction "1_1") (pintype "passive"))
      (node (ref "C250") (pin "1") (pinfunction "1_1") (pintype "passive"))
      (node (ref "C251") (pin "1") (pinfunction "1_1") (pintype "passive"))
      (node (ref "C252") (pin "1") (pinfunction "1_1") (pintype "passive"))
      (node (ref "C253") (pin "2") (pinfunction "2_2") (pintype "passive"))
      (node (ref "C254") (pin "2") (pinfunction "2_2") (pintype "passive"))
      (node (ref "C255") (pin "1") (pinfunction "1_1") (pintype "passive"))
      (node (ref "C256") (pin "1") (pinfunction "1_1") (pintype "passive"))
      (node (ref "C257") (pin "1") (pinfunction "1_1") (pintype "passive"))
      (node (ref "C258") (pin "1") (pinfunction "1_1") (pintype "passive"))
      (node (ref "C259") (pin "1") (pinfunction "1_1") (pintype "passive"))
      (node (ref "C260") (pin "1") (pinfunction "1_1") (pintype "passive"))
      (node (ref "C261") (pin "1") (pinfunction "1_1") (pintype "passive"))
      (node (ref "C262") (pin "1") (pinfunction "1_1") (pintype "passive"))
      (node (ref "C263") (pin "2") (pinfunction "2_2") (pintype "passive"))
      (node (ref "C264") (pin "2") (pinfunction "2_2") (pintype "passive"))
      (node (ref "C265") (pin "1") (pinfunction "1_1") (pintype "passive"))
      (node (ref "C266") (pin "1") (pinfunction "1_1") (pintype "passive"))
      (node (ref "C267") (pin "1") (pinfunction "1_1") (pintype "passive"))
      (node (ref "C268") (pin "1") (pinfunction "1_1") (pintype "passive"))
      (node (ref "C269") (pin "1") (pinfunction "1_1") (pintype "passive"))
      (node (ref "C270") (pin "1") (pinfunction "1_1") (pintype "passive"))
      (node (ref "C271") (pin "1") (pinfunction "1_1") (pintype "passive"))
      (node (ref "C272") (pin "1") (pinfunction "1_1") (pintype "passive"))
      (node (ref "C273") (pin "2") (pinfunction "2_2") (pintype "passive"))
      (node (ref "C274") (pin "2") (pinfunction "2_2") (pintype "passive"))
      (node (ref "C275") (pin "1") (pinfunction "1_1") (pintype "passive"))
      (node (ref "C276") (pin "1") (pinfunction "1_1") (pintype "passive"))
      (node (ref "C277") (pin "1") (pinfunction "1_1") (pintype "passive"))
      (node (ref "C278") (pin "1") (pinfunction "1_1") (pintype "passive"))
      (node (ref "C279") (pin "1") (pinfunction "1_1") (pintype "passive"))
      (node (ref "C280") (pin "1") (pinfunction "1_1") (pintype "passive"))
      (node (ref "C281") (pin "1") (pinfunction "1_1") (pintype "passive"))
      (node (ref "C282") (pin "1") (pinfunction "1_1") (pintype "passive"))
      (node (ref "C283") (pin "1") (pinfunction "1_1") (pintype "passive"))
      (node (ref "C284") (pin "1") (pinfunction "1_1") (pintype "passive"))
      (node (ref "C285") (pin "1") (pinfunction "1_1") (pintype "passive"))
      (node (ref "C286") (pin "1") (pinfunction "1_1") (pintype "passive"))
      (node (ref "C287") (pin "1") (pinfunction "1_1") (pintype "passive"))
      (node (ref "C288") (pin "1") (pinfunction "1_1") (pintype "passive"))
      (node (ref "C289") (pin "2") (pinfunction "2_2") (pintype "passive"))
      (node (ref "C290") (pin "2") (pinfunction "2_2") (pintype "passive"))
      (node (ref "C291") (pin "1") (pinfunction "1_1") (pintype "passive"))
      (node (ref "C292") (pin "1") (pinfunction "1_1") (pintype "passive"))
      (node (ref "C293") (pin "1") (pinfunction "1_1") (pintype "passive"))
      (node (ref "C294") (pin "1") (pinfunction "1_1") (pintype "passive"))
      (node (ref "C295") (pin "1") (pinfunction "1_1") (pintype "passive"))
      (node (ref "C296") (pin "1") (pinfunction "1_1") (pintype "passive"))
      (node (ref "C297") (pin "1") (pinfunction "1_1") (pintype "passive"))
      (node (ref "C298") (pin "1") (pinfunction "1_1") (pintype "passive"))
      (node (ref "C299") (pin "2") (pinfunction "2_2") (pintype "passive"))
      (node (ref "C300") (pin "2") (pinfunction "2_2") (pintype "passive"))
      (node (ref "C301") (pin "1") (pinfunction "1_1") (pintype "passive"))
      (node (ref "C302") (pin "1") (pinfunction "1_1") (pintype "passive"))
      (node (ref "C303") (pin "1") (pinfunction "1_1") (pintype "passive"))
      (node (ref "C304") (pin "1") (pinfunction "1_1") (pintype "passive"))
      (node (ref "C305") (pin "1") (pinfunction "1_1") (pintype "passive"))
      (node (ref "C306") (pin "1") (pinfunction "1_1") (pintype "passive"))
      (node (ref "C307") (pin "1") (pinfunction "1_1") (pintype "passive"))
      (node (ref "C308") (pin "1") (pinfunction "1_1") (pintype "passive"))
      (node (ref "C309") (pin "1") (pinfunction "1_1") (pintype "passive"))
      (node (ref "C310") (pin "1") (pinfunction "1_1") (pintype "passive"))
      (node (ref "C311") (pin "1") (pinfunction "1_1") (pintype "passive"))
      (node (ref "C312") (pin "1") (pinfunction "1_1") (pintype "passive"))
      (node (ref "C313") (pin "1") (pinfunction "1_1") (pintype "passive"))
      (node (ref "C314") (pin "1") (pinfunction "1_1") (pintype "passive"))
      (node (ref "C315") (pin "2") (pinfunction "2_2") (pintype "passive"))
      (node (ref "C316") (pin "2") (pinfunction "2_2") (pintype "passive"))
      (node (ref "C317") (pin "1") (pinfunction "1_1") (pintype "passive"))
      (node (ref "C318") (pin "1") (pinfunction "1_1") (pintype "passive"))
      (node (ref "C319") (pin "1") (pinfunction "1_1") (pintype "passive"))
      (node (ref "C320") (pin "1") (pinfunction "1_1") (pintype "passive"))
      (node (ref "C321") (pin "1") (pinfunction "1_1") (pintype "passive"))
      (node (ref "C322") (pin "1") (pinfunction "1_1") (pintype "passive"))
      (node (ref "C323") (pin "1") (pinfunction "1_1") (pintype "passive"))
      (node (ref "C324") (pin "1") (pinfunction "1_1") (pintype "passive"))
      (node (ref "C325") (pin "2") (pinfunction "2_2") (pintype "passive"))
      (node (ref "C326") (pin "2") (pinfunction "2_2") (pintype "passive"))
      (node (ref "C327") (pin "1") (pinfunction "1_1") (pintype "passive"))
      (node (ref "C328") (pin "1") (pinfunction "1_1") (pintype "passive"))
      (node (ref "C329") (pin "1") (pinfunction "1_1") (pintype "passive"))
      (node (ref "C330") (pin "1") (pinfunction "1_1") (pintype "passive"))
      (node (ref "C331") (pin "2") (pinfunction "2_2") (pintype "passive"))
      (node (ref "C332") (pin "2") (pinfunction "2_2") (pintype "passive"))
      (node (ref "IC1") (pin "W24") (pinfunction "D1_MCK1_W24") (pintype "passive"))
      (node (ref "IC1") (pin "W25") (pinfunction "D1_MCK1#_W25") (pintype "passive"))
      (node (ref "IC16") (pin "A2") (pinfunction "VSSQ1_A2") (pintype "passive"))
      (node (ref "IC16") (pin "A8") (pinfunction "VSSQ2_A8") (pintype "passive"))
      (node (ref "IC16") (pin "A9") (pinfunction "VSS1_A9") (pintype "passive"))
      (node (ref "IC16") (pin "C8") (pinfunction "VSS2_C8") (pintype "passive"))
      (node (ref "IC16") (pin "D1") (pinfunction "VSSQ3_D1") (pintype "passive"))
      (node (ref "IC16") (pin "D9") (pinfunction "VSSQ4_D9") (pintype "passive"))
      (node (ref "IC16") (pin "E1") (pinfunction "VSS3_E1") (pintype "passive"))
      (node (ref "IC16") (pin "E9") (pinfunction "VSS4_E9") (pintype "passive"))
      (node (ref "IC16") (pin "G1") (pinfunction "VSS5_G1") (pintype "passive"))
      (node (ref "IC16") (pin "H9") (pinfunction "VSS6_H9") (pintype "passive"))
      (node (ref "IC16") (pin "K1") (pinfunction "VSS7_K1") (pintype "passive"))
      (node (ref "IC16") (pin "K9") (pinfunction "VSS8_K9") (pintype "passive"))
      (node (ref "IC16") (pin "N1") (pinfunction "VSS9_N1") (pintype "passive"))
      (node (ref "IC17") (pin "A2") (pinfunction "VSSQ1_A2") (pintype "passive"))
      (node (ref "IC17") (pin "A8") (pinfunction "VSSQ2_A8") (pintype "passive"))
      (node (ref "IC17") (pin "A9") (pinfunction "VSS1_A9") (pintype "passive"))
      (node (ref "IC17") (pin "C8") (pinfunction "VSS2_C8") (pintype "passive"))
      (node (ref "IC17") (pin "D1") (pinfunction "VSSQ3_D1") (pintype "passive"))
      (node (ref "IC17") (pin "D9") (pinfunction "VSSQ4_D9") (pintype "passive"))
      (node (ref "IC17") (pin "E1") (pinfunction "VSS3_E1") (pintype "passive"))
      (node (ref "IC17") (pin "E9") (pinfunction "VSS4_E9") (pintype "passive"))
      (node (ref "IC17") (pin "G1") (pinfunction "VSS5_G1") (pintype "passive"))
      (node (ref "IC17") (pin "H9") (pinfunction "VSS6_H9") (pintype "passive"))
      (node (ref "IC17") (pin "K1") (pinfunction "VSS7_K1") (pintype "passive"))
      (node (ref "IC17") (pin "K9") (pinfunction "VSS8_K9") (pintype "passive"))
      (node (ref "IC17") (pin "N1") (pinfunction "VSS9_N1") (pintype "passive"))
      (node (ref "IC18") (pin "A2") (pinfunction "VSSQ1_A2") (pintype "passive"))
      (node (ref "IC18") (pin "A8") (pinfunction "VSSQ2_A8") (pintype "passive"))
      (node (ref "IC18") (pin "A9") (pinfunction "VSS1_A9") (pintype "passive"))
      (node (ref "IC18") (pin "C8") (pinfunction "VSS2_C8") (pintype "passive"))
      (node (ref "IC18") (pin "D1") (pinfunction "VSSQ3_D1") (pintype "passive"))
      (node (ref "IC18") (pin "D9") (pinfunction "VSSQ4_D9") (pintype "passive"))
      (node (ref "IC18") (pin "E1") (pinfunction "VSS3_E1") (pintype "passive"))
      (node (ref "IC18") (pin "E9") (pinfunction "VSS4_E9") (pintype "passive"))
      (node (ref "IC18") (pin "G1") (pinfunction "VSS5_G1") (pintype "passive"))
      (node (ref "IC18") (pin "H9") (pinfunction "VSS6_H9") (pintype "passive"))
      (node (ref "IC18") (pin "K1") (pinfunction "VSS7_K1") (pintype "passive"))
      (node (ref "IC18") (pin "K9") (pinfunction "VSS8_K9") (pintype "passive"))
      (node (ref "IC18") (pin "N1") (pinfunction "VSS9_N1") (pintype "passive"))
      (node (ref "IC19") (pin "A2") (pinfunction "VSSQ1_A2") (pintype "passive"))
      (node (ref "IC19") (pin "A8") (pinfunction "VSSQ2_A8") (pintype "passive"))
      (node (ref "IC19") (pin "A9") (pinfunction "VSS1_A9") (pintype "passive"))
      (node (ref "IC19") (pin "C8") (pinfunction "VSS2_C8") (pintype "passive"))
      (node (ref "IC19") (pin "D1") (pinfunction "VSSQ3_D1") (pintype "passive"))
      (node (ref "IC19") (pin "D9") (pinfunction "VSSQ4_D9") (pintype "passive"))
      (node (ref "IC19") (pin "E1") (pinfunction "VSS3_E1") (pintype "passive"))
      (node (ref "IC19") (pin "E9") (pinfunction "VSS4_E9") (pintype "passive"))
      (node (ref "IC19") (pin "G1") (pinfunction "VSS5_G1") (pintype "passive"))
      (node (ref "IC19") (pin "H9") (pinfunction "VSS6_H9") (pintype "passive"))
      (node (ref "IC19") (pin "K1") (pinfunction "VSS7_K1") (pintype "passive"))
      (node (ref "IC19") (pin "K9") (pinfunction "VSS8_K9") (pintype "passive"))
      (node (ref "IC19") (pin "N1") (pinfunction "VSS9_N1") (pintype "passive"))
      (node (ref "IC20") (pin "A2") (pinfunction "VSSQ1_A2") (pintype "passive"))
      (node (ref "IC20") (pin "A8") (pinfunction "VSSQ2_A8") (pintype "passive"))
      (node (ref "IC20") (pin "A9") (pinfunction "VSS1_A9") (pintype "passive"))
      (node (ref "IC20") (pin "C8") (pinfunction "VSS2_C8") (pintype "passive"))
      (node (ref "IC20") (pin "D1") (pinfunction "VSSQ3_D1") (pintype "passive"))
      (node (ref "IC20") (pin "D9") (pinfunction "VSSQ4_D9") (pintype "passive"))
      (node (ref "IC20") (pin "E1") (pinfunction "VSS3_E1") (pintype "passive"))
      (node (ref "IC20") (pin "E9") (pinfunction "VSS4_E9") (pintype "passive"))
      (node (ref "IC20") (pin "G1") (pinfunction "VSS5_G1") (pintype "passive"))
      (node (ref "IC20") (pin "H9") (pinfunction "VSS6_H9") (pintype "passive"))
      (node (ref "IC20") (pin "K1") (pinfunction "VSS7_K1") (pintype "passive"))
      (node (ref "IC20") (pin "K9") (pinfunction "VSS8_K9") (pintype "passive"))
      (node (ref "IC20") (pin "N1") (pinfunction "VSS9_N1") (pintype "passive"))
      (node (ref "IC21") (pin "A2") (pinfunction "VSSQ1_A2") (pintype "passive"))
      (node (ref "IC21") (pin "A8") (pinfunction "VSSQ2_A8") (pintype "passive"))
      (node (ref "IC21") (pin "A9") (pinfunction "VSS1_A9") (pintype "passive"))
      (node (ref "IC21") (pin "C8") (pinfunction "VSS2_C8") (pintype "passive"))
      (node (ref "IC21") (pin "D1") (pinfunction "VSSQ3_D1") (pintype "passive"))
      (node (ref "IC21") (pin "D9") (pinfunction "VSSQ4_D9") (pintype "passive"))
      (node (ref "IC21") (pin "E1") (pinfunction "VSS3_E1") (pintype "passive"))
      (node (ref "IC21") (pin "E9") (pinfunction "VSS4_E9") (pintype "passive"))
      (node (ref "IC21") (pin "G1") (pinfunction "VSS5_G1") (pintype "passive"))
      (node (ref "IC21") (pin "H9") (pinfunction "VSS6_H9") (pintype "passive"))
      (node (ref "IC21") (pin "K1") (pinfunction "VSS7_K1") (pintype "passive"))
      (node (ref "IC21") (pin "K9") (pinfunction "VSS8_K9") (pintype "passive"))
      (node (ref "IC21") (pin "N1") (pinfunction "VSS9_N1") (pintype "passive"))
      (node (ref "IC22") (pin "A2") (pinfunction "VSSQ1_A2") (pintype "passive"))
      (node (ref "IC22") (pin "A8") (pinfunction "VSSQ2_A8") (pintype "passive"))
      (node (ref "IC22") (pin "A9") (pinfunction "VSS1_A9") (pintype "passive"))
      (node (ref "IC22") (pin "C8") (pinfunction "VSS2_C8") (pintype "passive"))
      (node (ref "IC22") (pin "D1") (pinfunction "VSSQ3_D1") (pintype "passive"))
      (node (ref "IC22") (pin "D9") (pinfunction "VSSQ4_D9") (pintype "passive"))
      (node (ref "IC22") (pin "E1") (pinfunction "VSS3_E1") (pintype "passive"))
      (node (ref "IC22") (pin "E9") (pinfunction "VSS4_E9") (pintype "passive"))
      (node (ref "IC22") (pin "G1") (pinfunction "VSS5_G1") (pintype "passive"))
      (node (ref "IC22") (pin "H9") (pinfunction "VSS6_H9") (pintype "passive"))
      (node (ref "IC22") (pin "K1") (pinfunction "VSS7_K1") (pintype "passive"))
      (node (ref "IC22") (pin "K9") (pinfunction "VSS8_K9") (pintype "passive"))
      (node (ref "IC22") (pin "N1") (pinfunction "VSS9_N1") (pintype "passive"))
      (node (ref "IC23") (pin "A2") (pinfunction "VSSQ1_A2") (pintype "passive"))
      (node (ref "IC23") (pin "A8") (pinfunction "VSSQ2_A8") (pintype "passive"))
      (node (ref "IC23") (pin "A9") (pinfunction "VSS1_A9") (pintype "passive"))
      (node (ref "IC23") (pin "C8") (pinfunction "VSS2_C8") (pintype "passive"))
      (node (ref "IC23") (pin "D1") (pinfunction "VSSQ3_D1") (pintype "passive"))
      (node (ref "IC23") (pin "D9") (pinfunction "VSSQ4_D9") (pintype "passive"))
      (node (ref "IC23") (pin "E1") (pinfunction "VSS3_E1") (pintype "passive"))
      (node (ref "IC23") (pin "E9") (pinfunction "VSS4_E9") (pintype "passive"))
      (node (ref "IC23") (pin "G1") (pinfunction "VSS5_G1") (pintype "passive"))
      (node (ref "IC23") (pin "H9") (pinfunction "VSS6_H9") (pintype "passive"))
      (node (ref "IC23") (pin "K1") (pinfunction "VSS7_K1") (pintype "passive"))
      (node (ref "IC23") (pin "K9") (pinfunction "VSS8_K9") (pintype "passive"))
      (node (ref "IC23") (pin "N1") (pinfunction "VSS9_N1") (pintype "passive"))
      (node (ref "IC24") (pin "1") (pinfunction "NC_1") (pintype "passive"))
      (node (ref "IC24") (pin "3") (pinfunction "A2_3") (pintype "passive"))
      (node (ref "IC24") (pin "4") (pinfunction "GND_4") (pintype "passive"))
      (node (ref "R135") (pin "1") (pinfunction "1_1") (pintype "passive"))
      (node (ref "R136") (pin "1") (pinfunction "1_1") (pintype "passive"))
      (node (ref "R137") (pin "1") (pinfunction "1_1") (pintype "passive"))
      (node (ref "R138") (pin "1") (pinfunction "1_1") (pintype "passive"))
      (node (ref "R140") (pin "1") (pinfunction "1_1") (pintype "passive"))
      (node (ref "R143") (pin "1") (pinfunction "1_1") (pintype "passive"))
      (node (ref "R145") (pin "2") (pinfunction "2_2") (pintype "passive"))
      (node (ref "R148") (pin "1") (pinfunction "1_1") (pintype "passive"))
      (node (ref "R149") (pin "1") (pinfunction "1_1") (pintype "passive"))
      (node (ref "R150") (pin "1") (pinfunction "1_1") (pintype "passive"))
      (node (ref "R151") (pin "1") (pinfunction "1_1") (pintype "passive"))
      (node (ref "R152") (pin "1") (pinfunction "1_1") (pintype "passive"))
    )
    (net (code "101") (name "Net-(C225-Pad1)") (class "Default")
      (node (ref "C225") (pin "1") (pinfunction "1_1") (pintype "passive"))
      (node (ref "R146") (pin "2") (pinfunction "2_2") (pintype "passive"))
      (node (ref "R147") (pin "2") (pinfunction "2_2") (pintype "passive"))
    )
    (net (code "102") (name "Net-(IC1A-D1_MAPAR_ERR#)") (class "Default")
      (node (ref "IC1") (pin "AD24") (pinfunction "D1_MAPAR_ERR#_AD24") (pintype "passive"))
      (node (ref "R141") (pin "1") (pinfunction "1_1") (pintype "passive"))
      (node (ref "R142") (pin "1") (pinfunction "1_1") (pintype "passive"))
    )
    (net (code "103") (name "Net-(IC1A-D1_MDIC0)") (class "Default")
      (node (ref "IC1") (pin "V25") (pinfunction "D1_MDIC0_V25") (pintype "passive"))
      (node (ref "R140") (pin "2") (pinfunction "2_2") (pintype "passive"))
    )
    (net (code "104") (name "Net-(IC1A-D1_MDIC1)") (class "Default")
      (node (ref "IC1") (pin "Y25") (pinfunction "D1_MDIC1_Y25") (pintype "passive"))
      (node (ref "R139") (pin "2") (pinfunction "2_2") (pintype "passive"))
    )
    (net (code "105") (name "Net-(IC1A-D1_MVREF)") (class "Default")
      (node (ref "IC1") (pin "H19") (pinfunction "D1_MVREF_H19") (pintype "passive"))
      (node (ref "R143") (pin "2") (pinfunction "2_2") (pintype "passive"))
    )
    (net (code "106") (name "Net-(IC24-WP)") (class "Default")
      (node (ref "IC24") (pin "7") (pinfunction "WP_7") (pintype "passive"))
      (node (ref "R150") (pin "2") (pinfunction "2_2") (pintype "passive"))
    )
    (net (code "107") (name "unconnected-(IC1A-D1_MCS2#-PadAB20)") (class "Default")
      (node (ref "IC1") (pin "AB20") (pinfunction "D1_MCS2#_AB20") (pintype "passive+no_connect"))
    )
    (net (code "108") (name "unconnected-(IC1A-D1_MCS3#-PadAA22)") (class "Default")
      (node (ref "IC1") (pin "AA22") (pinfunction "D1_MCS3#_AA22") (pintype "passive+no_connect"))
    )
    (net (code "109") (name "unconnected-(IC1A-D1_TPA-PadD1)") (class "Default")
      (node (ref "IC1") (pin "D1") (pinfunction "D1_TPA_D1") (pintype "passive+no_connect"))
    )
    (net (code "110") (name "unconnected-(IC16-A17{slash}NC-PadN7)") (class "Default")
      (node (ref "IC16") (pin "N7") (pinfunction "A17/NC_N7") (pintype "passive+no_connect"))
    )
    (net (code "111") (name "unconnected-(IC16-NF{slash}TDQS_C-PadA3)") (class "Default")
      (node (ref "IC16") (pin "A3") (pinfunction "NF/TDQS_C_A3") (pintype "passive+no_connect"))
    )
    (net (code "112") (name "unconnected-(IC17-A17{slash}NC-PadN7)") (class "Default")
      (node (ref "IC17") (pin "N7") (pinfunction "A17/NC_N7") (pintype "passive+no_connect"))
    )
    (net (code "113") (name "unconnected-(IC17-NF{slash}TDQS_C-PadA3)") (class "Default")
      (node (ref "IC17") (pin "A3") (pinfunction "NF/TDQS_C_A3") (pintype "passive+no_connect"))
    )
    (net (code "114") (name "unconnected-(IC18-A17{slash}NC-PadN7)") (class "Default")
      (node (ref "IC18") (pin "N7") (pinfunction "A17/NC_N7") (pintype "passive+no_connect"))
    )
    (net (code "115") (name "unconnected-(IC18-NF{slash}TDQS_C-PadA3)") (class "Default")
      (node (ref "IC18") (pin "A3") (pinfunction "NF/TDQS_C_A3") (pintype "passive+no_connect"))
    )
    (net (code "116") (name "unconnected-(IC19-A17{slash}NC-PadN7)") (class "Default")
      (node (ref "IC19") (pin "N7") (pinfunction "A17/NC_N7") (pintype "passive+no_connect"))
    )
    (net (code "117") (name "unconnected-(IC19-NF{slash}TDQS_C-PadA3)") (class "Default")
      (node (ref "IC19") (pin "A3") (pinfunction "NF/TDQS_C_A3") (pintype "passive+no_connect"))
    )
    (net (code "118") (name "unconnected-(IC20-A17{slash}NC-PadN7)") (class "Default")
      (node (ref "IC20") (pin "N7") (pinfunction "A17/NC_N7") (pintype "passive+no_connect"))
    )
    (net (code "119") (name "unconnected-(IC20-NF{slash}TDQS_C-PadA3)") (class "Default")
      (node (ref "IC20") (pin "A3") (pinfunction "NF/TDQS_C_A3") (pintype "passive+no_connect"))
    )
    (net (code "120") (name "unconnected-(IC21-A17{slash}NC-PadN7)") (class "Default")
      (node (ref "IC21") (pin "N7") (pinfunction "A17/NC_N7") (pintype "passive+no_connect"))
    )
    (net (code "121") (name "unconnected-(IC21-NF{slash}TDQS_C-PadA3)") (class "Default")
      (node (ref "IC21") (pin "A3") (pinfunction "NF/TDQS_C_A3") (pintype "passive+no_connect"))
    )
    (net (code "122") (name "unconnected-(IC22-A17{slash}NC-PadN7)") (class "Default")
      (node (ref "IC22") (pin "N7") (pinfunction "A17/NC_N7") (pintype "passive+no_connect"))
    )
    (net (code "123") (name "unconnected-(IC22-NF{slash}TDQS_C-PadA3)") (class "Default")
      (node (ref "IC22") (pin "A3") (pinfunction "NF/TDQS_C_A3") (pintype "passive+no_connect"))
    )
    (net (code "124") (name "unconnected-(IC23-A17{slash}NC-PadN7)") (class "Default")
      (node (ref "IC23") (pin "N7") (pinfunction "A17/NC_N7") (pintype "passive+no_connect"))
    )
    (net (code "125") (name "unconnected-(IC23-NF{slash}TDQS_C-PadA3)") (class "Default")
      (node (ref "IC23") (pin "A3") (pinfunction "NF/TDQS_C_A3") (pintype "passive+no_connect"))
    )
  )
)
